# nbulb.net
KiCad netlist of a schematic drawn in EAGLE
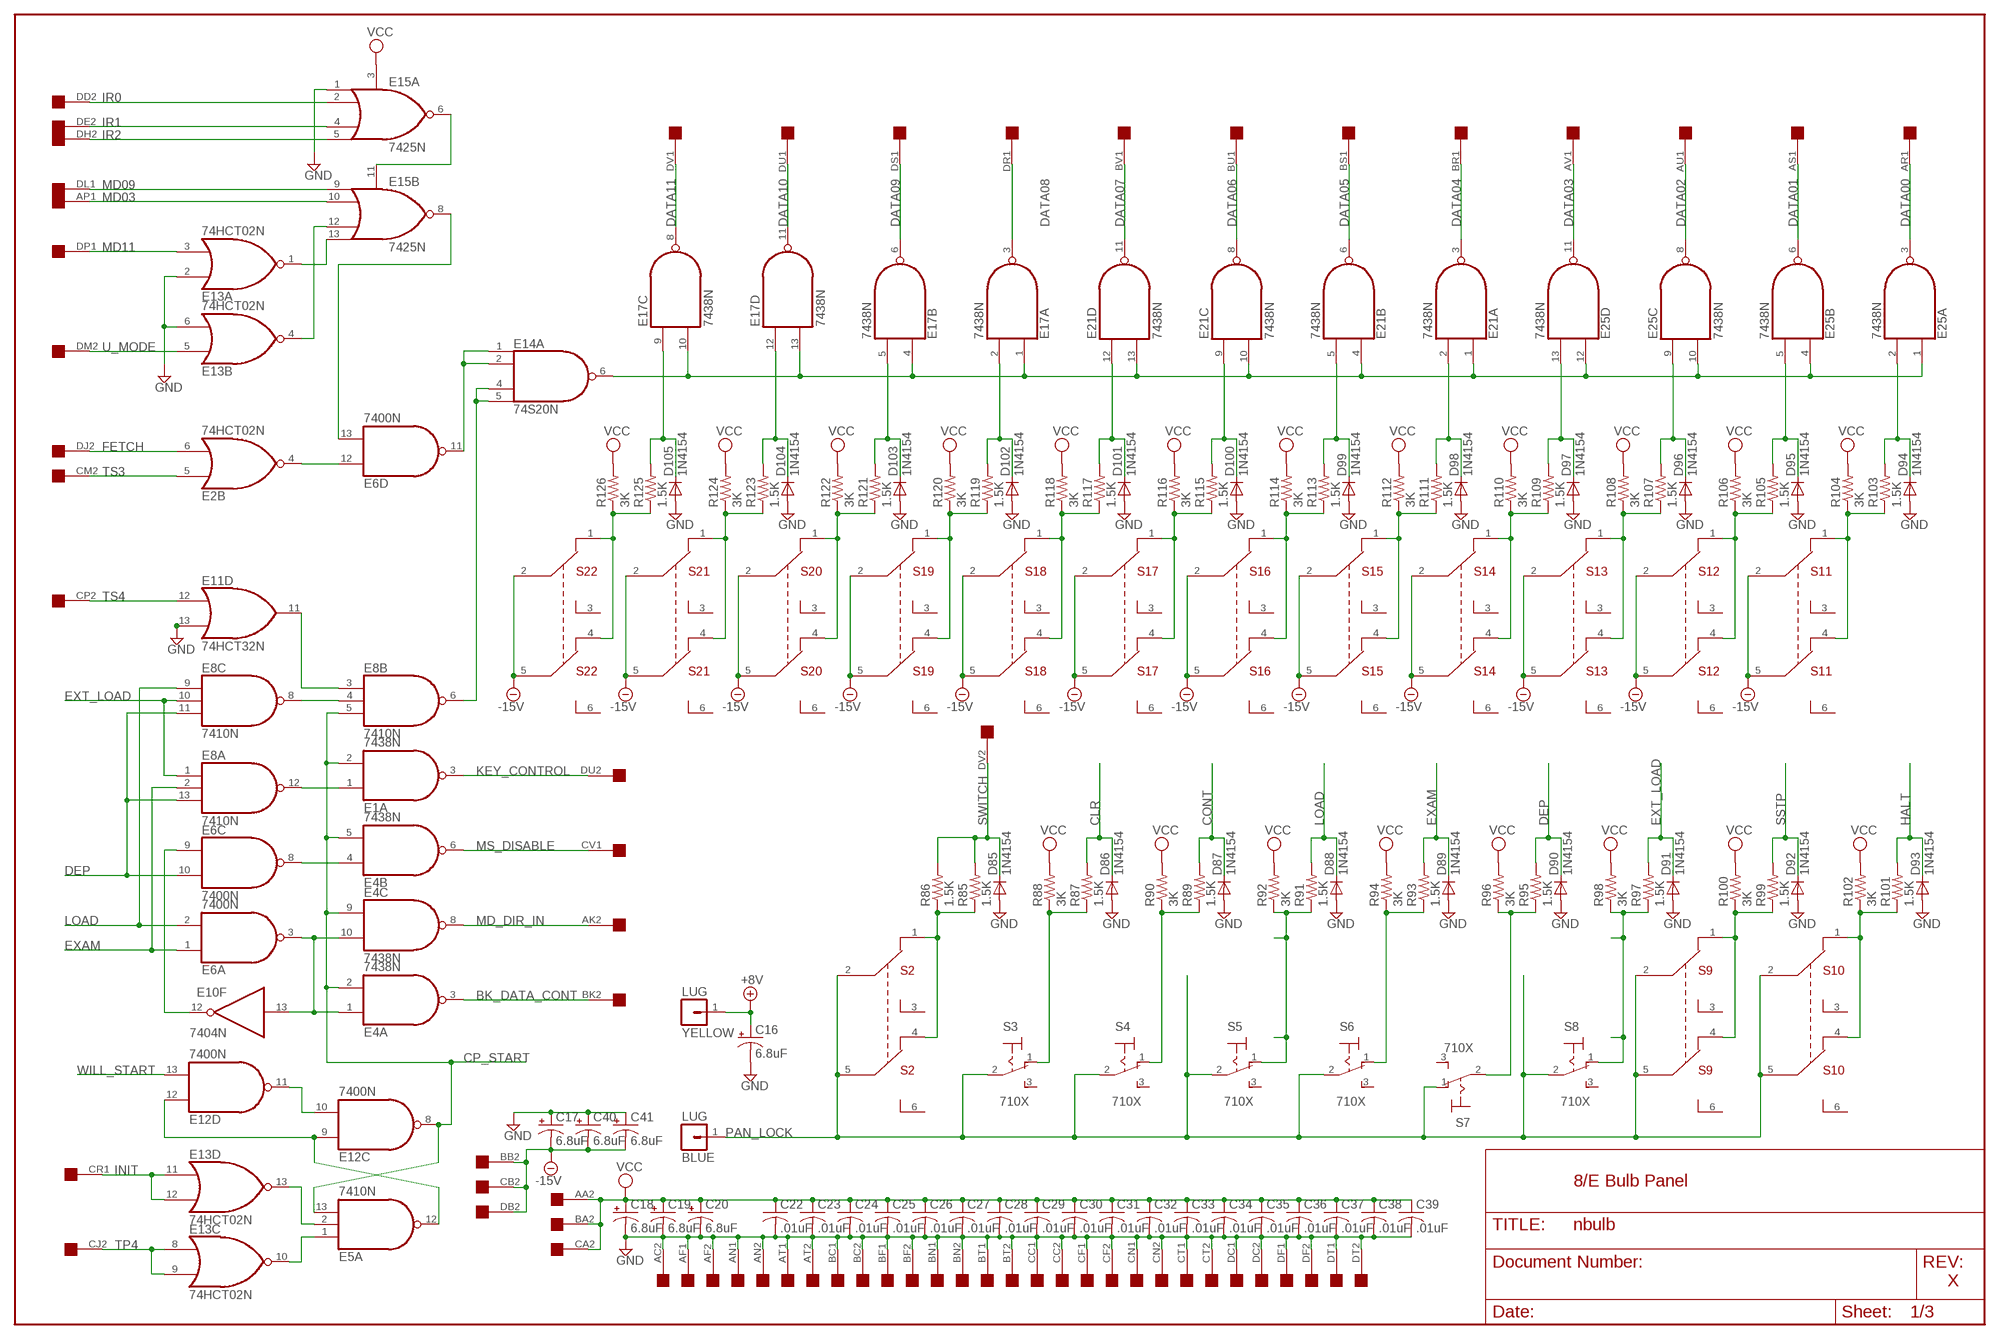
[diagram p0: schematic, sheet 1]
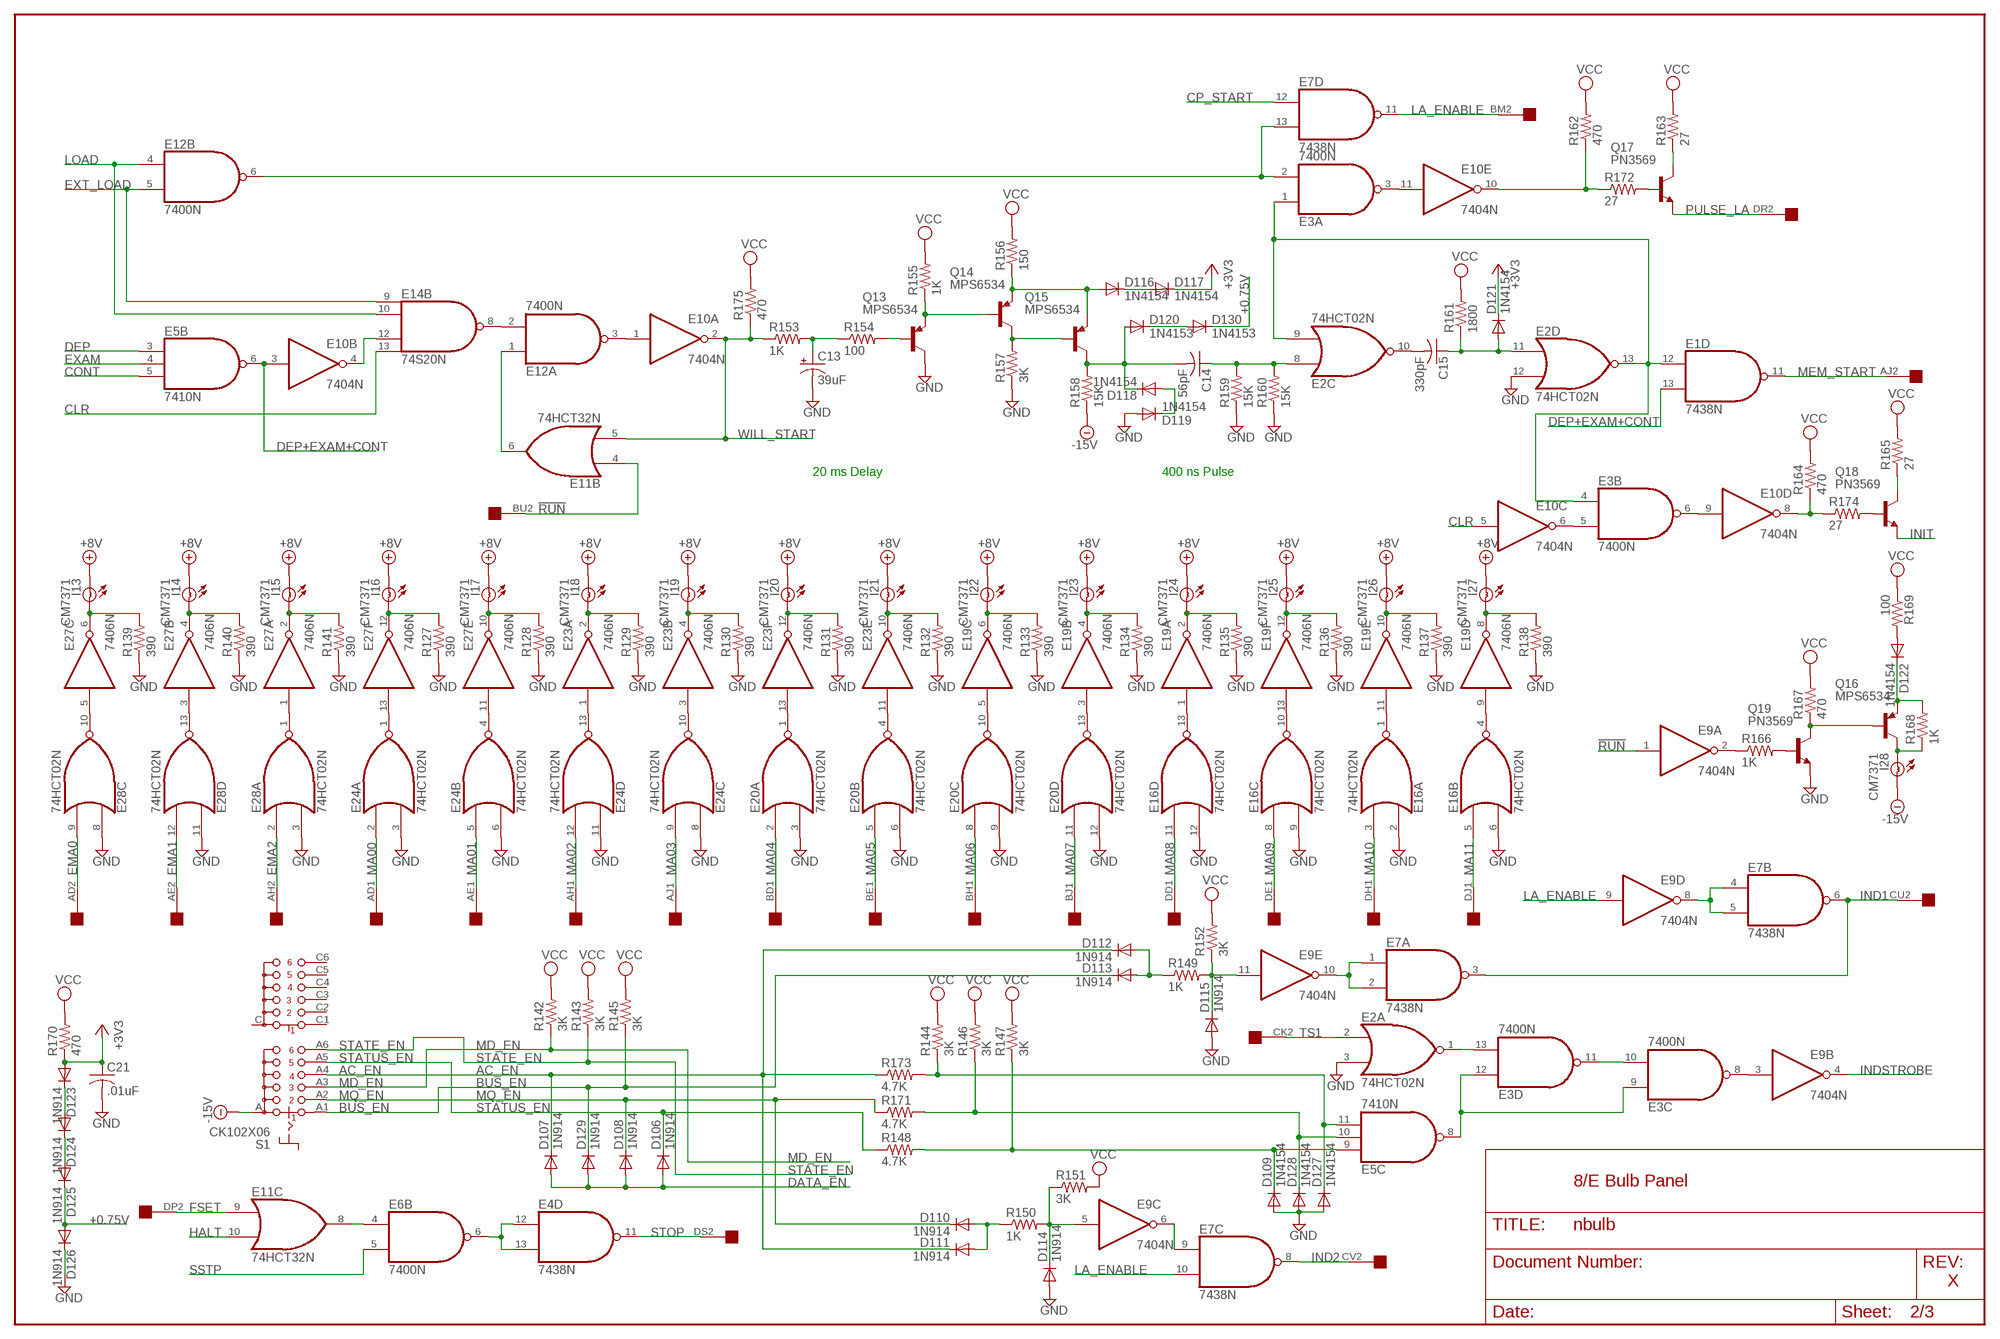
[diagram p1: schematic, sheet 2]
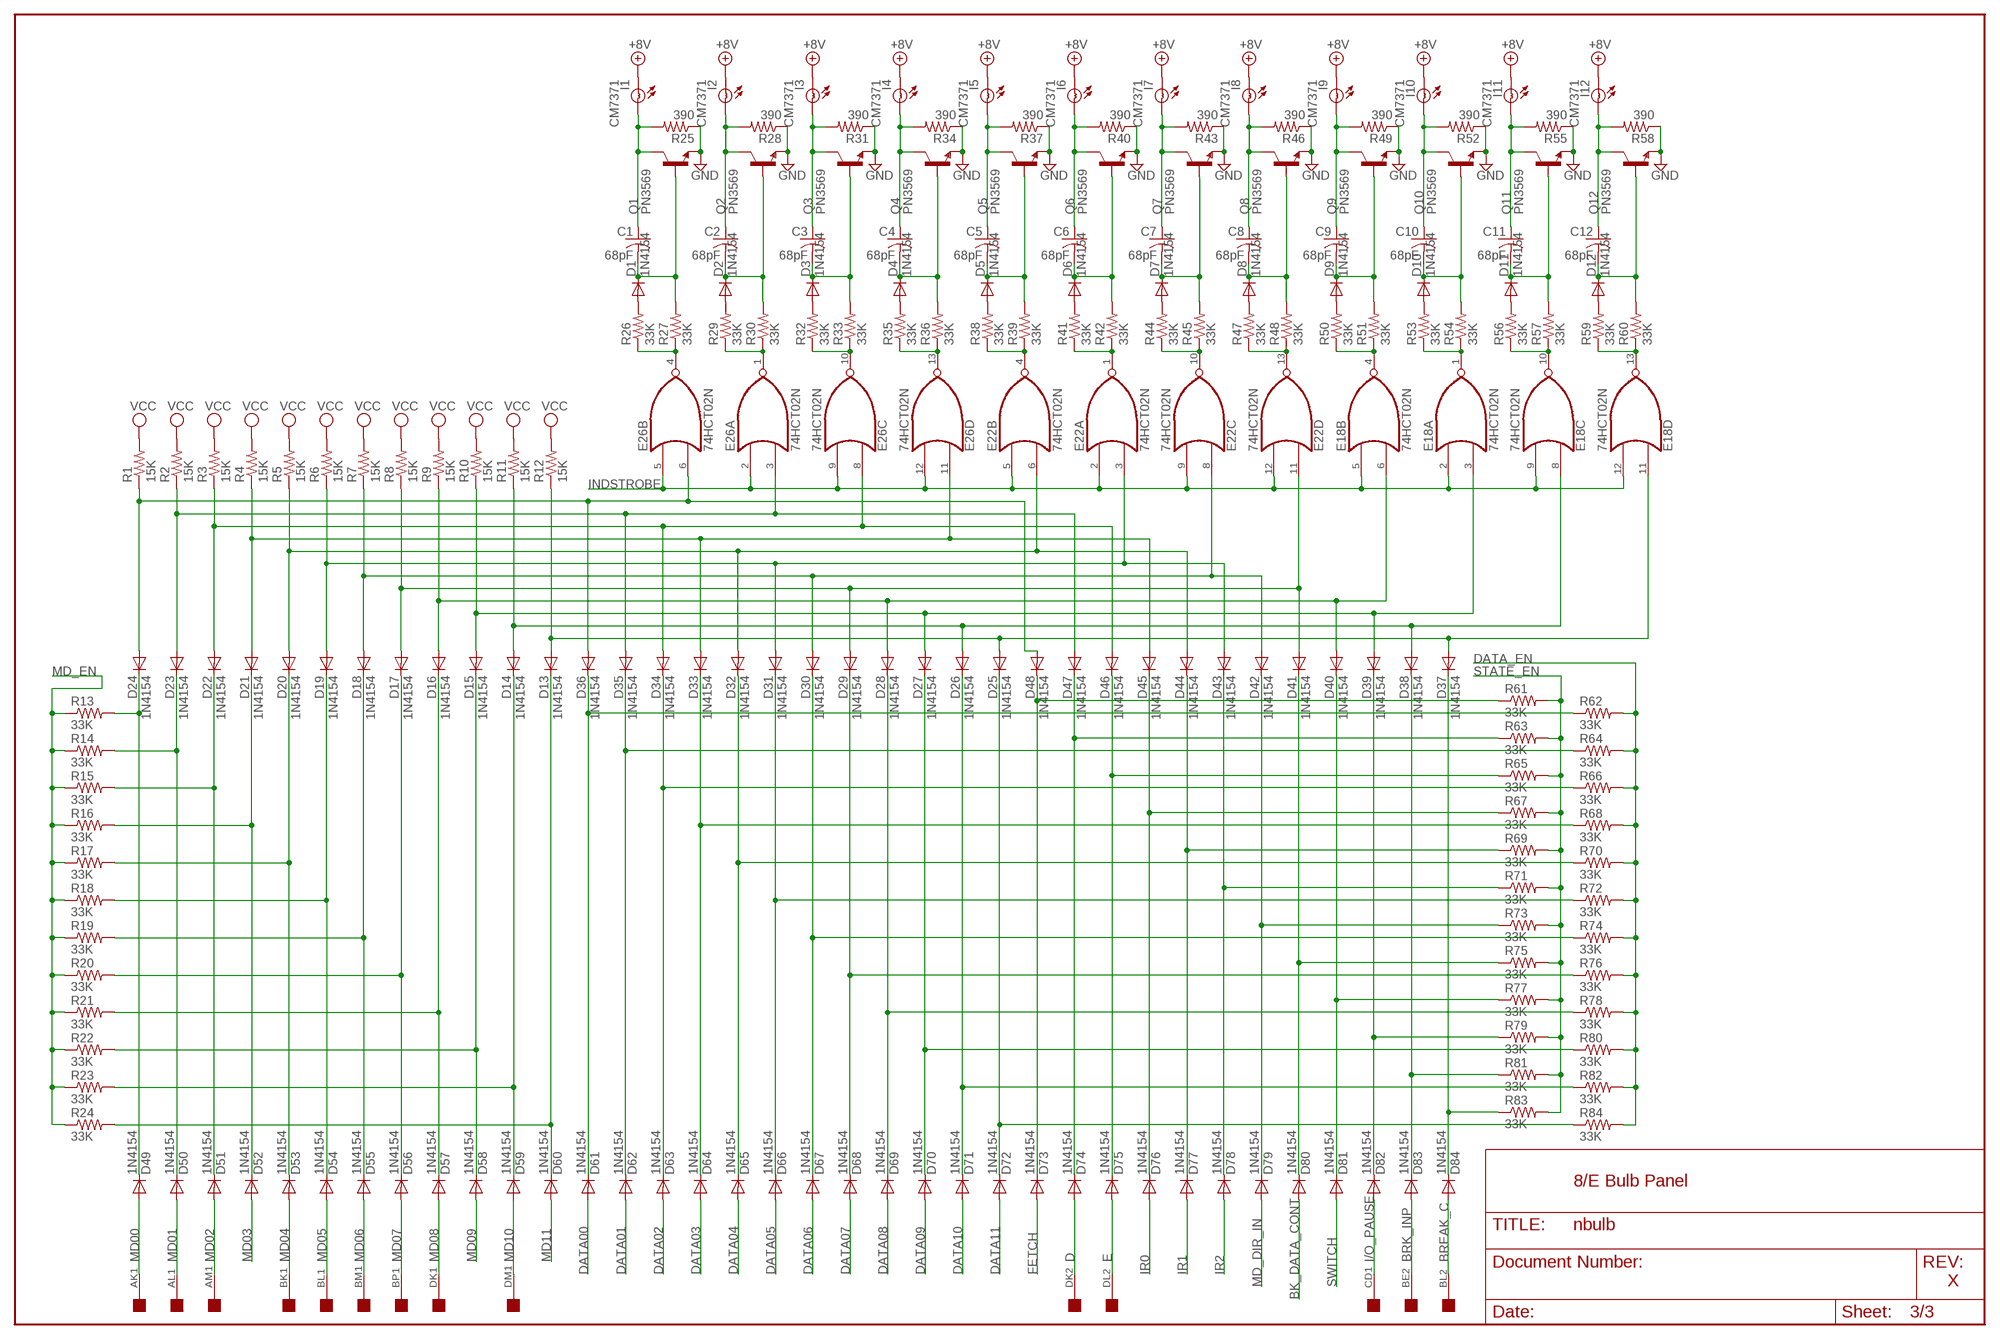
[diagram p2: schematic, sheet 3]

(export (version "E")
  (design (tool "Eeschema 10.0.6"))
  (components
    (comp (ref "BLUE")
      (value "LUG")
      (footprint "eagle-import:SPADELUG")
      (libsource (lib "eagle-import") (part "LUG"))
    )
    (comp (ref "C16")
      (value "6.8uF")
      (footprint "eagle-import:E12-8")
      (libsource (lib "eagle-import") (part "CPOL-USE20-8AXIAL"))
    )
    (comp (ref "C17")
      (value "6.8uF")
      (footprint "eagle-import:E12-8")
      (libsource (lib "eagle-import") (part "CPOL-USE20-8AXIAL"))
    )
    (comp (ref "C18")
      (value "6.8uF")
      (footprint "eagle-import:E12-8")
      (libsource (lib "eagle-import") (part "CPOL-USE20-8AXIAL"))
    )
    (comp (ref "C19")
      (value "6.8uF")
      (footprint "eagle-import:E12-8")
      (libsource (lib "eagle-import") (part "CPOL-USE20-8AXIAL"))
    )
    (comp (ref "C20")
      (value "6.8uF")
      (footprint "eagle-import:E12-8")
      (libsource (lib "eagle-import") (part "CPOL-USE20-8AXIAL"))
    )
    (comp (ref "C22")
      (value ".01uF")
      (footprint "eagle-import:C050-025X075")
      (libsource (lib "eagle-import") (part "C-US050-025X075"))
    )
    (comp (ref "C23")
      (value ".01uF")
      (footprint "eagle-import:C050-025X075")
      (libsource (lib "eagle-import") (part "C-US050-025X075"))
    )
    (comp (ref "C24")
      (value ".01uF")
      (footprint "eagle-import:C050-025X075")
      (libsource (lib "eagle-import") (part "C-US050-025X075"))
    )
    (comp (ref "C25")
      (value ".01uF")
      (footprint "eagle-import:C050-025X075")
      (libsource (lib "eagle-import") (part "C-US050-025X075"))
    )
    (comp (ref "C26")
      (value ".01uF")
      (footprint "eagle-import:C050-025X075")
      (libsource (lib "eagle-import") (part "C-US050-025X075"))
    )
    (comp (ref "C27")
      (value ".01uF")
      (footprint "eagle-import:C050-025X075")
      (libsource (lib "eagle-import") (part "C-US050-025X075"))
    )
    (comp (ref "C28")
      (value ".01uF")
      (footprint "eagle-import:C050-025X075")
      (libsource (lib "eagle-import") (part "C-US050-025X075"))
    )
    (comp (ref "C29")
      (value ".01uF")
      (footprint "eagle-import:C050-025X075")
      (libsource (lib "eagle-import") (part "C-US050-025X075"))
    )
    (comp (ref "C30")
      (value ".01uF")
      (footprint "eagle-import:C050-025X075")
      (libsource (lib "eagle-import") (part "C-US050-025X075"))
    )
    (comp (ref "C31")
      (value ".01uF")
      (footprint "eagle-import:C050-025X075")
      (libsource (lib "eagle-import") (part "C-US050-025X075"))
    )
    (comp (ref "C32")
      (value ".01uF")
      (footprint "eagle-import:C050-025X075")
      (libsource (lib "eagle-import") (part "C-US050-025X075"))
    )
    (comp (ref "C33")
      (value ".01uF")
      (footprint "eagle-import:C050-025X075")
      (libsource (lib "eagle-import") (part "C-US050-025X075"))
    )
    (comp (ref "C34")
      (value ".01uF")
      (footprint "eagle-import:C050-025X075")
      (libsource (lib "eagle-import") (part "C-US050-025X075"))
    )
    (comp (ref "C35")
      (value ".01uF")
      (footprint "eagle-import:C050-025X075")
      (libsource (lib "eagle-import") (part "C-US050-025X075"))
    )
    (comp (ref "C36")
      (value ".01uF")
      (footprint "eagle-import:C050-025X075")
      (libsource (lib "eagle-import") (part "C-US050-025X075"))
    )
    (comp (ref "C37")
      (value ".01uF")
      (footprint "eagle-import:C050-025X075")
      (libsource (lib "eagle-import") (part "C-US050-025X075"))
    )
    (comp (ref "C38")
      (value ".01uF")
      (footprint "eagle-import:C050-025X075")
      (libsource (lib "eagle-import") (part "C-US050-025X075"))
    )
    (comp (ref "C39")
      (value ".01uF")
      (footprint "eagle-import:C050-025X075")
      (libsource (lib "eagle-import") (part "C-US050-025X075"))
    )
    (comp (ref "C40")
      (value "6.8uF")
      (footprint "eagle-import:E12-8")
      (libsource (lib "eagle-import") (part "CPOL-USE20-8AXIAL"))
    )
    (comp (ref "C41")
      (value "6.8uF")
      (footprint "eagle-import:E12-8")
      (libsource (lib "eagle-import") (part "CPOL-USE20-8AXIAL"))
    )
    (comp (ref "D85")
      (value "1N4154")
      (footprint "eagle-import:DO35-10")
      (libsource (lib "eagle-import") (part "1N4148DO35-10"))
    )
    (comp (ref "D86")
      (value "1N4154")
      (footprint "eagle-import:DO35-10")
      (libsource (lib "eagle-import") (part "1N4148DO35-10"))
    )
    (comp (ref "D87")
      (value "1N4154")
      (footprint "eagle-import:DO35-10")
      (libsource (lib "eagle-import") (part "1N4148DO35-10"))
    )
    (comp (ref "D88")
      (value "1N4154")
      (footprint "eagle-import:DO35-10")
      (libsource (lib "eagle-import") (part "1N4148DO35-10"))
    )
    (comp (ref "D89")
      (value "1N4154")
      (footprint "eagle-import:DO35-10")
      (libsource (lib "eagle-import") (part "1N4148DO35-10"))
    )
    (comp (ref "D90")
      (value "1N4154")
      (footprint "eagle-import:DO35-10")
      (libsource (lib "eagle-import") (part "1N4148DO35-10"))
    )
    (comp (ref "D91")
      (value "1N4154")
      (footprint "eagle-import:DO35-10")
      (libsource (lib "eagle-import") (part "1N4148DO35-10"))
    )
    (comp (ref "D92")
      (value "1N4154")
      (footprint "eagle-import:DO35-10")
      (libsource (lib "eagle-import") (part "1N4148DO35-10"))
    )
    (comp (ref "D93")
      (value "1N4154")
      (footprint "eagle-import:DO35-10")
      (libsource (lib "eagle-import") (part "1N4148DO35-10"))
    )
    (comp (ref "D94")
      (value "1N4154")
      (footprint "eagle-import:DO35-10")
      (libsource (lib "eagle-import") (part "1N4148DO35-10"))
    )
    (comp (ref "D95")
      (value "1N4154")
      (footprint "eagle-import:DO35-10")
      (libsource (lib "eagle-import") (part "1N4148DO35-10"))
    )
    (comp (ref "D96")
      (value "1N4154")
      (footprint "eagle-import:DO35-10")
      (libsource (lib "eagle-import") (part "1N4148DO35-10"))
    )
    (comp (ref "D97")
      (value "1N4154")
      (footprint "eagle-import:DO35-10")
      (libsource (lib "eagle-import") (part "1N4148DO35-10"))
    )
    (comp (ref "D98")
      (value "1N4154")
      (footprint "eagle-import:DO35-10")
      (libsource (lib "eagle-import") (part "1N4148DO35-10"))
    )
    (comp (ref "D99")
      (value "1N4154")
      (footprint "eagle-import:DO35-10")
      (libsource (lib "eagle-import") (part "1N4148DO35-10"))
    )
    (comp (ref "D100")
      (value "1N4154")
      (footprint "eagle-import:DO35-10")
      (libsource (lib "eagle-import") (part "1N4148DO35-10"))
    )
    (comp (ref "D101")
      (value "1N4154")
      (footprint "eagle-import:DO35-10")
      (libsource (lib "eagle-import") (part "1N4148DO35-10"))
    )
    (comp (ref "D102")
      (value "1N4154")
      (footprint "eagle-import:DO35-10")
      (libsource (lib "eagle-import") (part "1N4148DO35-10"))
    )
    (comp (ref "D103")
      (value "1N4154")
      (footprint "eagle-import:DO35-10")
      (libsource (lib "eagle-import") (part "1N4148DO35-10"))
    )
    (comp (ref "D104")
      (value "1N4154")
      (footprint "eagle-import:DO35-10")
      (libsource (lib "eagle-import") (part "1N4148DO35-10"))
    )
    (comp (ref "D105")
      (value "1N4154")
      (footprint "eagle-import:DO35-10")
      (libsource (lib "eagle-import") (part "1N4148DO35-10"))
    )
    (comp (ref "E1")
      (value "7438N")
      (footprint "eagle-import:DIL14")
      (libsource (lib "eagle-import") (part "7438N"))
    )
    (comp (ref "E2")
      (value "74HCT02N")
      (footprint "eagle-import:DIL14")
      (libsource (lib "eagle-import") (part "7402NLS"))
    )
    (comp (ref "E4")
      (value "7438N")
      (footprint "eagle-import:DIL14")
      (libsource (lib "eagle-import") (part "7438N"))
    )
    (comp (ref "E5")
      (value "7410N")
      (footprint "eagle-import:DIL14")
      (libsource (lib "eagle-import") (part "7410N"))
    )
    (comp (ref "E6")
      (value "7400N")
      (footprint "eagle-import:DIL14")
      (libsource (lib "eagle-import") (part "7400N"))
    )
    (comp (ref "E8")
      (value "7410N")
      (footprint "eagle-import:DIL14")
      (libsource (lib "eagle-import") (part "7410N"))
    )
    (comp (ref "E10")
      (value "7404N")
      (footprint "eagle-import:DIL14")
      (libsource (lib "eagle-import") (part "7404N"))
    )
    (comp (ref "E11")
      (value "74HCT32N")
      (footprint "eagle-import:DIL14")
      (libsource (lib "eagle-import") (part "7432NLS"))
    )
    (comp (ref "E12")
      (value "7400N")
      (footprint "eagle-import:DIL14")
      (libsource (lib "eagle-import") (part "7400N"))
    )
    (comp (ref "E13")
      (value "74HCT02N")
      (footprint "eagle-import:DIL14")
      (libsource (lib "eagle-import") (part "7402NLS"))
    )
    (comp (ref "E14")
      (value "74S20N")
      (footprint "eagle-import:DIL14")
      (libsource (lib "eagle-import") (part "7420NS"))
    )
    (comp (ref "E15")
      (value "7425N")
      (footprint "eagle-import:DIL14")
      (libsource (lib "eagle-import") (part "7425N"))
    )
    (comp (ref "E17")
      (value "7438N")
      (footprint "eagle-import:DIL14")
      (libsource (lib "eagle-import") (part "7438N"))
    )
    (comp (ref "E21")
      (value "7438N")
      (footprint "eagle-import:DIL14")
      (libsource (lib "eagle-import") (part "7438N"))
    )
    (comp (ref "E25")
      (value "7438N")
      (footprint "eagle-import:DIL14")
      (libsource (lib "eagle-import") (part "7438N"))
    )
    (comp (ref "R85")
      (value "1.5K")
      (footprint "eagle-import:0207_10")
      (libsource (lib "eagle-import") (part "R-US_0207/10"))
    )
    (comp (ref "R86")
      (value "1.5K")
      (footprint "eagle-import:0207_10")
      (libsource (lib "eagle-import") (part "R-US_0207/10"))
    )
    (comp (ref "R87")
      (value "1.5K")
      (footprint "eagle-import:0207_10")
      (libsource (lib "eagle-import") (part "R-US_0207/10"))
    )
    (comp (ref "R88")
      (value "3K")
      (footprint "eagle-import:0207_10")
      (libsource (lib "eagle-import") (part "R-US_0207/10"))
    )
    (comp (ref "R89")
      (value "1.5K")
      (footprint "eagle-import:0207_10")
      (libsource (lib "eagle-import") (part "R-US_0207/10"))
    )
    (comp (ref "R90")
      (value "3K")
      (footprint "eagle-import:0207_10")
      (libsource (lib "eagle-import") (part "R-US_0207/10"))
    )
    (comp (ref "R91")
      (value "1.5K")
      (footprint "eagle-import:0207_10")
      (libsource (lib "eagle-import") (part "R-US_0207/10"))
    )
    (comp (ref "R92")
      (value "3K")
      (footprint "eagle-import:0207_10")
      (libsource (lib "eagle-import") (part "R-US_0207/10"))
    )
    (comp (ref "R93")
      (value "1.5K")
      (footprint "eagle-import:0207_10")
      (libsource (lib "eagle-import") (part "R-US_0207/10"))
    )
    (comp (ref "R94")
      (value "3K")
      (footprint "eagle-import:0207_10")
      (libsource (lib "eagle-import") (part "R-US_0207/10"))
    )
    (comp (ref "R95")
      (value "1.5K")
      (footprint "eagle-import:0207_10")
      (libsource (lib "eagle-import") (part "R-US_0207/10"))
    )
    (comp (ref "R96")
      (value "3K")
      (footprint "eagle-import:0207_10")
      (libsource (lib "eagle-import") (part "R-US_0207/10"))
    )
    (comp (ref "R97")
      (value "1.5K")
      (footprint "eagle-import:0207_10")
      (libsource (lib "eagle-import") (part "R-US_0207/10"))
    )
    (comp (ref "R98")
      (value "3K")
      (footprint "eagle-import:0207_10")
      (libsource (lib "eagle-import") (part "R-US_0207/10"))
    )
    (comp (ref "R99")
      (value "1.5K")
      (footprint "eagle-import:0207_10")
      (libsource (lib "eagle-import") (part "R-US_0207/10"))
    )
    (comp (ref "R100")
      (value "3K")
      (footprint "eagle-import:0207_10")
      (libsource (lib "eagle-import") (part "R-US_0207/10"))
    )
    (comp (ref "R101")
      (value "1.5K")
      (footprint "eagle-import:0207_10")
      (libsource (lib "eagle-import") (part "R-US_0207/10"))
    )
    (comp (ref "R102")
      (value "3K")
      (footprint "eagle-import:0207_10")
      (libsource (lib "eagle-import") (part "R-US_0207/10"))
    )
    (comp (ref "R103")
      (value "1.5K")
      (footprint "eagle-import:0207_10")
      (libsource (lib "eagle-import") (part "R-US_0207/10"))
    )
    (comp (ref "R104")
      (value "3K")
      (footprint "eagle-import:0207_10")
      (libsource (lib "eagle-import") (part "R-US_0207/10"))
    )
    (comp (ref "R105")
      (value "1.5K")
      (footprint "eagle-import:0207_10")
      (libsource (lib "eagle-import") (part "R-US_0207/10"))
    )
    (comp (ref "R106")
      (value "3K")
      (footprint "eagle-import:0207_10")
      (libsource (lib "eagle-import") (part "R-US_0207/10"))
    )
    (comp (ref "R107")
      (value "1.5K")
      (footprint "eagle-import:0207_10")
      (libsource (lib "eagle-import") (part "R-US_0207/10"))
    )
    (comp (ref "R108")
      (value "3K")
      (footprint "eagle-import:0207_10")
      (libsource (lib "eagle-import") (part "R-US_0207/10"))
    )
    (comp (ref "R109")
      (value "1.5K")
      (footprint "eagle-import:0207_10")
      (libsource (lib "eagle-import") (part "R-US_0207/10"))
    )
    (comp (ref "R110")
      (value "3K")
      (footprint "eagle-import:0207_10")
      (libsource (lib "eagle-import") (part "R-US_0207/10"))
    )
    (comp (ref "R111")
      (value "1.5K")
      (footprint "eagle-import:0207_10")
      (libsource (lib "eagle-import") (part "R-US_0207/10"))
    )
    (comp (ref "R112")
      (value "3K")
      (footprint "eagle-import:0207_10")
      (libsource (lib "eagle-import") (part "R-US_0207/10"))
    )
    (comp (ref "R113")
      (value "1.5K")
      (footprint "eagle-import:0207_10")
      (libsource (lib "eagle-import") (part "R-US_0207/10"))
    )
    (comp (ref "R114")
      (value "3K")
      (footprint "eagle-import:0207_10")
      (libsource (lib "eagle-import") (part "R-US_0207/10"))
    )
    (comp (ref "R115")
      (value "1.5K")
      (footprint "eagle-import:0207_10")
      (libsource (lib "eagle-import") (part "R-US_0207/10"))
    )
    (comp (ref "R116")
      (value "3K")
      (footprint "eagle-import:0207_10")
      (libsource (lib "eagle-import") (part "R-US_0207/10"))
    )
    (comp (ref "R117")
      (value "1.5K")
      (footprint "eagle-import:0207_10")
      (libsource (lib "eagle-import") (part "R-US_0207/10"))
    )
    (comp (ref "R118")
      (value "3K")
      (footprint "eagle-import:0207_10")
      (libsource (lib "eagle-import") (part "R-US_0207/10"))
    )
    (comp (ref "R119")
      (value "1.5K")
      (footprint "eagle-import:0207_10")
      (libsource (lib "eagle-import") (part "R-US_0207/10"))
    )
    (comp (ref "R120")
      (value "3K")
      (footprint "eagle-import:0207_10")
      (libsource (lib "eagle-import") (part "R-US_0207/10"))
    )
    (comp (ref "R121")
      (value "1.5K")
      (footprint "eagle-import:0207_10")
      (libsource (lib "eagle-import") (part "R-US_0207/10"))
    )
    (comp (ref "R122")
      (value "3K")
      (footprint "eagle-import:0207_10")
      (libsource (lib "eagle-import") (part "R-US_0207/10"))
    )
    (comp (ref "R123")
      (value "1.5K")
      (footprint "eagle-import:0207_10")
      (libsource (lib "eagle-import") (part "R-US_0207/10"))
    )
    (comp (ref "R124")
      (value "3K")
      (footprint "eagle-import:0207_10")
      (libsource (lib "eagle-import") (part "R-US_0207/10"))
    )
    (comp (ref "R125")
      (value "1.5K")
      (footprint "eagle-import:0207_10")
      (libsource (lib "eagle-import") (part "R-US_0207/10"))
    )
    (comp (ref "R126")
      (value "3K")
      (footprint "eagle-import:0207_10")
      (libsource (lib "eagle-import") (part "R-US_0207/10"))
    )
    (comp (ref "S2")
      (value "720X")
      (footprint "eagle-import:7209MD9V3")
      (libsource (lib "eagle-import") (part "720X"))
    )
    (comp (ref "S3")
      (value "710X")
      (footprint "eagle-import:7109MD9V3")
      (libsource (lib "eagle-import") (part "710X"))
    )
    (comp (ref "S4")
      (value "710X")
      (footprint "eagle-import:7109MD9V3")
      (libsource (lib "eagle-import") (part "710X"))
    )
    (comp (ref "S5")
      (value "710X")
      (footprint "eagle-import:7109MD9V3")
      (libsource (lib "eagle-import") (part "710X"))
    )
    (comp (ref "S6")
      (value "710X")
      (footprint "eagle-import:7109MD9V3")
      (libsource (lib "eagle-import") (part "710X"))
    )
    (comp (ref "S7")
      (value "710X")
      (footprint "eagle-import:7109MD9V3")
      (libsource (lib "eagle-import") (part "710X"))
    )
    (comp (ref "S8")
      (value "710X")
      (footprint "eagle-import:7109MD9V3")
      (libsource (lib "eagle-import") (part "710X"))
    )
    (comp (ref "S9")
      (value "720X")
      (footprint "eagle-import:7209MD9V3")
      (libsource (lib "eagle-import") (part "720X"))
    )
    (comp (ref "S10")
      (value "720X")
      (footprint "eagle-import:7209MD9V3")
      (libsource (lib "eagle-import") (part "720X"))
    )
    (comp (ref "S11")
      (value "720X")
      (footprint "eagle-import:7209MD9V3")
      (libsource (lib "eagle-import") (part "720X"))
    )
    (comp (ref "S12")
      (value "720X")
      (footprint "eagle-import:7209MD9V3")
      (libsource (lib "eagle-import") (part "720X"))
    )
    (comp (ref "S13")
      (value "720X")
      (footprint "eagle-import:7209MD9V3")
      (libsource (lib "eagle-import") (part "720X"))
    )
    (comp (ref "S14")
      (value "720X")
      (footprint "eagle-import:7209MD9V3")
      (libsource (lib "eagle-import") (part "720X"))
    )
    (comp (ref "S15")
      (value "720X")
      (footprint "eagle-import:7209MD9V3")
      (libsource (lib "eagle-import") (part "720X"))
    )
    (comp (ref "S16")
      (value "720X")
      (footprint "eagle-import:7209MD9V3")
      (libsource (lib "eagle-import") (part "720X"))
    )
    (comp (ref "S17")
      (value "720X")
      (footprint "eagle-import:7209MD9V3")
      (libsource (lib "eagle-import") (part "720X"))
    )
    (comp (ref "S18")
      (value "720X")
      (footprint "eagle-import:7209MD9V3")
      (libsource (lib "eagle-import") (part "720X"))
    )
    (comp (ref "S19")
      (value "720X")
      (footprint "eagle-import:7209MD9V3")
      (libsource (lib "eagle-import") (part "720X"))
    )
    (comp (ref "S20")
      (value "720X")
      (footprint "eagle-import:7209MD9V3")
      (libsource (lib "eagle-import") (part "720X"))
    )
    (comp (ref "S21")
      (value "720X")
      (footprint "eagle-import:7209MD9V3")
      (libsource (lib "eagle-import") (part "720X"))
    )
    (comp (ref "S22")
      (value "720X")
      (footprint "eagle-import:7209MD9V3")
      (libsource (lib "eagle-import") (part "720X"))
    )
    (comp (ref "U$2")
      (value "QUAD")
      (footprint "eagle-import:EDGE-CON8")
      (libsource (lib "eagle-import") (part "QUAD"))
    )
    (comp (ref "YELLOW")
      (value "LUG")
      (footprint "eagle-import:SPADELUG")
      (libsource (lib "eagle-import") (part "LUG"))
    )
    (comp (ref "C13")
      (value "39uF")
      (footprint "eagle-import:E12-8")
      (libsource (lib "eagle-import") (part "CPOL-USE20-8AXIAL"))
    )
    (comp (ref "C14")
      (value "56pF")
      (footprint "eagle-import:C050-025X075")
      (libsource (lib "eagle-import") (part "C-US050-025X075"))
    )
    (comp (ref "C15")
      (value "330pF")
      (footprint "eagle-import:C050-025X075")
      (libsource (lib "eagle-import") (part "C-US050-025X075"))
    )
    (comp (ref "C21")
      (value ".01uF")
      (footprint "eagle-import:C050-025X075")
      (libsource (lib "eagle-import") (part "C-US050-025X075"))
    )
    (comp (ref "D106")
      (value "1N914")
      (footprint "eagle-import:DO35-10")
      (libsource (lib "eagle-import") (part "1N4148DO35-10"))
    )
    (comp (ref "D107")
      (value "1N914")
      (footprint "eagle-import:DO35-10")
      (libsource (lib "eagle-import") (part "1N4148DO35-10"))
    )
    (comp (ref "D108")
      (value "1N914")
      (footprint "eagle-import:DO35-10")
      (libsource (lib "eagle-import") (part "1N4148DO35-10"))
    )
    (comp (ref "D109")
      (value "1N4154")
      (footprint "eagle-import:DO35-10")
      (libsource (lib "eagle-import") (part "1N4148DO35-10"))
    )
    (comp (ref "D110")
      (value "1N914")
      (footprint "eagle-import:DO35-10")
      (libsource (lib "eagle-import") (part "1N4148DO35-10"))
    )
    (comp (ref "D111")
      (value "1N914")
      (footprint "eagle-import:DO35-10")
      (libsource (lib "eagle-import") (part "1N4148DO35-10"))
    )
    (comp (ref "D112")
      (value "1N914")
      (footprint "eagle-import:DO35-10")
      (libsource (lib "eagle-import") (part "1N4148DO35-10"))
    )
    (comp (ref "D113")
      (value "1N914")
      (footprint "eagle-import:DO35-10")
      (libsource (lib "eagle-import") (part "1N4148DO35-10"))
    )
    (comp (ref "D114")
      (value "1N914")
      (footprint "eagle-import:DO35-10")
      (libsource (lib "eagle-import") (part "1N4148DO35-10"))
    )
    (comp (ref "D115")
      (value "1N914")
      (footprint "eagle-import:DO35-10")
      (libsource (lib "eagle-import") (part "1N4148DO35-10"))
    )
    (comp (ref "D116")
      (value "1N4154")
      (footprint "eagle-import:DO35-10")
      (libsource (lib "eagle-import") (part "1N4148DO35-10"))
    )
    (comp (ref "D117")
      (value "1N4154")
      (footprint "eagle-import:DO35-10")
      (libsource (lib "eagle-import") (part "1N4148DO35-10"))
    )
    (comp (ref "D118")
      (value "1N4154")
      (footprint "eagle-import:DO35-10")
      (libsource (lib "eagle-import") (part "1N4148DO35-10"))
    )
    (comp (ref "D119")
      (value "1N4154")
      (footprint "eagle-import:DO35-10")
      (libsource (lib "eagle-import") (part "1N4148DO35-10"))
    )
    (comp (ref "D120")
      (value "1N4153")
      (footprint "eagle-import:DO35-10")
      (libsource (lib "eagle-import") (part "1N4148DO35-10"))
    )
    (comp (ref "D121")
      (value "1N4154")
      (footprint "eagle-import:DO35-10")
      (libsource (lib "eagle-import") (part "1N4148DO35-10"))
    )
    (comp (ref "D122")
      (value "1N4154")
      (footprint "eagle-import:DO35-10")
      (libsource (lib "eagle-import") (part "1N4148DO35-10"))
    )
    (comp (ref "D123")
      (value "1N914")
      (footprint "eagle-import:DO35-10")
      (libsource (lib "eagle-import") (part "1N4148DO35-10"))
    )
    (comp (ref "D124")
      (value "1N914")
      (footprint "eagle-import:DO35-10")
      (libsource (lib "eagle-import") (part "1N4148DO35-10"))
    )
    (comp (ref "D125")
      (value "1N914")
      (footprint "eagle-import:DO35-10")
      (libsource (lib "eagle-import") (part "1N4148DO35-10"))
    )
    (comp (ref "D126")
      (value "1N914")
      (footprint "eagle-import:DO35-10")
      (libsource (lib "eagle-import") (part "1N4148DO35-10"))
    )
    (comp (ref "D127")
      (value "1N4154")
      (footprint "eagle-import:DO35-10")
      (libsource (lib "eagle-import") (part "1N4148DO35-10"))
    )
    (comp (ref "D128")
      (value "1N4154")
      (footprint "eagle-import:DO35-10")
      (libsource (lib "eagle-import") (part "1N4148DO35-10"))
    )
    (comp (ref "D129")
      (value "1N914")
      (footprint "eagle-import:DO35-10")
      (libsource (lib "eagle-import") (part "1N4148DO35-10"))
    )
    (comp (ref "D130")
      (value "1N4153")
      (footprint "eagle-import:DO35-10")
      (libsource (lib "eagle-import") (part "1N4148DO35-10"))
    )
    (comp (ref "E3")
      (value "7400N")
      (footprint "eagle-import:DIL14")
      (libsource (lib "eagle-import") (part "7400N"))
    )
    (comp (ref "E7")
      (value "7438N")
      (footprint "eagle-import:DIL14")
      (libsource (lib "eagle-import") (part "7438N"))
    )
    (comp (ref "E9")
      (value "7404N")
      (footprint "eagle-import:DIL14")
      (libsource (lib "eagle-import") (part "7404N"))
    )
    (comp (ref "E16")
      (value "74HCT02N")
      (footprint "eagle-import:DIL14")
      (libsource (lib "eagle-import") (part "7402NLS"))
    )
    (comp (ref "E19")
      (value "7406N")
      (footprint "eagle-import:DIL14")
      (libsource (lib "eagle-import") (part "7406N"))
    )
    (comp (ref "E20")
      (value "74HCT02N")
      (footprint "eagle-import:DIL14")
      (libsource (lib "eagle-import") (part "7402NLS"))
    )
    (comp (ref "E23")
      (value "7406N")
      (footprint "eagle-import:DIL14")
      (libsource (lib "eagle-import") (part "7406N"))
    )
    (comp (ref "E24")
      (value "74HCT02N")
      (footprint "eagle-import:DIL14")
      (libsource (lib "eagle-import") (part "7402NLS"))
    )
    (comp (ref "E27")
      (value "7406N")
      (footprint "eagle-import:DIL14")
      (libsource (lib "eagle-import") (part "7406N"))
    )
    (comp (ref "E28")
      (value "74HCT02N")
      (footprint "eagle-import:DIL14")
      (libsource (lib "eagle-import") (part "7402NLS"))
    )
    (comp (ref "I13")
      (value "CM7371")
      (footprint "eagle-import:BULB")
      (libsource (lib "eagle-import") (part "BULB"))
    )
    (comp (ref "I14")
      (value "CM7371")
      (footprint "eagle-import:BULB")
      (libsource (lib "eagle-import") (part "BULB"))
    )
    (comp (ref "I15")
      (value "CM7371")
      (footprint "eagle-import:BULB")
      (libsource (lib "eagle-import") (part "BULB"))
    )
    (comp (ref "I16")
      (value "CM7371")
      (footprint "eagle-import:BULB")
      (libsource (lib "eagle-import") (part "BULB"))
    )
    (comp (ref "I17")
      (value "CM7371")
      (footprint "eagle-import:BULB")
      (libsource (lib "eagle-import") (part "BULB"))
    )
    (comp (ref "I18")
      (value "CM7371")
      (footprint "eagle-import:BULB")
      (libsource (lib "eagle-import") (part "BULB"))
    )
    (comp (ref "I19")
      (value "CM7371")
      (footprint "eagle-import:BULB")
      (libsource (lib "eagle-import") (part "BULB"))
    )
    (comp (ref "I20")
      (value "CM7371")
      (footprint "eagle-import:BULB")
      (libsource (lib "eagle-import") (part "BULB"))
    )
    (comp (ref "I21")
      (value "CM7371")
      (footprint "eagle-import:BULB")
      (libsource (lib "eagle-import") (part "BULB"))
    )
    (comp (ref "I22")
      (value "CM7371")
      (footprint "eagle-import:BULB")
      (libsource (lib "eagle-import") (part "BULB"))
    )
    (comp (ref "I23")
      (value "CM7371")
      (footprint "eagle-import:BULB")
      (libsource (lib "eagle-import") (part "BULB"))
    )
    (comp (ref "I24")
      (value "CM7371")
      (footprint "eagle-import:BULB")
      (libsource (lib "eagle-import") (part "BULB"))
    )
    (comp (ref "I25")
      (value "CM7371")
      (footprint "eagle-import:BULB")
      (libsource (lib "eagle-import") (part "BULB"))
    )
    (comp (ref "I26")
      (value "CM7371")
      (footprint "eagle-import:BULB")
      (libsource (lib "eagle-import") (part "BULB"))
    )
    (comp (ref "I27")
      (value "CM7371")
      (footprint "eagle-import:BULB")
      (libsource (lib "eagle-import") (part "BULB"))
    )
    (comp (ref "I28")
      (value "CM7371")
      (footprint "eagle-import:BULB")
      (libsource (lib "eagle-import") (part "BULB"))
    )
    (comp (ref "Q13")
      (value "MPS6534")
      (footprint "eagle-import:TO39")
      (libsource (lib "eagle-import") (part "2N3637"))
    )
    (comp (ref "Q14")
      (value "MPS6534")
      (footprint "eagle-import:TO39")
      (libsource (lib "eagle-import") (part "2N3637"))
    )
    (comp (ref "Q15")
      (value "MPS6534")
      (footprint "eagle-import:TO39")
      (libsource (lib "eagle-import") (part "2N3637"))
    )
    (comp (ref "Q16")
      (value "MPS6534")
      (footprint "eagle-import:TO39")
      (libsource (lib "eagle-import") (part "2N3637"))
    )
    (comp (ref "Q17")
      (value "PN3569")
      (footprint "eagle-import:TO39")
      (libsource (lib "eagle-import") (part "2N3019"))
    )
    (comp (ref "Q18")
      (value "PN3569")
      (footprint "eagle-import:TO39")
      (libsource (lib "eagle-import") (part "2N3019"))
    )
    (comp (ref "Q19")
      (value "PN3569")
      (footprint "eagle-import:TO39")
      (libsource (lib "eagle-import") (part "2N3019"))
    )
    (comp (ref "R127")
      (value "390")
      (footprint "eagle-import:0207_10")
      (libsource (lib "eagle-import") (part "R-US_0207/10"))
    )
    (comp (ref "R128")
      (value "390")
      (footprint "eagle-import:0207_10")
      (libsource (lib "eagle-import") (part "R-US_0207/10"))
    )
    (comp (ref "R129")
      (value "390")
      (footprint "eagle-import:0207_10")
      (libsource (lib "eagle-import") (part "R-US_0207/10"))
    )
    (comp (ref "R130")
      (value "390")
      (footprint "eagle-import:0207_10")
      (libsource (lib "eagle-import") (part "R-US_0207/10"))
    )
    (comp (ref "R131")
      (value "390")
      (footprint "eagle-import:0207_10")
      (libsource (lib "eagle-import") (part "R-US_0207/10"))
    )
    (comp (ref "R132")
      (value "390")
      (footprint "eagle-import:0207_10")
      (libsource (lib "eagle-import") (part "R-US_0207/10"))
    )
    (comp (ref "R133")
      (value "390")
      (footprint "eagle-import:0207_10")
      (libsource (lib "eagle-import") (part "R-US_0207/10"))
    )
    (comp (ref "R134")
      (value "390")
      (footprint "eagle-import:0207_10")
      (libsource (lib "eagle-import") (part "R-US_0207/10"))
    )
    (comp (ref "R135")
      (value "390")
      (footprint "eagle-import:0207_10")
      (libsource (lib "eagle-import") (part "R-US_0207/10"))
    )
    (comp (ref "R136")
      (value "390")
      (footprint "eagle-import:0207_10")
      (libsource (lib "eagle-import") (part "R-US_0207/10"))
    )
    (comp (ref "R137")
      (value "390")
      (footprint "eagle-import:0207_10")
      (libsource (lib "eagle-import") (part "R-US_0207/10"))
    )
    (comp (ref "R138")
      (value "390")
      (footprint "eagle-import:0207_10")
      (libsource (lib "eagle-import") (part "R-US_0207/10"))
    )
    (comp (ref "R139")
      (value "390")
      (footprint "eagle-import:0207_10")
      (libsource (lib "eagle-import") (part "R-US_0207/10"))
    )
    (comp (ref "R140")
      (value "390")
      (footprint "eagle-import:0207_10")
      (libsource (lib "eagle-import") (part "R-US_0207/10"))
    )
    (comp (ref "R141")
      (value "390")
      (footprint "eagle-import:0207_10")
      (libsource (lib "eagle-import") (part "R-US_0207/10"))
    )
    (comp (ref "R142")
      (value "3K")
      (footprint "eagle-import:0207_10")
      (libsource (lib "eagle-import") (part "R-US_0207/10"))
    )
    (comp (ref "R143")
      (value "3K")
      (footprint "eagle-import:0207_10")
      (libsource (lib "eagle-import") (part "R-US_0207/10"))
    )
    (comp (ref "R144")
      (value "3K")
      (footprint "eagle-import:0207_10")
      (libsource (lib "eagle-import") (part "R-US_0207/10"))
    )
    (comp (ref "R145")
      (value "3K")
      (footprint "eagle-import:0207_10")
      (libsource (lib "eagle-import") (part "R-US_0207/10"))
    )
    (comp (ref "R146")
      (value "3K")
      (footprint "eagle-import:0207_10")
      (libsource (lib "eagle-import") (part "R-US_0207/10"))
    )
    (comp (ref "R147")
      (value "3K")
      (footprint "eagle-import:0207_10")
      (libsource (lib "eagle-import") (part "R-US_0207/10"))
    )
    (comp (ref "R148")
      (value "4.7K")
      (footprint "eagle-import:0207_10")
      (libsource (lib "eagle-import") (part "R-US_0207/10"))
    )
    (comp (ref "R149")
      (value "1K")
      (footprint "eagle-import:0207_10")
      (libsource (lib "eagle-import") (part "R-US_0207/10"))
    )
    (comp (ref "R150")
      (value "1K")
      (footprint "eagle-import:0207_10")
      (libsource (lib "eagle-import") (part "R-US_0207/10"))
    )
    (comp (ref "R151")
      (value "3K")
      (footprint "eagle-import:0207_10")
      (libsource (lib "eagle-import") (part "R-US_0207/10"))
    )
    (comp (ref "R152")
      (value "3K")
      (footprint "eagle-import:0207_10")
      (libsource (lib "eagle-import") (part "R-US_0207/10"))
    )
    (comp (ref "R153")
      (value "1K")
      (footprint "eagle-import:0207_10")
      (libsource (lib "eagle-import") (part "R-US_0207/10"))
    )
    (comp (ref "R154")
      (value "100")
      (footprint "eagle-import:0207_10")
      (libsource (lib "eagle-import") (part "R-US_0207/10"))
    )
    (comp (ref "R155")
      (value "1K")
      (footprint "eagle-import:0207_10")
      (libsource (lib "eagle-import") (part "R-US_0207/10"))
    )
    (comp (ref "R156")
      (value "150")
      (footprint "eagle-import:0207_10")
      (libsource (lib "eagle-import") (part "R-US_0207/10"))
    )
    (comp (ref "R157")
      (value "3K")
      (footprint "eagle-import:0207_10")
      (libsource (lib "eagle-import") (part "R-US_0207/10"))
    )
    (comp (ref "R158")
      (value "15K")
      (footprint "eagle-import:0207_10")
      (libsource (lib "eagle-import") (part "R-US_0207/10"))
    )
    (comp (ref "R159")
      (value "15K")
      (footprint "eagle-import:0207_10")
      (libsource (lib "eagle-import") (part "R-US_0207/10"))
    )
    (comp (ref "R160")
      (value "15K")
      (footprint "eagle-import:0207_10")
      (libsource (lib "eagle-import") (part "R-US_0207/10"))
    )
    (comp (ref "R161")
      (value "1800")
      (footprint "eagle-import:0207_10")
      (libsource (lib "eagle-import") (part "R-US_0207/10"))
    )
    (comp (ref "R162")
      (value "470")
      (footprint "eagle-import:0207_10")
      (libsource (lib "eagle-import") (part "R-US_0207/10"))
    )
    (comp (ref "R163")
      (value "27")
      (footprint "eagle-import:0207_10")
      (libsource (lib "eagle-import") (part "R-US_0207/10"))
    )
    (comp (ref "R164")
      (value "470")
      (footprint "eagle-import:0207_10")
      (libsource (lib "eagle-import") (part "R-US_0207/10"))
    )
    (comp (ref "R165")
      (value "27")
      (footprint "eagle-import:0207_10")
      (libsource (lib "eagle-import") (part "R-US_0207/10"))
    )
    (comp (ref "R166")
      (value "1K")
      (footprint "eagle-import:0207_10")
      (libsource (lib "eagle-import") (part "R-US_0207/10"))
    )
    (comp (ref "R167")
      (value "470")
      (footprint "eagle-import:0207_10")
      (libsource (lib "eagle-import") (part "R-US_0207/10"))
    )
    (comp (ref "R168")
      (value "1K")
      (footprint "eagle-import:0207_10")
      (libsource (lib "eagle-import") (part "R-US_0207/10"))
    )
    (comp (ref "R169")
      (value "100")
      (footprint "eagle-import:0207_10")
      (libsource (lib "eagle-import") (part "R-US_0207/10"))
    )
    (comp (ref "R170")
      (value "470")
      (footprint "eagle-import:0207_10")
      (libsource (lib "eagle-import") (part "R-US_0207/10"))
    )
    (comp (ref "R171")
      (value "4.7K")
      (footprint "eagle-import:0207_10")
      (libsource (lib "eagle-import") (part "R-US_0207/10"))
    )
    (comp (ref "R172")
      (value "27")
      (footprint "eagle-import:0207_10")
      (libsource (lib "eagle-import") (part "R-US_0207/10"))
    )
    (comp (ref "R173")
      (value "4.7K")
      (footprint "eagle-import:0207_10")
      (libsource (lib "eagle-import") (part "R-US_0207/10"))
    )
    (comp (ref "R174")
      (value "27")
      (footprint "eagle-import:0207_10")
      (libsource (lib "eagle-import") (part "R-US_0207/10"))
    )
    (comp (ref "R175")
      (value "470")
      (footprint "eagle-import:0207_10")
      (libsource (lib "eagle-import") (part "R-US_0207/10"))
    )
    (comp (ref "S1")
      (value "CK102X06")
      (footprint "eagle-import:CK102X06")
      (libsource (lib "eagle-import") (part "CK102X06"))
    )
    (comp (ref "C1")
      (value "68pF")
      (footprint "eagle-import:C050-025X075")
      (libsource (lib "eagle-import") (part "C-US050-025X075"))
    )
    (comp (ref "C2")
      (value "68pF")
      (footprint "eagle-import:C050-025X075")
      (libsource (lib "eagle-import") (part "C-US050-025X075"))
    )
    (comp (ref "C3")
      (value "68pF")
      (footprint "eagle-import:C050-025X075")
      (libsource (lib "eagle-import") (part "C-US050-025X075"))
    )
    (comp (ref "C4")
      (value "68pF")
      (footprint "eagle-import:C050-025X075")
      (libsource (lib "eagle-import") (part "C-US050-025X075"))
    )
    (comp (ref "C5")
      (value "68pF")
      (footprint "eagle-import:C050-025X075")
      (libsource (lib "eagle-import") (part "C-US050-025X075"))
    )
    (comp (ref "C6")
      (value "68pF")
      (footprint "eagle-import:C050-025X075")
      (libsource (lib "eagle-import") (part "C-US050-025X075"))
    )
    (comp (ref "C7")
      (value "68pF")
      (footprint "eagle-import:C050-025X075")
      (libsource (lib "eagle-import") (part "C-US050-025X075"))
    )
    (comp (ref "C8")
      (value "68pF")
      (footprint "eagle-import:C050-025X075")
      (libsource (lib "eagle-import") (part "C-US050-025X075"))
    )
    (comp (ref "C9")
      (value "68pF")
      (footprint "eagle-import:C050-025X075")
      (libsource (lib "eagle-import") (part "C-US050-025X075"))
    )
    (comp (ref "C10")
      (value "68pF")
      (footprint "eagle-import:C050-025X075")
      (libsource (lib "eagle-import") (part "C-US050-025X075"))
    )
    (comp (ref "C11")
      (value "68pF")
      (footprint "eagle-import:C050-025X075")
      (libsource (lib "eagle-import") (part "C-US050-025X075"))
    )
    (comp (ref "C12")
      (value "68pF")
      (footprint "eagle-import:C050-025X075")
      (libsource (lib "eagle-import") (part "C-US050-025X075"))
    )
    (comp (ref "D1")
      (value "1N4154")
      (footprint "eagle-import:DO35-10")
      (libsource (lib "eagle-import") (part "1N4148DO35-10"))
    )
    (comp (ref "D2")
      (value "1N4154")
      (footprint "eagle-import:DO35-10")
      (libsource (lib "eagle-import") (part "1N4148DO35-10"))
    )
    (comp (ref "D3")
      (value "1N4154")
      (footprint "eagle-import:DO35-10")
      (libsource (lib "eagle-import") (part "1N4148DO35-10"))
    )
    (comp (ref "D4")
      (value "1N4154")
      (footprint "eagle-import:DO35-10")
      (libsource (lib "eagle-import") (part "1N4148DO35-10"))
    )
    (comp (ref "D5")
      (value "1N4154")
      (footprint "eagle-import:DO35-10")
      (libsource (lib "eagle-import") (part "1N4148DO35-10"))
    )
    (comp (ref "D6")
      (value "1N4154")
      (footprint "eagle-import:DO35-10")
      (libsource (lib "eagle-import") (part "1N4148DO35-10"))
    )
    (comp (ref "D7")
      (value "1N4154")
      (footprint "eagle-import:DO35-10")
      (libsource (lib "eagle-import") (part "1N4148DO35-10"))
    )
    (comp (ref "D8")
      (value "1N4154")
      (footprint "eagle-import:DO35-10")
      (libsource (lib "eagle-import") (part "1N4148DO35-10"))
    )
    (comp (ref "D9")
      (value "1N4154")
      (footprint "eagle-import:DO35-10")
      (libsource (lib "eagle-import") (part "1N4148DO35-10"))
    )
    (comp (ref "D10")
      (value "1N4154")
      (footprint "eagle-import:DO35-10")
      (libsource (lib "eagle-import") (part "1N4148DO35-10"))
    )
    (comp (ref "D11")
      (value "1N4154")
      (footprint "eagle-import:DO35-10")
      (libsource (lib "eagle-import") (part "1N4148DO35-10"))
    )
    (comp (ref "D12")
      (value "1N4154")
      (footprint "eagle-import:DO35-10")
      (libsource (lib "eagle-import") (part "1N4148DO35-10"))
    )
    (comp (ref "D13")
      (value "1N4154")
      (footprint "eagle-import:DO35-10")
      (libsource (lib "eagle-import") (part "1N4148DO35-10"))
    )
    (comp (ref "D14")
      (value "1N4154")
      (footprint "eagle-import:DO35-10")
      (libsource (lib "eagle-import") (part "1N4148DO35-10"))
    )
    (comp (ref "D15")
      (value "1N4154")
      (footprint "eagle-import:DO35-10")
      (libsource (lib "eagle-import") (part "1N4148DO35-10"))
    )
    (comp (ref "D16")
      (value "1N4154")
      (footprint "eagle-import:DO35-10")
      (libsource (lib "eagle-import") (part "1N4148DO35-10"))
    )
    (comp (ref "D17")
      (value "1N4154")
      (footprint "eagle-import:DO35-10")
      (libsource (lib "eagle-import") (part "1N4148DO35-10"))
    )
    (comp (ref "D18")
      (value "1N4154")
      (footprint "eagle-import:DO35-10")
      (libsource (lib "eagle-import") (part "1N4148DO35-10"))
    )
    (comp (ref "D19")
      (value "1N4154")
      (footprint "eagle-import:DO35-10")
      (libsource (lib "eagle-import") (part "1N4148DO35-10"))
    )
    (comp (ref "D20")
      (value "1N4154")
      (footprint "eagle-import:DO35-10")
      (libsource (lib "eagle-import") (part "1N4148DO35-10"))
    )
    (comp (ref "D21")
      (value "1N4154")
      (footprint "eagle-import:DO35-10")
      (libsource (lib "eagle-import") (part "1N4148DO35-10"))
    )
    (comp (ref "D22")
      (value "1N4154")
      (footprint "eagle-import:DO35-10")
      (libsource (lib "eagle-import") (part "1N4148DO35-10"))
    )
    (comp (ref "D23")
      (value "1N4154")
      (footprint "eagle-import:DO35-10")
      (libsource (lib "eagle-import") (part "1N4148DO35-10"))
    )
    (comp (ref "D24")
      (value "1N4154")
      (footprint "eagle-import:DO35-10")
      (libsource (lib "eagle-import") (part "1N4148DO35-10"))
    )
    (comp (ref "D25")
      (value "1N4154")
      (footprint "eagle-import:DO35-10")
      (libsource (lib "eagle-import") (part "1N4148DO35-10"))
    )
    (comp (ref "D26")
      (value "1N4154")
      (footprint "eagle-import:DO35-10")
      (libsource (lib "eagle-import") (part "1N4148DO35-10"))
    )
    (comp (ref "D27")
      (value "1N4154")
      (footprint "eagle-import:DO35-10")
      (libsource (lib "eagle-import") (part "1N4148DO35-10"))
    )
    (comp (ref "D28")
      (value "1N4154")
      (footprint "eagle-import:DO35-10")
      (libsource (lib "eagle-import") (part "1N4148DO35-10"))
    )
    (comp (ref "D29")
      (value "1N4154")
      (footprint "eagle-import:DO35-10")
      (libsource (lib "eagle-import") (part "1N4148DO35-10"))
    )
    (comp (ref "D30")
      (value "1N4154")
      (footprint "eagle-import:DO35-10")
      (libsource (lib "eagle-import") (part "1N4148DO35-10"))
    )
    (comp (ref "D31")
      (value "1N4154")
      (footprint "eagle-import:DO35-10")
      (libsource (lib "eagle-import") (part "1N4148DO35-10"))
    )
    (comp (ref "D32")
      (value "1N4154")
      (footprint "eagle-import:DO35-10")
      (libsource (lib "eagle-import") (part "1N4148DO35-10"))
    )
    (comp (ref "D33")
      (value "1N4154")
      (footprint "eagle-import:DO35-10")
      (libsource (lib "eagle-import") (part "1N4148DO35-10"))
    )
    (comp (ref "D34")
      (value "1N4154")
      (footprint "eagle-import:DO35-10")
      (libsource (lib "eagle-import") (part "1N4148DO35-10"))
    )
    (comp (ref "D35")
      (value "1N4154")
      (footprint "eagle-import:DO35-10")
      (libsource (lib "eagle-import") (part "1N4148DO35-10"))
    )
    (comp (ref "D36")
      (value "1N4154")
      (footprint "eagle-import:DO35-10")
      (libsource (lib "eagle-import") (part "1N4148DO35-10"))
    )
    (comp (ref "D37")
      (value "1N4154")
      (footprint "eagle-import:DO35-10")
      (libsource (lib "eagle-import") (part "1N4148DO35-10"))
    )
    (comp (ref "D38")
      (value "1N4154")
      (footprint "eagle-import:DO35-10")
      (libsource (lib "eagle-import") (part "1N4148DO35-10"))
    )
    (comp (ref "D39")
      (value "1N4154")
      (footprint "eagle-import:DO35-10")
      (libsource (lib "eagle-import") (part "1N4148DO35-10"))
    )
    (comp (ref "D40")
      (value "1N4154")
      (footprint "eagle-import:DO35-10")
      (libsource (lib "eagle-import") (part "1N4148DO35-10"))
    )
    (comp (ref "D41")
      (value "1N4154")
      (footprint "eagle-import:DO35-10")
      (libsource (lib "eagle-import") (part "1N4148DO35-10"))
    )
    (comp (ref "D42")
      (value "1N4154")
      (footprint "eagle-import:DO35-10")
      (libsource (lib "eagle-import") (part "1N4148DO35-10"))
    )
    (comp (ref "D43")
      (value "1N4154")
      (footprint "eagle-import:DO35-10")
      (libsource (lib "eagle-import") (part "1N4148DO35-10"))
    )
    (comp (ref "D44")
      (value "1N4154")
      (footprint "eagle-import:DO35-10")
      (libsource (lib "eagle-import") (part "1N4148DO35-10"))
    )
    (comp (ref "D45")
      (value "1N4154")
      (footprint "eagle-import:DO35-10")
      (libsource (lib "eagle-import") (part "1N4148DO35-10"))
    )
    (comp (ref "D46")
      (value "1N4154")
      (footprint "eagle-import:DO35-10")
      (libsource (lib "eagle-import") (part "1N4148DO35-10"))
    )
    (comp (ref "D47")
      (value "1N4154")
      (footprint "eagle-import:DO35-10")
      (libsource (lib "eagle-import") (part "1N4148DO35-10"))
    )
    (comp (ref "D48")
      (value "1N4154")
      (footprint "eagle-import:DO35-10")
      (libsource (lib "eagle-import") (part "1N4148DO35-10"))
    )
    (comp (ref "D49")
      (value "1N4154")
      (footprint "eagle-import:DO35-10")
      (libsource (lib "eagle-import") (part "1N4148DO35-10"))
    )
    (comp (ref "D50")
      (value "1N4154")
      (footprint "eagle-import:DO35-10")
      (libsource (lib "eagle-import") (part "1N4148DO35-10"))
    )
    (comp (ref "D51")
      (value "1N4154")
      (footprint "eagle-import:DO35-10")
      (libsource (lib "eagle-import") (part "1N4148DO35-10"))
    )
    (comp (ref "D52")
      (value "1N4154")
      (footprint "eagle-import:DO35-10")
      (libsource (lib "eagle-import") (part "1N4148DO35-10"))
    )
    (comp (ref "D53")
      (value "1N4154")
      (footprint "eagle-import:DO35-10")
      (libsource (lib "eagle-import") (part "1N4148DO35-10"))
    )
    (comp (ref "D54")
      (value "1N4154")
      (footprint "eagle-import:DO35-10")
      (libsource (lib "eagle-import") (part "1N4148DO35-10"))
    )
    (comp (ref "D55")
      (value "1N4154")
      (footprint "eagle-import:DO35-10")
      (libsource (lib "eagle-import") (part "1N4148DO35-10"))
    )
    (comp (ref "D56")
      (value "1N4154")
      (footprint "eagle-import:DO35-10")
      (libsource (lib "eagle-import") (part "1N4148DO35-10"))
    )
    (comp (ref "D57")
      (value "1N4154")
      (footprint "eagle-import:DO35-10")
      (libsource (lib "eagle-import") (part "1N4148DO35-10"))
    )
    (comp (ref "D58")
      (value "1N4154")
      (footprint "eagle-import:DO35-10")
      (libsource (lib "eagle-import") (part "1N4148DO35-10"))
    )
    (comp (ref "D59")
      (value "1N4154")
      (footprint "eagle-import:DO35-10")
      (libsource (lib "eagle-import") (part "1N4148DO35-10"))
    )
    (comp (ref "D60")
      (value "1N4154")
      (footprint "eagle-import:DO35-10")
      (libsource (lib "eagle-import") (part "1N4148DO35-10"))
    )
    (comp (ref "D61")
      (value "1N4154")
      (footprint "eagle-import:DO35-10")
      (libsource (lib "eagle-import") (part "1N4148DO35-10"))
    )
    (comp (ref "D62")
      (value "1N4154")
      (footprint "eagle-import:DO35-10")
      (libsource (lib "eagle-import") (part "1N4148DO35-10"))
    )
    (comp (ref "D63")
      (value "1N4154")
      (footprint "eagle-import:DO35-10")
      (libsource (lib "eagle-import") (part "1N4148DO35-10"))
    )
    (comp (ref "D64")
      (value "1N4154")
      (footprint "eagle-import:DO35-10")
      (libsource (lib "eagle-import") (part "1N4148DO35-10"))
    )
    (comp (ref "D65")
      (value "1N4154")
      (footprint "eagle-import:DO35-10")
      (libsource (lib "eagle-import") (part "1N4148DO35-10"))
    )
    (comp (ref "D66")
      (value "1N4154")
      (footprint "eagle-import:DO35-10")
      (libsource (lib "eagle-import") (part "1N4148DO35-10"))
    )
    (comp (ref "D67")
      (value "1N4154")
      (footprint "eagle-import:DO35-10")
      (libsource (lib "eagle-import") (part "1N4148DO35-10"))
    )
    (comp (ref "D68")
      (value "1N4154")
      (footprint "eagle-import:DO35-10")
      (libsource (lib "eagle-import") (part "1N4148DO35-10"))
    )
    (comp (ref "D69")
      (value "1N4154")
      (footprint "eagle-import:DO35-10")
      (libsource (lib "eagle-import") (part "1N4148DO35-10"))
    )
    (comp (ref "D70")
      (value "1N4154")
      (footprint "eagle-import:DO35-10")
      (libsource (lib "eagle-import") (part "1N4148DO35-10"))
    )
    (comp (ref "D71")
      (value "1N4154")
      (footprint "eagle-import:DO35-10")
      (libsource (lib "eagle-import") (part "1N4148DO35-10"))
    )
    (comp (ref "D72")
      (value "1N4154")
      (footprint "eagle-import:DO35-10")
      (libsource (lib "eagle-import") (part "1N4148DO35-10"))
    )
    (comp (ref "D73")
      (value "1N4154")
      (footprint "eagle-import:DO35-10")
      (libsource (lib "eagle-import") (part "1N4148DO35-10"))
    )
    (comp (ref "D74")
      (value "1N4154")
      (footprint "eagle-import:DO35-10")
      (libsource (lib "eagle-import") (part "1N4148DO35-10"))
    )
    (comp (ref "D75")
      (value "1N4154")
      (footprint "eagle-import:DO35-10")
      (libsource (lib "eagle-import") (part "1N4148DO35-10"))
    )
    (comp (ref "D76")
      (value "1N4154")
      (footprint "eagle-import:DO35-10")
      (libsource (lib "eagle-import") (part "1N4148DO35-10"))
    )
    (comp (ref "D77")
      (value "1N4154")
      (footprint "eagle-import:DO35-10")
      (libsource (lib "eagle-import") (part "1N4148DO35-10"))
    )
    (comp (ref "D78")
      (value "1N4154")
      (footprint "eagle-import:DO35-10")
      (libsource (lib "eagle-import") (part "1N4148DO35-10"))
    )
    (comp (ref "D79")
      (value "1N4154")
      (footprint "eagle-import:DO35-10")
      (libsource (lib "eagle-import") (part "1N4148DO35-10"))
    )
    (comp (ref "D80")
      (value "1N4154")
      (footprint "eagle-import:DO35-10")
      (libsource (lib "eagle-import") (part "1N4148DO35-10"))
    )
    (comp (ref "D81")
      (value "1N4154")
      (footprint "eagle-import:DO35-10")
      (libsource (lib "eagle-import") (part "1N4148DO35-10"))
    )
    (comp (ref "D82")
      (value "1N4154")
      (footprint "eagle-import:DO35-10")
      (libsource (lib "eagle-import") (part "1N4148DO35-10"))
    )
    (comp (ref "D83")
      (value "1N4154")
      (footprint "eagle-import:DO35-10")
      (libsource (lib "eagle-import") (part "1N4148DO35-10"))
    )
    (comp (ref "D84")
      (value "1N4154")
      (footprint "eagle-import:DO35-10")
      (libsource (lib "eagle-import") (part "1N4148DO35-10"))
    )
    (comp (ref "E18")
      (value "74HCT02N")
      (footprint "eagle-import:DIL14")
      (libsource (lib "eagle-import") (part "7402NLS"))
    )
    (comp (ref "E22")
      (value "74HCT02N")
      (footprint "eagle-import:DIL14")
      (libsource (lib "eagle-import") (part "7402NLS"))
    )
    (comp (ref "E26")
      (value "74HCT02N")
      (footprint "eagle-import:DIL14")
      (libsource (lib "eagle-import") (part "7402NLS"))
    )
    (comp (ref "I1")
      (value "CM7371")
      (footprint "eagle-import:BULB")
      (libsource (lib "eagle-import") (part "BULB"))
    )
    (comp (ref "I2")
      (value "CM7371")
      (footprint "eagle-import:BULB")
      (libsource (lib "eagle-import") (part "BULB"))
    )
    (comp (ref "I3")
      (value "CM7371")
      (footprint "eagle-import:BULB")
      (libsource (lib "eagle-import") (part "BULB"))
    )
    (comp (ref "I4")
      (value "CM7371")
      (footprint "eagle-import:BULB")
      (libsource (lib "eagle-import") (part "BULB"))
    )
    (comp (ref "I5")
      (value "CM7371")
      (footprint "eagle-import:BULB")
      (libsource (lib "eagle-import") (part "BULB"))
    )
    (comp (ref "I6")
      (value "CM7371")
      (footprint "eagle-import:BULB")
      (libsource (lib "eagle-import") (part "BULB"))
    )
    (comp (ref "I7")
      (value "CM7371")
      (footprint "eagle-import:BULB")
      (libsource (lib "eagle-import") (part "BULB"))
    )
    (comp (ref "I8")
      (value "CM7371")
      (footprint "eagle-import:BULB")
      (libsource (lib "eagle-import") (part "BULB"))
    )
    (comp (ref "I9")
      (value "CM7371")
      (footprint "eagle-import:BULB")
      (libsource (lib "eagle-import") (part "BULB"))
    )
    (comp (ref "I10")
      (value "CM7371")
      (footprint "eagle-import:BULB")
      (libsource (lib "eagle-import") (part "BULB"))
    )
    (comp (ref "I11")
      (value "CM7371")
      (footprint "eagle-import:BULB")
      (libsource (lib "eagle-import") (part "BULB"))
    )
    (comp (ref "I12")
      (value "CM7371")
      (footprint "eagle-import:BULB")
      (libsource (lib "eagle-import") (part "BULB"))
    )
    (comp (ref "Q1")
      (value "PN3569")
      (footprint "eagle-import:TO39")
      (libsource (lib "eagle-import") (part "2N3019"))
    )
    (comp (ref "Q2")
      (value "PN3569")
      (footprint "eagle-import:TO39")
      (libsource (lib "eagle-import") (part "2N3019"))
    )
    (comp (ref "Q3")
      (value "PN3569")
      (footprint "eagle-import:TO39")
      (libsource (lib "eagle-import") (part "2N3019"))
    )
    (comp (ref "Q4")
      (value "PN3569")
      (footprint "eagle-import:TO39")
      (libsource (lib "eagle-import") (part "2N3019"))
    )
    (comp (ref "Q5")
      (value "PN3569")
      (footprint "eagle-import:TO39")
      (libsource (lib "eagle-import") (part "2N3019"))
    )
    (comp (ref "Q6")
      (value "PN3569")
      (footprint "eagle-import:TO39")
      (libsource (lib "eagle-import") (part "2N3019"))
    )
    (comp (ref "Q7")
      (value "PN3569")
      (footprint "eagle-import:TO39")
      (libsource (lib "eagle-import") (part "2N3019"))
    )
    (comp (ref "Q8")
      (value "PN3569")
      (footprint "eagle-import:TO39")
      (libsource (lib "eagle-import") (part "2N3019"))
    )
    (comp (ref "Q9")
      (value "PN3569")
      (footprint "eagle-import:TO39")
      (libsource (lib "eagle-import") (part "2N3019"))
    )
    (comp (ref "Q10")
      (value "PN3569")
      (footprint "eagle-import:TO39")
      (libsource (lib "eagle-import") (part "2N3019"))
    )
    (comp (ref "Q11")
      (value "PN3569")
      (footprint "eagle-import:TO39")
      (libsource (lib "eagle-import") (part "2N3019"))
    )
    (comp (ref "Q12")
      (value "PN3569")
      (footprint "eagle-import:TO39")
      (libsource (lib "eagle-import") (part "2N3019"))
    )
    (comp (ref "R1")
      (value "15K")
      (footprint "eagle-import:0207_10")
      (libsource (lib "eagle-import") (part "R-US_0207/10"))
    )
    (comp (ref "R2")
      (value "15K")
      (footprint "eagle-import:0207_10")
      (libsource (lib "eagle-import") (part "R-US_0207/10"))
    )
    (comp (ref "R3")
      (value "15K")
      (footprint "eagle-import:0207_10")
      (libsource (lib "eagle-import") (part "R-US_0207/10"))
    )
    (comp (ref "R4")
      (value "15K")
      (footprint "eagle-import:0207_10")
      (libsource (lib "eagle-import") (part "R-US_0207/10"))
    )
    (comp (ref "R5")
      (value "15K")
      (footprint "eagle-import:0207_10")
      (libsource (lib "eagle-import") (part "R-US_0207/10"))
    )
    (comp (ref "R6")
      (value "15K")
      (footprint "eagle-import:0207_10")
      (libsource (lib "eagle-import") (part "R-US_0207/10"))
    )
    (comp (ref "R7")
      (value "15K")
      (footprint "eagle-import:0207_10")
      (libsource (lib "eagle-import") (part "R-US_0207/10"))
    )
    (comp (ref "R8")
      (value "15K")
      (footprint "eagle-import:0207_10")
      (libsource (lib "eagle-import") (part "R-US_0207/10"))
    )
    (comp (ref "R9")
      (value "15K")
      (footprint "eagle-import:0207_10")
      (libsource (lib "eagle-import") (part "R-US_0207/10"))
    )
    (comp (ref "R10")
      (value "15K")
      (footprint "eagle-import:0207_10")
      (libsource (lib "eagle-import") (part "R-US_0207/10"))
    )
    (comp (ref "R11")
      (value "15K")
      (footprint "eagle-import:0207_10")
      (libsource (lib "eagle-import") (part "R-US_0207/10"))
    )
    (comp (ref "R12")
      (value "15K")
      (footprint "eagle-import:0207_10")
      (libsource (lib "eagle-import") (part "R-US_0207/10"))
    )
    (comp (ref "R13")
      (value "33K")
      (footprint "eagle-import:0207_10")
      (libsource (lib "eagle-import") (part "R-US_0207/10"))
    )
    (comp (ref "R14")
      (value "33K")
      (footprint "eagle-import:0207_10")
      (libsource (lib "eagle-import") (part "R-US_0207/10"))
    )
    (comp (ref "R15")
      (value "33K")
      (footprint "eagle-import:0207_10")
      (libsource (lib "eagle-import") (part "R-US_0207/10"))
    )
    (comp (ref "R16")
      (value "33K")
      (footprint "eagle-import:0207_10")
      (libsource (lib "eagle-import") (part "R-US_0207/10"))
    )
    (comp (ref "R17")
      (value "33K")
      (footprint "eagle-import:0207_10")
      (libsource (lib "eagle-import") (part "R-US_0207/10"))
    )
    (comp (ref "R18")
      (value "33K")
      (footprint "eagle-import:0207_10")
      (libsource (lib "eagle-import") (part "R-US_0207/10"))
    )
    (comp (ref "R19")
      (value "33K")
      (footprint "eagle-import:0207_10")
      (libsource (lib "eagle-import") (part "R-US_0207/10"))
    )
    (comp (ref "R20")
      (value "33K")
      (footprint "eagle-import:0207_10")
      (libsource (lib "eagle-import") (part "R-US_0207/10"))
    )
    (comp (ref "R21")
      (value "33K")
      (footprint "eagle-import:0207_10")
      (libsource (lib "eagle-import") (part "R-US_0207/10"))
    )
    (comp (ref "R22")
      (value "33K")
      (footprint "eagle-import:0207_10")
      (libsource (lib "eagle-import") (part "R-US_0207/10"))
    )
    (comp (ref "R23")
      (value "33K")
      (footprint "eagle-import:0207_10")
      (libsource (lib "eagle-import") (part "R-US_0207/10"))
    )
    (comp (ref "R24")
      (value "33K")
      (footprint "eagle-import:0207_10")
      (libsource (lib "eagle-import") (part "R-US_0207/10"))
    )
    (comp (ref "R25")
      (value "390")
      (footprint "eagle-import:0207_10")
      (libsource (lib "eagle-import") (part "R-US_0207/10"))
    )
    (comp (ref "R26")
      (value "33K")
      (footprint "eagle-import:0207_10")
      (libsource (lib "eagle-import") (part "R-US_0207/10"))
    )
    (comp (ref "R27")
      (value "33K")
      (footprint "eagle-import:0207_10")
      (libsource (lib "eagle-import") (part "R-US_0207/10"))
    )
    (comp (ref "R28")
      (value "390")
      (footprint "eagle-import:0207_10")
      (libsource (lib "eagle-import") (part "R-US_0207/10"))
    )
    (comp (ref "R29")
      (value "33K")
      (footprint "eagle-import:0207_10")
      (libsource (lib "eagle-import") (part "R-US_0207/10"))
    )
    (comp (ref "R30")
      (value "33K")
      (footprint "eagle-import:0207_10")
      (libsource (lib "eagle-import") (part "R-US_0207/10"))
    )
    (comp (ref "R31")
      (value "390")
      (footprint "eagle-import:0207_10")
      (libsource (lib "eagle-import") (part "R-US_0207/10"))
    )
    (comp (ref "R32")
      (value "33K")
      (footprint "eagle-import:0207_10")
      (libsource (lib "eagle-import") (part "R-US_0207/10"))
    )
    (comp (ref "R33")
      (value "33K")
      (footprint "eagle-import:0207_10")
      (libsource (lib "eagle-import") (part "R-US_0207/10"))
    )
    (comp (ref "R34")
      (value "390")
      (footprint "eagle-import:0207_10")
      (libsource (lib "eagle-import") (part "R-US_0207/10"))
    )
    (comp (ref "R35")
      (value "33K")
      (footprint "eagle-import:0207_10")
      (libsource (lib "eagle-import") (part "R-US_0207/10"))
    )
    (comp (ref "R36")
      (value "33K")
      (footprint "eagle-import:0207_10")
      (libsource (lib "eagle-import") (part "R-US_0207/10"))
    )
    (comp (ref "R37")
      (value "390")
      (footprint "eagle-import:0207_10")
      (libsource (lib "eagle-import") (part "R-US_0207/10"))
    )
    (comp (ref "R38")
      (value "33K")
      (footprint "eagle-import:0207_10")
      (libsource (lib "eagle-import") (part "R-US_0207/10"))
    )
    (comp (ref "R39")
      (value "33K")
      (footprint "eagle-import:0207_10")
      (libsource (lib "eagle-import") (part "R-US_0207/10"))
    )
    (comp (ref "R40")
      (value "390")
      (footprint "eagle-import:0207_10")
      (libsource (lib "eagle-import") (part "R-US_0207/10"))
    )
    (comp (ref "R41")
      (value "33K")
      (footprint "eagle-import:0207_10")
      (libsource (lib "eagle-import") (part "R-US_0207/10"))
    )
    (comp (ref "R42")
      (value "33K")
      (footprint "eagle-import:0207_10")
      (libsource (lib "eagle-import") (part "R-US_0207/10"))
    )
    (comp (ref "R43")
      (value "390")
      (footprint "eagle-import:0207_10")
      (libsource (lib "eagle-import") (part "R-US_0207/10"))
    )
    (comp (ref "R44")
      (value "33K")
      (footprint "eagle-import:0207_10")
      (libsource (lib "eagle-import") (part "R-US_0207/10"))
    )
    (comp (ref "R45")
      (value "33K")
      (footprint "eagle-import:0207_10")
      (libsource (lib "eagle-import") (part "R-US_0207/10"))
    )
    (comp (ref "R46")
      (value "390")
      (footprint "eagle-import:0207_10")
      (libsource (lib "eagle-import") (part "R-US_0207/10"))
    )
    (comp (ref "R47")
      (value "33K")
      (footprint "eagle-import:0207_10")
      (libsource (lib "eagle-import") (part "R-US_0207/10"))
    )
    (comp (ref "R48")
      (value "33K")
      (footprint "eagle-import:0207_10")
      (libsource (lib "eagle-import") (part "R-US_0207/10"))
    )
    (comp (ref "R49")
      (value "390")
      (footprint "eagle-import:0207_10")
      (libsource (lib "eagle-import") (part "R-US_0207/10"))
    )
    (comp (ref "R50")
      (value "33K")
      (footprint "eagle-import:0207_10")
      (libsource (lib "eagle-import") (part "R-US_0207/10"))
    )
    (comp (ref "R51")
      (value "33K")
      (footprint "eagle-import:0207_10")
      (libsource (lib "eagle-import") (part "R-US_0207/10"))
    )
    (comp (ref "R52")
      (value "390")
      (footprint "eagle-import:0207_10")
      (libsource (lib "eagle-import") (part "R-US_0207/10"))
    )
    (comp (ref "R53")
      (value "33K")
      (footprint "eagle-import:0207_10")
      (libsource (lib "eagle-import") (part "R-US_0207/10"))
    )
    (comp (ref "R54")
      (value "33K")
      (footprint "eagle-import:0207_10")
      (libsource (lib "eagle-import") (part "R-US_0207/10"))
    )
    (comp (ref "R55")
      (value "390")
      (footprint "eagle-import:0207_10")
      (libsource (lib "eagle-import") (part "R-US_0207/10"))
    )
    (comp (ref "R56")
      (value "33K")
      (footprint "eagle-import:0207_10")
      (libsource (lib "eagle-import") (part "R-US_0207/10"))
    )
    (comp (ref "R57")
      (value "33K")
      (footprint "eagle-import:0207_10")
      (libsource (lib "eagle-import") (part "R-US_0207/10"))
    )
    (comp (ref "R58")
      (value "390")
      (footprint "eagle-import:0207_10")
      (libsource (lib "eagle-import") (part "R-US_0207/10"))
    )
    (comp (ref "R59")
      (value "33K")
      (footprint "eagle-import:0207_10")
      (libsource (lib "eagle-import") (part "R-US_0207/10"))
    )
    (comp (ref "R60")
      (value "33K")
      (footprint "eagle-import:0207_10")
      (libsource (lib "eagle-import") (part "R-US_0207/10"))
    )
    (comp (ref "R61")
      (value "33K")
      (footprint "eagle-import:0207_10")
      (libsource (lib "eagle-import") (part "R-US_0207/10"))
    )
    (comp (ref "R62")
      (value "33K")
      (footprint "eagle-import:0207_10")
      (libsource (lib "eagle-import") (part "R-US_0207/10"))
    )
    (comp (ref "R63")
      (value "33K")
      (footprint "eagle-import:0207_10")
      (libsource (lib "eagle-import") (part "R-US_0207/10"))
    )
    (comp (ref "R64")
      (value "33K")
      (footprint "eagle-import:0207_10")
      (libsource (lib "eagle-import") (part "R-US_0207/10"))
    )
    (comp (ref "R65")
      (value "33K")
      (footprint "eagle-import:0207_10")
      (libsource (lib "eagle-import") (part "R-US_0207/10"))
    )
    (comp (ref "R66")
      (value "33K")
      (footprint "eagle-import:0207_10")
      (libsource (lib "eagle-import") (part "R-US_0207/10"))
    )
    (comp (ref "R67")
      (value "33K")
      (footprint "eagle-import:0207_10")
      (libsource (lib "eagle-import") (part "R-US_0207/10"))
    )
    (comp (ref "R68")
      (value "33K")
      (footprint "eagle-import:0207_10")
      (libsource (lib "eagle-import") (part "R-US_0207/10"))
    )
    (comp (ref "R69")
      (value "33K")
      (footprint "eagle-import:0207_10")
      (libsource (lib "eagle-import") (part "R-US_0207/10"))
    )
    (comp (ref "R70")
      (value "33K")
      (footprint "eagle-import:0207_10")
      (libsource (lib "eagle-import") (part "R-US_0207/10"))
    )
    (comp (ref "R71")
      (value "33K")
      (footprint "eagle-import:0207_10")
      (libsource (lib "eagle-import") (part "R-US_0207/10"))
    )
    (comp (ref "R72")
      (value "33K")
      (footprint "eagle-import:0207_10")
      (libsource (lib "eagle-import") (part "R-US_0207/10"))
    )
    (comp (ref "R73")
      (value "33K")
      (footprint "eagle-import:0207_10")
      (libsource (lib "eagle-import") (part "R-US_0207/10"))
    )
    (comp (ref "R74")
      (value "33K")
      (footprint "eagle-import:0207_10")
      (libsource (lib "eagle-import") (part "R-US_0207/10"))
    )
    (comp (ref "R75")
      (value "33K")
      (footprint "eagle-import:0207_10")
      (libsource (lib "eagle-import") (part "R-US_0207/10"))
    )
    (comp (ref "R76")
      (value "33K")
      (footprint "eagle-import:0207_10")
      (libsource (lib "eagle-import") (part "R-US_0207/10"))
    )
    (comp (ref "R77")
      (value "33K")
      (footprint "eagle-import:0207_10")
      (libsource (lib "eagle-import") (part "R-US_0207/10"))
    )
    (comp (ref "R78")
      (value "33K")
      (footprint "eagle-import:0207_10")
      (libsource (lib "eagle-import") (part "R-US_0207/10"))
    )
    (comp (ref "R79")
      (value "33K")
      (footprint "eagle-import:0207_10")
      (libsource (lib "eagle-import") (part "R-US_0207/10"))
    )
    (comp (ref "R80")
      (value "33K")
      (footprint "eagle-import:0207_10")
      (libsource (lib "eagle-import") (part "R-US_0207/10"))
    )
    (comp (ref "R81")
      (value "33K")
      (footprint "eagle-import:0207_10")
      (libsource (lib "eagle-import") (part "R-US_0207/10"))
    )
    (comp (ref "R82")
      (value "33K")
      (footprint "eagle-import:0207_10")
      (libsource (lib "eagle-import") (part "R-US_0207/10"))
    )
    (comp (ref "R83")
      (value "33K")
      (footprint "eagle-import:0207_10")
      (libsource (lib "eagle-import") (part "R-US_0207/10"))
    )
    (comp (ref "R84")
      (value "33K")
      (footprint "eagle-import:0207_10")
      (libsource (lib "eagle-import") (part "R-US_0207/10"))
    )
  )
  (nets
    (net (code "1") (name "+0.75V") (class "Default")
      (node (ref "D125") (pin "C") (pinfunction "C_C") (pintype "passive"))
      (node (ref "D126") (pin "A") (pinfunction "A_A") (pintype "passive"))
      (node (ref "D130") (pin "C") (pinfunction "C_C") (pintype "passive"))
    )
    (net (code "2") (name "+3V3") (class "Default")
      (node (ref "C21") (pin "1") (pinfunction "1_1") (pintype "passive"))
      (node (ref "D117") (pin "C") (pinfunction "C_C") (pintype "passive"))
      (node (ref "D121") (pin "C") (pinfunction "C_C") (pintype "passive"))
      (node (ref "D123") (pin "A") (pinfunction "A_A") (pintype "passive"))
      (node (ref "R170") (pin "1") (pinfunction "1_1") (pintype "passive"))
    )
    (net (code "3") (name "+8V") (class "Default")
      (node (ref "C16") (pin "+") (pinfunction "+_+") (pintype "passive"))
      (node (ref "I1") (pin "B") (pinfunction "B_B") (pintype "passive"))
      (node (ref "I10") (pin "B") (pinfunction "B_B") (pintype "passive"))
      (node (ref "I11") (pin "B") (pinfunction "B_B") (pintype "passive"))
      (node (ref "I12") (pin "B") (pinfunction "B_B") (pintype "passive"))
      (node (ref "I13") (pin "B") (pinfunction "B_B") (pintype "passive"))
      (node (ref "I14") (pin "B") (pinfunction "B_B") (pintype "passive"))
      (node (ref "I15") (pin "B") (pinfunction "B_B") (pintype "passive"))
      (node (ref "I16") (pin "B") (pinfunction "B_B") (pintype "passive"))
      (node (ref "I17") (pin "B") (pinfunction "B_B") (pintype "passive"))
      (node (ref "I18") (pin "B") (pinfunction "B_B") (pintype "passive"))
      (node (ref "I19") (pin "B") (pinfunction "B_B") (pintype "passive"))
      (node (ref "I2") (pin "B") (pinfunction "B_B") (pintype "passive"))
      (node (ref "I20") (pin "B") (pinfunction "B_B") (pintype "passive"))
      (node (ref "I21") (pin "B") (pinfunction "B_B") (pintype "passive"))
      (node (ref "I22") (pin "B") (pinfunction "B_B") (pintype "passive"))
      (node (ref "I23") (pin "B") (pinfunction "B_B") (pintype "passive"))
      (node (ref "I24") (pin "B") (pinfunction "B_B") (pintype "passive"))
      (node (ref "I25") (pin "B") (pinfunction "B_B") (pintype "passive"))
      (node (ref "I26") (pin "B") (pinfunction "B_B") (pintype "passive"))
      (node (ref "I27") (pin "B") (pinfunction "B_B") (pintype "passive"))
      (node (ref "I3") (pin "B") (pinfunction "B_B") (pintype "passive"))
      (node (ref "I4") (pin "B") (pinfunction "B_B") (pintype "passive"))
      (node (ref "I5") (pin "B") (pinfunction "B_B") (pintype "passive"))
      (node (ref "I6") (pin "B") (pinfunction "B_B") (pintype "passive"))
      (node (ref "I7") (pin "B") (pinfunction "B_B") (pintype "passive"))
      (node (ref "I8") (pin "B") (pinfunction "B_B") (pintype "passive"))
      (node (ref "I9") (pin "B") (pinfunction "B_B") (pintype "passive"))
      (node (ref "YELLOW") (pin "1") (pinfunction "1_1") (pintype "passive"))
    )
    (net (code "4") (name "-15V") (class "Default")
      (node (ref "C17") (pin "-") (pinfunction "-_-") (pintype "passive"))
      (node (ref "C40") (pin "-") (pinfunction "-_-") (pintype "passive"))
      (node (ref "C41") (pin "-") (pinfunction "-_-") (pintype "passive"))
      (node (ref "I28") (pin "A") (pinfunction "A_A") (pintype "passive"))
      (node (ref "R158") (pin "1") (pinfunction "1_1") (pintype "passive"))
      (node (ref "S1") (pin "A") (pinfunction "A_A") (pintype "passive"))
      (node (ref "S11") (pin "2") (pinfunction "A2_2") (pintype "bidirectional"))
      (node (ref "S11") (pin "5") (pinfunction "B2_5") (pintype "bidirectional"))
      (node (ref "S12") (pin "2") (pinfunction "A2_2") (pintype "bidirectional"))
      (node (ref "S12") (pin "5") (pinfunction "B2_5") (pintype "bidirectional"))
      (node (ref "S13") (pin "2") (pinfunction "A2_2") (pintype "bidirectional"))
      (node (ref "S13") (pin "5") (pinfunction "B2_5") (pintype "bidirectional"))
      (node (ref "S14") (pin "2") (pinfunction "A2_2") (pintype "bidirectional"))
      (node (ref "S14") (pin "5") (pinfunction "B2_5") (pintype "bidirectional"))
      (node (ref "S15") (pin "2") (pinfunction "A2_2") (pintype "bidirectional"))
      (node (ref "S15") (pin "5") (pinfunction "B2_5") (pintype "bidirectional"))
      (node (ref "S16") (pin "2") (pinfunction "A2_2") (pintype "bidirectional"))
      (node (ref "S16") (pin "5") (pinfunction "B2_5") (pintype "bidirectional"))
      (node (ref "S17") (pin "2") (pinfunction "A2_2") (pintype "bidirectional"))
      (node (ref "S17") (pin "5") (pinfunction "B2_5") (pintype "bidirectional"))
      (node (ref "S18") (pin "2") (pinfunction "A2_2") (pintype "bidirectional"))
      (node (ref "S18") (pin "5") (pinfunction "B2_5") (pintype "bidirectional"))
      (node (ref "S19") (pin "2") (pinfunction "A2_2") (pintype "bidirectional"))
      (node (ref "S19") (pin "5") (pinfunction "B2_5") (pintype "bidirectional"))
      (node (ref "S20") (pin "2") (pinfunction "A2_2") (pintype "bidirectional"))
      (node (ref "S20") (pin "5") (pinfunction "B2_5") (pintype "bidirectional"))
      (node (ref "S21") (pin "2") (pinfunction "A2_2") (pintype "bidirectional"))
      (node (ref "S21") (pin "5") (pinfunction "B2_5") (pintype "bidirectional"))
      (node (ref "S22") (pin "2") (pinfunction "A2_2") (pintype "bidirectional"))
      (node (ref "S22") (pin "5") (pinfunction "B2_5") (pintype "bidirectional"))
      (node (ref "U$2") (pin "BB2") (pinfunction "1_BB2") (pintype "bidirectional"))
      (node (ref "U$2") (pin "CB2") (pinfunction "1_CB2") (pintype "bidirectional"))
      (node (ref "U$2") (pin "DB2") (pinfunction "1_DB2") (pintype "bidirectional"))
    )
    (net (code "5") (name "AC_EN") (class "Default")
      (node (ref "D107") (pin "C") (pinfunction "C_C") (pintype "passive"))
      (node (ref "D111") (pin "C") (pinfunction "C_C") (pintype "passive"))
      (node (ref "D112") (pin "C") (pinfunction "C_C") (pintype "passive"))
      (node (ref "R173") (pin "1") (pinfunction "1_1") (pintype "passive"))
      (node (ref "S1") (pin "A4") (pinfunction "A4_A4") (pintype "passive"))
    )
    (net (code "6") (name "BK_DATA_CONT") (class "Default")
      (node (ref "D80") (pin "A") (pinfunction "A_A") (pintype "passive"))
      (node (ref "E4") (pin "3") (pinfunction "O_3") (pintype "open_collector"))
      (node (ref "U$2") (pin "BK2") (pinfunction "1_BK2") (pintype "bidirectional"))
    )
    (net (code "7") (name "BREAK_C") (class "Default")
      (node (ref "D84") (pin "A") (pinfunction "A_A") (pintype "passive"))
      (node (ref "U$2") (pin "BL2") (pinfunction "1_BL2") (pintype "bidirectional"))
    )
    (net (code "8") (name "BRK_INP") (class "Default")
      (node (ref "D83") (pin "A") (pinfunction "A_A") (pintype "passive"))
      (node (ref "U$2") (pin "BE2") (pinfunction "1_BE2") (pintype "bidirectional"))
    )
    (net (code "9") (name "BUS_EN") (class "Default")
      (node (ref "D113") (pin "C") (pinfunction "C_C") (pintype "passive"))
      (node (ref "D129") (pin "C") (pinfunction "C_C") (pintype "passive"))
      (node (ref "R145") (pin "1") (pinfunction "1_1") (pintype "passive"))
      (node (ref "S1") (pin "A1") (pinfunction "A1_A1") (pintype "passive"))
    )
    (net (code "10") (name "CLR") (class "Default")
      (node (ref "D86") (pin "C") (pinfunction "C_C") (pintype "passive"))
      (node (ref "E10") (pin "5") (pinfunction "I_5") (pintype "input"))
      (node (ref "E14") (pin "13") (pinfunction "I3_13") (pintype "input"))
      (node (ref "R87") (pin "2") (pinfunction "2_2") (pintype "passive"))
    )
    (net (code "11") (name "CONT") (class "Default")
      (node (ref "D87") (pin "C") (pinfunction "C_C") (pintype "passive"))
      (node (ref "E5") (pin "5") (pinfunction "I2_5") (pintype "input"))
      (node (ref "R89") (pin "2") (pinfunction "2_2") (pintype "passive"))
    )
    (net (code "12") (name "CP_START") (class "Default")
      (node (ref "E1") (pin "2") (pinfunction "I1_2") (pintype "input"))
      (node (ref "E12") (pin "8") (pinfunction "O_8") (pintype "output"))
      (node (ref "E4") (pin "2") (pinfunction "I1_2") (pintype "input"))
      (node (ref "E4") (pin "5") (pinfunction "I1_5") (pintype "input"))
      (node (ref "E4") (pin "9") (pinfunction "I0_9") (pintype "input"))
      (node (ref "E5") (pin "13") (pinfunction "I2_13") (pintype "input"))
      (node (ref "E7") (pin "12") (pinfunction "I0_12") (pintype "input"))
      (node (ref "E8") (pin "5") (pinfunction "I2_5") (pintype "input"))
    )
    (net (code "13") (name "D") (class "Default")
      (node (ref "D74") (pin "A") (pinfunction "A_A") (pintype "passive"))
      (node (ref "U$2") (pin "DK2") (pinfunction "1_DK2") (pintype "bidirectional"))
    )
    (net (code "14") (name "DATA00") (class "Default")
      (node (ref "D61") (pin "A") (pinfunction "A_A") (pintype "passive"))
      (node (ref "E25") (pin "3") (pinfunction "O_3") (pintype "open_collector"))
      (node (ref "U$2") (pin "AR1") (pinfunction "1_AR1") (pintype "bidirectional"))
    )
    (net (code "15") (name "DATA01") (class "Default")
      (node (ref "D62") (pin "A") (pinfunction "A_A") (pintype "passive"))
      (node (ref "E25") (pin "6") (pinfunction "O_6") (pintype "open_collector"))
      (node (ref "U$2") (pin "AS1") (pinfunction "1_AS1") (pintype "bidirectional"))
    )
    (net (code "16") (name "DATA02") (class "Default")
      (node (ref "D63") (pin "A") (pinfunction "A_A") (pintype "passive"))
      (node (ref "E25") (pin "8") (pinfunction "O_8") (pintype "open_collector"))
      (node (ref "U$2") (pin "AU1") (pinfunction "1_AU1") (pintype "bidirectional"))
    )
    (net (code "17") (name "DATA03") (class "Default")
      (node (ref "D64") (pin "A") (pinfunction "A_A") (pintype "passive"))
      (node (ref "E25") (pin "11") (pinfunction "O_11") (pintype "open_collector"))
      (node (ref "U$2") (pin "AV1") (pinfunction "1_AV1") (pintype "bidirectional"))
    )
    (net (code "18") (name "DATA04") (class "Default")
      (node (ref "D65") (pin "A") (pinfunction "A_A") (pintype "passive"))
      (node (ref "E21") (pin "3") (pinfunction "O_3") (pintype "open_collector"))
      (node (ref "U$2") (pin "BR1") (pinfunction "1_BR1") (pintype "bidirectional"))
    )
    (net (code "19") (name "DATA05") (class "Default")
      (node (ref "D66") (pin "A") (pinfunction "A_A") (pintype "passive"))
      (node (ref "E21") (pin "6") (pinfunction "O_6") (pintype "open_collector"))
      (node (ref "U$2") (pin "BS1") (pinfunction "1_BS1") (pintype "bidirectional"))
    )
    (net (code "20") (name "DATA06") (class "Default")
      (node (ref "D67") (pin "A") (pinfunction "A_A") (pintype "passive"))
      (node (ref "E21") (pin "8") (pinfunction "O_8") (pintype "open_collector"))
      (node (ref "U$2") (pin "BU1") (pinfunction "1_BU1") (pintype "bidirectional"))
    )
    (net (code "21") (name "DATA07") (class "Default")
      (node (ref "D68") (pin "A") (pinfunction "A_A") (pintype "passive"))
      (node (ref "E21") (pin "11") (pinfunction "O_11") (pintype "open_collector"))
      (node (ref "U$2") (pin "BV1") (pinfunction "1_BV1") (pintype "bidirectional"))
    )
    (net (code "22") (name "DATA08") (class "Default")
      (node (ref "D69") (pin "A") (pinfunction "A_A") (pintype "passive"))
      (node (ref "E17") (pin "3") (pinfunction "O_3") (pintype "open_collector"))
      (node (ref "U$2") (pin "DR1") (pinfunction "1_DR1") (pintype "bidirectional"))
    )
    (net (code "23") (name "DATA09") (class "Default")
      (node (ref "D70") (pin "A") (pinfunction "A_A") (pintype "passive"))
      (node (ref "E17") (pin "6") (pinfunction "O_6") (pintype "open_collector"))
      (node (ref "U$2") (pin "DS1") (pinfunction "1_DS1") (pintype "bidirectional"))
    )
    (net (code "24") (name "DATA10") (class "Default")
      (node (ref "D71") (pin "A") (pinfunction "A_A") (pintype "passive"))
      (node (ref "E17") (pin "11") (pinfunction "O_11") (pintype "open_collector"))
      (node (ref "U$2") (pin "DU1") (pinfunction "1_DU1") (pintype "bidirectional"))
    )
    (net (code "25") (name "DATA11") (class "Default")
      (node (ref "D72") (pin "A") (pinfunction "A_A") (pintype "passive"))
      (node (ref "E17") (pin "8") (pinfunction "O_8") (pintype "open_collector"))
      (node (ref "U$2") (pin "DV1") (pinfunction "1_DV1") (pintype "bidirectional"))
    )
    (net (code "26") (name "DATA_EN") (class "Default")
      (node (ref "D106") (pin "A") (pinfunction "A_A") (pintype "passive"))
      (node (ref "D107") (pin "A") (pinfunction "A_A") (pintype "passive"))
      (node (ref "D108") (pin "A") (pinfunction "A_A") (pintype "passive"))
      (node (ref "D129") (pin "A") (pinfunction "A_A") (pintype "passive"))
      (node (ref "R62") (pin "2") (pinfunction "2_2") (pintype "passive"))
      (node (ref "R64") (pin "2") (pinfunction "2_2") (pintype "passive"))
      (node (ref "R66") (pin "2") (pinfunction "2_2") (pintype "passive"))
      (node (ref "R68") (pin "2") (pinfunction "2_2") (pintype "passive"))
      (node (ref "R70") (pin "2") (pinfunction "2_2") (pintype "passive"))
      (node (ref "R72") (pin "2") (pinfunction "2_2") (pintype "passive"))
      (node (ref "R74") (pin "2") (pinfunction "2_2") (pintype "passive"))
      (node (ref "R76") (pin "2") (pinfunction "2_2") (pintype "passive"))
      (node (ref "R78") (pin "2") (pinfunction "2_2") (pintype "passive"))
      (node (ref "R80") (pin "2") (pinfunction "2_2") (pintype "passive"))
      (node (ref "R82") (pin "2") (pinfunction "2_2") (pintype "passive"))
      (node (ref "R84") (pin "2") (pinfunction "2_2") (pintype "passive"))
    )
    (net (code "27") (name "DEP") (class "Default")
      (node (ref "D90") (pin "C") (pinfunction "C_C") (pintype "passive"))
      (node (ref "E5") (pin "3") (pinfunction "I0_3") (pintype "input"))
      (node (ref "E6") (pin "10") (pinfunction "I1_10") (pintype "input"))
      (node (ref "E8") (pin "11") (pinfunction "I2_11") (pintype "input"))
      (node (ref "E8") (pin "13") (pinfunction "I2_13") (pintype "input"))
      (node (ref "R95") (pin "2") (pinfunction "2_2") (pintype "passive"))
    )
    (net (code "28") (name "DEP+EXAM+CONT") (class "Default")
      (node (ref "E1") (pin "13") (pinfunction "I1_13") (pintype "input"))
      (node (ref "E10") (pin "3") (pinfunction "I_3") (pintype "input"))
      (node (ref "E5") (pin "6") (pinfunction "O_6") (pintype "output"))
    )
    (net (code "29") (name "E") (class "Default")
      (node (ref "D75") (pin "A") (pinfunction "A_A") (pintype "passive"))
      (node (ref "U$2") (pin "DL2") (pinfunction "1_DL2") (pintype "bidirectional"))
    )
    (net (code "30") (name "EMA0") (class "Default")
      (node (ref "E28") (pin "9") (pinfunction "I1_9") (pintype "input"))
      (node (ref "U$2") (pin "AD2") (pinfunction "1_AD2") (pintype "bidirectional"))
    )
    (net (code "31") (name "EMA1") (class "Default")
      (node (ref "E28") (pin "12") (pinfunction "I1_12") (pintype "input"))
      (node (ref "U$2") (pin "AE2") (pinfunction "1_AE2") (pintype "bidirectional"))
    )
    (net (code "32") (name "EMA2") (class "Default")
      (node (ref "E28") (pin "2") (pinfunction "I0_2") (pintype "input"))
      (node (ref "U$2") (pin "AH2") (pinfunction "1_AH2") (pintype "bidirectional"))
    )
    (net (code "33") (name "EXAM") (class "Default")
      (node (ref "D89") (pin "C") (pinfunction "C_C") (pintype "passive"))
      (node (ref "E5") (pin "4") (pinfunction "I1_4") (pintype "input"))
      (node (ref "E6") (pin "1") (pinfunction "I0_1") (pintype "input"))
      (node (ref "E8") (pin "2") (pinfunction "I1_2") (pintype "input"))
      (node (ref "R93") (pin "2") (pinfunction "2_2") (pintype "passive"))
    )
    (net (code "34") (name "EXT_LOAD") (class "Default")
      (node (ref "D91") (pin "C") (pinfunction "C_C") (pintype "passive"))
      (node (ref "E12") (pin "5") (pinfunction "I1_5") (pintype "input"))
      (node (ref "E14") (pin "9") (pinfunction "I0_9") (pintype "input"))
      (node (ref "E8") (pin "1") (pinfunction "I0_1") (pintype "input"))
      (node (ref "E8") (pin "10") (pinfunction "I1_10") (pintype "input"))
      (node (ref "R97") (pin "2") (pinfunction "2_2") (pintype "passive"))
    )
    (net (code "35") (name "FETCH") (class "Default")
      (node (ref "D73") (pin "A") (pinfunction "A_A") (pintype "passive"))
      (node (ref "E2") (pin "6") (pinfunction "I1_6") (pintype "input"))
      (node (ref "U$2") (pin "DJ2") (pinfunction "1_DJ2") (pintype "bidirectional"))
    )
    (net (code "36") (name "FSET") (class "Default")
      (node (ref "E11") (pin "9") (pinfunction "I0_9") (pintype "input"))
      (node (ref "U$2") (pin "DP2") (pinfunction "1_DP2") (pintype "bidirectional"))
    )
    (net (code "37") (name "GND") (class "Default")
      (node (ref "C13") (pin "-") (pinfunction "-_-") (pintype "passive"))
      (node (ref "C16") (pin "-") (pinfunction "-_-") (pintype "passive"))
      (node (ref "C17") (pin "+") (pinfunction "+_+") (pintype "passive"))
      (node (ref "C18") (pin "-") (pinfunction "-_-") (pintype "passive"))
      (node (ref "C19") (pin "-") (pinfunction "-_-") (pintype "passive"))
      (node (ref "C20") (pin "-") (pinfunction "-_-") (pintype "passive"))
      (node (ref "C21") (pin "2") (pinfunction "2_2") (pintype "passive"))
      (node (ref "C22") (pin "2") (pinfunction "2_2") (pintype "passive"))
      (node (ref "C23") (pin "2") (pinfunction "2_2") (pintype "passive"))
      (node (ref "C24") (pin "2") (pinfunction "2_2") (pintype "passive"))
      (node (ref "C25") (pin "2") (pinfunction "2_2") (pintype "passive"))
      (node (ref "C26") (pin "2") (pinfunction "2_2") (pintype "passive"))
      (node (ref "C27") (pin "2") (pinfunction "2_2") (pintype "passive"))
      (node (ref "C28") (pin "2") (pinfunction "2_2") (pintype "passive"))
      (node (ref "C29") (pin "2") (pinfunction "2_2") (pintype "passive"))
      (node (ref "C30") (pin "2") (pinfunction "2_2") (pintype "passive"))
      (node (ref "C31") (pin "2") (pinfunction "2_2") (pintype "passive"))
      (node (ref "C32") (pin "2") (pinfunction "2_2") (pintype "passive"))
      (node (ref "C33") (pin "2") (pinfunction "2_2") (pintype "passive"))
      (node (ref "C34") (pin "2") (pinfunction "2_2") (pintype "passive"))
      (node (ref "C35") (pin "2") (pinfunction "2_2") (pintype "passive"))
      (node (ref "C36") (pin "2") (pinfunction "2_2") (pintype "passive"))
      (node (ref "C37") (pin "2") (pinfunction "2_2") (pintype "passive"))
      (node (ref "C38") (pin "2") (pinfunction "2_2") (pintype "passive"))
      (node (ref "C39") (pin "2") (pinfunction "2_2") (pintype "passive"))
      (node (ref "C40") (pin "+") (pinfunction "+_+") (pintype "passive"))
      (node (ref "C41") (pin "+") (pinfunction "+_+") (pintype "passive"))
      (node (ref "D100") (pin "A") (pinfunction "A_A") (pintype "passive"))
      (node (ref "D101") (pin "A") (pinfunction "A_A") (pintype "passive"))
      (node (ref "D102") (pin "A") (pinfunction "A_A") (pintype "passive"))
      (node (ref "D103") (pin "A") (pinfunction "A_A") (pintype "passive"))
      (node (ref "D104") (pin "A") (pinfunction "A_A") (pintype "passive"))
      (node (ref "D105") (pin "A") (pinfunction "A_A") (pintype "passive"))
      (node (ref "D109") (pin "A") (pinfunction "A_A") (pintype "passive"))
      (node (ref "D114") (pin "A") (pinfunction "A_A") (pintype "passive"))
      (node (ref "D115") (pin "A") (pinfunction "A_A") (pintype "passive"))
      (node (ref "D119") (pin "A") (pinfunction "A_A") (pintype "passive"))
      (node (ref "D126") (pin "C") (pinfunction "C_C") (pintype "passive"))
      (node (ref "D127") (pin "A") (pinfunction "A_A") (pintype "passive"))
      (node (ref "D128") (pin "A") (pinfunction "A_A") (pintype "passive"))
      (node (ref "D85") (pin "A") (pinfunction "A_A") (pintype "passive"))
      (node (ref "D86") (pin "A") (pinfunction "A_A") (pintype "passive"))
      (node (ref "D87") (pin "A") (pinfunction "A_A") (pintype "passive"))
      (node (ref "D88") (pin "A") (pinfunction "A_A") (pintype "passive"))
      (node (ref "D89") (pin "A") (pinfunction "A_A") (pintype "passive"))
      (node (ref "D90") (pin "A") (pinfunction "A_A") (pintype "passive"))
      (node (ref "D91") (pin "A") (pinfunction "A_A") (pintype "passive"))
      (node (ref "D92") (pin "A") (pinfunction "A_A") (pintype "passive"))
      (node (ref "D93") (pin "A") (pinfunction "A_A") (pintype "passive"))
      (node (ref "D94") (pin "A") (pinfunction "A_A") (pintype "passive"))
      (node (ref "D95") (pin "A") (pinfunction "A_A") (pintype "passive"))
      (node (ref "D96") (pin "A") (pinfunction "A_A") (pintype "passive"))
      (node (ref "D97") (pin "A") (pinfunction "A_A") (pintype "passive"))
      (node (ref "D98") (pin "A") (pinfunction "A_A") (pintype "passive"))
      (node (ref "D99") (pin "A") (pinfunction "A_A") (pintype "passive"))
      (node (ref "E11") (pin "13") (pinfunction "I1_13") (pintype "input"))
      (node (ref "E13") (pin "2") (pinfunction "I0_2") (pintype "input"))
      (node (ref "E13") (pin "6") (pinfunction "I1_6") (pintype "input"))
      (node (ref "E15") (pin "1") (pinfunction "I0_1") (pintype "input"))
      (node (ref "E16") (pin "12") (pinfunction "I1_12") (pintype "input"))
      (node (ref "E16") (pin "2") (pinfunction "I0_2") (pintype "input"))
      (node (ref "E16") (pin "6") (pinfunction "I1_6") (pintype "input"))
      (node (ref "E16") (pin "9") (pinfunction "I1_9") (pintype "input"))
      (node (ref "E2") (pin "12") (pinfunction "I1_12") (pintype "input"))
      (node (ref "E2") (pin "3") (pinfunction "I1_3") (pintype "input"))
      (node (ref "E20") (pin "12") (pinfunction "I1_12") (pintype "input"))
      (node (ref "E20") (pin "3") (pinfunction "I1_3") (pintype "input"))
      (node (ref "E20") (pin "6") (pinfunction "I1_6") (pintype "input"))
      (node (ref "E20") (pin "9") (pinfunction "I1_9") (pintype "input"))
      (node (ref "E24") (pin "11") (pinfunction "I0_11") (pintype "input"))
      (node (ref "E24") (pin "3") (pinfunction "I1_3") (pintype "input"))
      (node (ref "E24") (pin "6") (pinfunction "I1_6") (pintype "input"))
      (node (ref "E24") (pin "8") (pinfunction "I0_8") (pintype "input"))
      (node (ref "E28") (pin "11") (pinfunction "I0_11") (pintype "input"))
      (node (ref "E28") (pin "3") (pinfunction "I1_3") (pintype "input"))
      (node (ref "E28") (pin "8") (pinfunction "I0_8") (pintype "input"))
      (node (ref "Q1") (pin "1") (pinfunction "E_1") (pintype "passive"))
      (node (ref "Q10") (pin "1") (pinfunction "E_1") (pintype "passive"))
      (node (ref "Q11") (pin "1") (pinfunction "E_1") (pintype "passive"))
      (node (ref "Q12") (pin "1") (pinfunction "E_1") (pintype "passive"))
      (node (ref "Q13") (pin "3") (pinfunction "C_3") (pintype "passive"))
      (node (ref "Q19") (pin "1") (pinfunction "E_1") (pintype "passive"))
      (node (ref "Q2") (pin "1") (pinfunction "E_1") (pintype "passive"))
      (node (ref "Q3") (pin "1") (pinfunction "E_1") (pintype "passive"))
      (node (ref "Q4") (pin "1") (pinfunction "E_1") (pintype "passive"))
      (node (ref "Q5") (pin "1") (pinfunction "E_1") (pintype "passive"))
      (node (ref "Q6") (pin "1") (pinfunction "E_1") (pintype "passive"))
      (node (ref "Q7") (pin "1") (pinfunction "E_1") (pintype "passive"))
      (node (ref "Q8") (pin "1") (pinfunction "E_1") (pintype "passive"))
      (node (ref "Q9") (pin "1") (pinfunction "E_1") (pintype "passive"))
      (node (ref "R127") (pin "1") (pinfunction "1_1") (pintype "passive"))
      (node (ref "R128") (pin "1") (pinfunction "1_1") (pintype "passive"))
      (node (ref "R129") (pin "1") (pinfunction "1_1") (pintype "passive"))
      (node (ref "R130") (pin "1") (pinfunction "1_1") (pintype "passive"))
      (node (ref "R131") (pin "1") (pinfunction "1_1") (pintype "passive"))
      (node (ref "R132") (pin "1") (pinfunction "1_1") (pintype "passive"))
      (node (ref "R133") (pin "1") (pinfunction "1_1") (pintype "passive"))
      (node (ref "R134") (pin "1") (pinfunction "1_1") (pintype "passive"))
      (node (ref "R135") (pin "1") (pinfunction "1_1") (pintype "passive"))
      (node (ref "R136") (pin "1") (pinfunction "1_1") (pintype "passive"))
      (node (ref "R137") (pin "1") (pinfunction "1_1") (pintype "passive"))
      (node (ref "R138") (pin "1") (pinfunction "1_1") (pintype "passive"))
      (node (ref "R139") (pin "1") (pinfunction "1_1") (pintype "passive"))
      (node (ref "R140") (pin "1") (pinfunction "1_1") (pintype "passive"))
      (node (ref "R141") (pin "1") (pinfunction "1_1") (pintype "passive"))
      (node (ref "R157") (pin "1") (pinfunction "1_1") (pintype "passive"))
      (node (ref "R159") (pin "1") (pinfunction "1_1") (pintype "passive"))
      (node (ref "R160") (pin "1") (pinfunction "1_1") (pintype "passive"))
      (node (ref "R25") (pin "1") (pinfunction "1_1") (pintype "passive"))
      (node (ref "R28") (pin "1") (pinfunction "1_1") (pintype "passive"))
      (node (ref "R31") (pin "1") (pinfunction "1_1") (pintype "passive"))
      (node (ref "R34") (pin "1") (pinfunction "1_1") (pintype "passive"))
      (node (ref "R37") (pin "1") (pinfunction "1_1") (pintype "passive"))
      (node (ref "R40") (pin "1") (pinfunction "1_1") (pintype "passive"))
      (node (ref "R43") (pin "1") (pinfunction "1_1") (pintype "passive"))
      (node (ref "R46") (pin "1") (pinfunction "1_1") (pintype "passive"))
      (node (ref "R49") (pin "1") (pinfunction "1_1") (pintype "passive"))
      (node (ref "R52") (pin "1") (pinfunction "1_1") (pintype "passive"))
      (node (ref "R55") (pin "1") (pinfunction "1_1") (pintype "passive"))
      (node (ref "R58") (pin "1") (pinfunction "1_1") (pintype "passive"))
      (node (ref "U$2") (pin "AC2") (pinfunction "1_AC2") (pintype "bidirectional"))
      (node (ref "U$2") (pin "AF1") (pinfunction "1_AF1") (pintype "bidirectional"))
      (node (ref "U$2") (pin "AF2") (pinfunction "1_AF2") (pintype "bidirectional"))
      (node (ref "U$2") (pin "AN1") (pinfunction "1_AN1") (pintype "bidirectional"))
      (node (ref "U$2") (pin "AN2") (pinfunction "1_AN2") (pintype "bidirectional"))
      (node (ref "U$2") (pin "AT1") (pinfunction "1_AT1") (pintype "bidirectional"))
      (node (ref "U$2") (pin "AT2") (pinfunction "1_AT2") (pintype "bidirectional"))
      (node (ref "U$2") (pin "BC1") (pinfunction "1_BC1") (pintype "bidirectional"))
      (node (ref "U$2") (pin "BC2") (pinfunction "1_BC2") (pintype "bidirectional"))
      (node (ref "U$2") (pin "BF1") (pinfunction "1_BF1") (pintype "bidirectional"))
      (node (ref "U$2") (pin "BF2") (pinfunction "1_BF2") (pintype "bidirectional"))
      (node (ref "U$2") (pin "BN1") (pinfunction "1_BN1") (pintype "bidirectional"))
      (node (ref "U$2") (pin "BN2") (pinfunction "1_BN2") (pintype "bidirectional"))
      (node (ref "U$2") (pin "BT1") (pinfunction "1_BT1") (pintype "bidirectional"))
      (node (ref "U$2") (pin "BT2") (pinfunction "1_BT2") (pintype "bidirectional"))
      (node (ref "U$2") (pin "CC1") (pinfunction "1_CC1") (pintype "bidirectional"))
      (node (ref "U$2") (pin "CC2") (pinfunction "1_CC2") (pintype "bidirectional"))
      (node (ref "U$2") (pin "CF1") (pinfunction "1_CF1") (pintype "bidirectional"))
      (node (ref "U$2") (pin "CF2") (pinfunction "1_CF2") (pintype "bidirectional"))
      (node (ref "U$2") (pin "CN1") (pinfunction "1_CN1") (pintype "bidirectional"))
      (node (ref "U$2") (pin "CN2") (pinfunction "1_CN2") (pintype "bidirectional"))
      (node (ref "U$2") (pin "CT1") (pinfunction "1_CT1") (pintype "bidirectional"))
      (node (ref "U$2") (pin "CT2") (pinfunction "1_CT2") (pintype "bidirectional"))
      (node (ref "U$2") (pin "DC1") (pinfunction "1_DC1") (pintype "bidirectional"))
      (node (ref "U$2") (pin "DC2") (pinfunction "1_DC2") (pintype "bidirectional"))
      (node (ref "U$2") (pin "DF1") (pinfunction "1_DF1") (pintype "bidirectional"))
      (node (ref "U$2") (pin "DF2") (pinfunction "1_DF2") (pintype "bidirectional"))
      (node (ref "U$2") (pin "DT1") (pinfunction "1_DT1") (pintype "bidirectional"))
      (node (ref "U$2") (pin "DT2") (pinfunction "1_DT2") (pintype "bidirectional"))
    )
    (net (code "38") (name "HALT") (class "Default")
      (node (ref "D93") (pin "C") (pinfunction "C_C") (pintype "passive"))
      (node (ref "E11") (pin "10") (pinfunction "I1_10") (pintype "input"))
      (node (ref "R101") (pin "2") (pinfunction "2_2") (pintype "passive"))
    )
    (net (code "39") (name "IND1") (class "Default")
      (node (ref "E7") (pin "3") (pinfunction "O_3") (pintype "open_collector"))
      (node (ref "E7") (pin "6") (pinfunction "O_6") (pintype "open_collector"))
      (node (ref "U$2") (pin "CU2") (pinfunction "1_CU2") (pintype "bidirectional"))
    )
    (net (code "40") (name "IND2") (class "Default")
      (node (ref "E7") (pin "8") (pinfunction "O_8") (pintype "open_collector"))
      (node (ref "U$2") (pin "CV2") (pinfunction "1_CV2") (pintype "bidirectional"))
    )
    (net (code "41") (name "INDSTROBE") (class "Default")
      (node (ref "E18") (pin "12") (pinfunction "I1_12") (pintype "input"))
      (node (ref "E18") (pin "2") (pinfunction "I0_2") (pintype "input"))
      (node (ref "E18") (pin "5") (pinfunction "I0_5") (pintype "input"))
      (node (ref "E18") (pin "9") (pinfunction "I1_9") (pintype "input"))
      (node (ref "E22") (pin "12") (pinfunction "I1_12") (pintype "input"))
      (node (ref "E22") (pin "2") (pinfunction "I0_2") (pintype "input"))
      (node (ref "E22") (pin "5") (pinfunction "I0_5") (pintype "input"))
      (node (ref "E22") (pin "9") (pinfunction "I1_9") (pintype "input"))
      (node (ref "E26") (pin "12") (pinfunction "I1_12") (pintype "input"))
      (node (ref "E26") (pin "2") (pinfunction "I0_2") (pintype "input"))
      (node (ref "E26") (pin "5") (pinfunction "I0_5") (pintype "input"))
      (node (ref "E26") (pin "9") (pinfunction "I1_9") (pintype "input"))
      (node (ref "E9") (pin "4") (pinfunction "O_4") (pintype "output"))
    )
    (net (code "42") (name "INIT") (class "Default")
      (node (ref "E13") (pin "11") (pinfunction "I0_11") (pintype "input"))
      (node (ref "E13") (pin "12") (pinfunction "I1_12") (pintype "input"))
      (node (ref "Q18") (pin "1") (pinfunction "E_1") (pintype "passive"))
      (node (ref "U$2") (pin "CR1") (pinfunction "1_CR1") (pintype "bidirectional"))
    )
    (net (code "43") (name "IR0") (class "Default")
      (node (ref "D76") (pin "A") (pinfunction "A_A") (pintype "passive"))
      (node (ref "E15") (pin "2") (pinfunction "I1_2") (pintype "input"))
      (node (ref "U$2") (pin "DD2") (pinfunction "1_DD2") (pintype "bidirectional"))
    )
    (net (code "44") (name "IR1") (class "Default")
      (node (ref "D77") (pin "A") (pinfunction "A_A") (pintype "passive"))
      (node (ref "E15") (pin "4") (pinfunction "I2_4") (pintype "input"))
      (node (ref "U$2") (pin "DE2") (pinfunction "1_DE2") (pintype "bidirectional"))
    )
    (net (code "45") (name "IR2") (class "Default")
      (node (ref "D78") (pin "A") (pinfunction "A_A") (pintype "passive"))
      (node (ref "E15") (pin "5") (pinfunction "I3_5") (pintype "input"))
      (node (ref "U$2") (pin "DH2") (pinfunction "1_DH2") (pintype "bidirectional"))
    )
    (net (code "46") (name "I{slash}O_PAUSE") (class "Default")
      (node (ref "D82") (pin "A") (pinfunction "A_A") (pintype "passive"))
      (node (ref "U$2") (pin "CD1") (pinfunction "1_CD1") (pintype "bidirectional"))
    )
    (net (code "47") (name "KEY_CONTROL") (class "Default")
      (node (ref "E1") (pin "3") (pinfunction "O_3") (pintype "open_collector"))
      (node (ref "U$2") (pin "DU2") (pinfunction "1_DU2") (pintype "bidirectional"))
    )
    (net (code "48") (name "LA_ENABLE") (class "Default")
      (node (ref "E7") (pin "10") (pinfunction "I1_10") (pintype "input"))
      (node (ref "E7") (pin "11") (pinfunction "O_11") (pintype "open_collector"))
      (node (ref "E9") (pin "9") (pinfunction "I_9") (pintype "input"))
      (node (ref "U$2") (pin "BM2") (pinfunction "1_BM2") (pintype "bidirectional"))
    )
    (net (code "49") (name "LOAD") (class "Default")
      (node (ref "D88") (pin "C") (pinfunction "C_C") (pintype "passive"))
      (node (ref "E12") (pin "4") (pinfunction "I0_4") (pintype "input"))
      (node (ref "E14") (pin "10") (pinfunction "I1_10") (pintype "input"))
      (node (ref "E6") (pin "2") (pinfunction "I1_2") (pintype "input"))
      (node (ref "E8") (pin "9") (pinfunction "I0_9") (pintype "input"))
      (node (ref "R91") (pin "2") (pinfunction "2_2") (pintype "passive"))
    )
    (net (code "50") (name "MA00") (class "Default")
      (node (ref "E24") (pin "2") (pinfunction "I0_2") (pintype "input"))
      (node (ref "U$2") (pin "AD1") (pinfunction "1_AD1") (pintype "bidirectional"))
    )
    (net (code "51") (name "MA01") (class "Default")
      (node (ref "E24") (pin "5") (pinfunction "I0_5") (pintype "input"))
      (node (ref "U$2") (pin "AE1") (pinfunction "1_AE1") (pintype "bidirectional"))
    )
    (net (code "52") (name "MA02") (class "Default")
      (node (ref "E24") (pin "12") (pinfunction "I1_12") (pintype "input"))
      (node (ref "U$2") (pin "AH1") (pinfunction "1_AH1") (pintype "bidirectional"))
    )
    (net (code "53") (name "MA03") (class "Default")
      (node (ref "E24") (pin "9") (pinfunction "I1_9") (pintype "input"))
      (node (ref "U$2") (pin "AJ1") (pinfunction "1_AJ1") (pintype "bidirectional"))
    )
    (net (code "54") (name "MA04") (class "Default")
      (node (ref "E20") (pin "2") (pinfunction "I0_2") (pintype "input"))
      (node (ref "U$2") (pin "BD1") (pinfunction "1_BD1") (pintype "bidirectional"))
    )
    (net (code "55") (name "MA05") (class "Default")
      (node (ref "E20") (pin "5") (pinfunction "I0_5") (pintype "input"))
      (node (ref "U$2") (pin "BE1") (pinfunction "1_BE1") (pintype "bidirectional"))
    )
    (net (code "56") (name "MA06") (class "Default")
      (node (ref "E20") (pin "8") (pinfunction "I0_8") (pintype "input"))
      (node (ref "U$2") (pin "BH1") (pinfunction "1_BH1") (pintype "bidirectional"))
    )
    (net (code "57") (name "MA07") (class "Default")
      (node (ref "E20") (pin "11") (pinfunction "I0_11") (pintype "input"))
      (node (ref "U$2") (pin "BJ1") (pinfunction "1_BJ1") (pintype "bidirectional"))
    )
    (net (code "58") (name "MA08") (class "Default")
      (node (ref "E16") (pin "11") (pinfunction "I0_11") (pintype "input"))
      (node (ref "U$2") (pin "DD1") (pinfunction "1_DD1") (pintype "bidirectional"))
    )
    (net (code "59") (name "MA09") (class "Default")
      (node (ref "E16") (pin "8") (pinfunction "I0_8") (pintype "input"))
      (node (ref "U$2") (pin "DE1") (pinfunction "1_DE1") (pintype "bidirectional"))
    )
    (net (code "60") (name "MA10") (class "Default")
      (node (ref "E16") (pin "3") (pinfunction "I1_3") (pintype "input"))
      (node (ref "U$2") (pin "DH1") (pinfunction "1_DH1") (pintype "bidirectional"))
    )
    (net (code "61") (name "MA11") (class "Default")
      (node (ref "E16") (pin "5") (pinfunction "I0_5") (pintype "input"))
      (node (ref "U$2") (pin "DJ1") (pinfunction "1_DJ1") (pintype "bidirectional"))
    )
    (net (code "62") (name "MD00") (class "Default")
      (node (ref "D49") (pin "A") (pinfunction "A_A") (pintype "passive"))
      (node (ref "U$2") (pin "AK1") (pinfunction "1_AK1") (pintype "bidirectional"))
    )
    (net (code "63") (name "MD01") (class "Default")
      (node (ref "D50") (pin "A") (pinfunction "A_A") (pintype "passive"))
      (node (ref "U$2") (pin "AL1") (pinfunction "1_AL1") (pintype "bidirectional"))
    )
    (net (code "64") (name "MD02") (class "Default")
      (node (ref "D51") (pin "A") (pinfunction "A_A") (pintype "passive"))
      (node (ref "U$2") (pin "AM1") (pinfunction "1_AM1") (pintype "bidirectional"))
    )
    (net (code "65") (name "MD03") (class "Default")
      (node (ref "D52") (pin "A") (pinfunction "A_A") (pintype "passive"))
      (node (ref "E15") (pin "10") (pinfunction "I1_10") (pintype "input"))
      (node (ref "U$2") (pin "AP1") (pinfunction "1_AP1") (pintype "bidirectional"))
    )
    (net (code "66") (name "MD04") (class "Default")
      (node (ref "D53") (pin "A") (pinfunction "A_A") (pintype "passive"))
      (node (ref "U$2") (pin "BK1") (pinfunction "1_BK1") (pintype "bidirectional"))
    )
    (net (code "67") (name "MD05") (class "Default")
      (node (ref "D54") (pin "A") (pinfunction "A_A") (pintype "passive"))
      (node (ref "U$2") (pin "BL1") (pinfunction "1_BL1") (pintype "bidirectional"))
    )
    (net (code "68") (name "MD06") (class "Default")
      (node (ref "D55") (pin "A") (pinfunction "A_A") (pintype "passive"))
      (node (ref "U$2") (pin "BM1") (pinfunction "1_BM1") (pintype "bidirectional"))
    )
    (net (code "69") (name "MD07") (class "Default")
      (node (ref "D56") (pin "A") (pinfunction "A_A") (pintype "passive"))
      (node (ref "U$2") (pin "BP1") (pinfunction "1_BP1") (pintype "bidirectional"))
    )
    (net (code "70") (name "MD08") (class "Default")
      (node (ref "D57") (pin "A") (pinfunction "A_A") (pintype "passive"))
      (node (ref "U$2") (pin "DK1") (pinfunction "1_DK1") (pintype "bidirectional"))
    )
    (net (code "71") (name "MD09") (class "Default")
      (node (ref "D58") (pin "A") (pinfunction "A_A") (pintype "passive"))
      (node (ref "E15") (pin "9") (pinfunction "I0_9") (pintype "input"))
      (node (ref "U$2") (pin "DL1") (pinfunction "1_DL1") (pintype "bidirectional"))
    )
    (net (code "72") (name "MD10") (class "Default")
      (node (ref "D59") (pin "A") (pinfunction "A_A") (pintype "passive"))
      (node (ref "U$2") (pin "DM1") (pinfunction "1_DM1") (pintype "bidirectional"))
    )
    (net (code "73") (name "MD11") (class "Default")
      (node (ref "D60") (pin "A") (pinfunction "A_A") (pintype "passive"))
      (node (ref "E13") (pin "3") (pinfunction "I1_3") (pintype "input"))
      (node (ref "U$2") (pin "DP1") (pinfunction "1_DP1") (pintype "bidirectional"))
    )
    (net (code "74") (name "MD_DIR_IN") (class "Default")
      (node (ref "D79") (pin "A") (pinfunction "A_A") (pintype "passive"))
      (node (ref "E4") (pin "8") (pinfunction "O_8") (pintype "open_collector"))
      (node (ref "U$2") (pin "AK2") (pinfunction "1_AK2") (pintype "bidirectional"))
    )
    (net (code "75") (name "MD_EN") (class "Default")
      (node (ref "R13") (pin "1") (pinfunction "1_1") (pintype "passive"))
      (node (ref "R14") (pin "1") (pinfunction "1_1") (pintype "passive"))
      (node (ref "R142") (pin "1") (pinfunction "1_1") (pintype "passive"))
      (node (ref "R15") (pin "1") (pinfunction "1_1") (pintype "passive"))
      (node (ref "R16") (pin "1") (pinfunction "1_1") (pintype "passive"))
      (node (ref "R17") (pin "1") (pinfunction "1_1") (pintype "passive"))
      (node (ref "R18") (pin "1") (pinfunction "1_1") (pintype "passive"))
      (node (ref "R19") (pin "1") (pinfunction "1_1") (pintype "passive"))
      (node (ref "R20") (pin "1") (pinfunction "1_1") (pintype "passive"))
      (node (ref "R21") (pin "1") (pinfunction "1_1") (pintype "passive"))
      (node (ref "R22") (pin "1") (pinfunction "1_1") (pintype "passive"))
      (node (ref "R23") (pin "1") (pinfunction "1_1") (pintype "passive"))
      (node (ref "R24") (pin "1") (pinfunction "1_1") (pintype "passive"))
      (node (ref "S1") (pin "A3") (pinfunction "A3_A3") (pintype "passive"))
    )
    (net (code "76") (name "MEM_START") (class "Default")
      (node (ref "E1") (pin "11") (pinfunction "O_11") (pintype "open_collector"))
      (node (ref "U$2") (pin "AJ2") (pinfunction "1_AJ2") (pintype "bidirectional"))
    )
    (net (code "77") (name "MQ_EN") (class "Default")
      (node (ref "D108") (pin "C") (pinfunction "C_C") (pintype "passive"))
      (node (ref "D110") (pin "C") (pinfunction "C_C") (pintype "passive"))
      (node (ref "R171") (pin "1") (pinfunction "1_1") (pintype "passive"))
      (node (ref "S1") (pin "A2") (pinfunction "A2_A2") (pintype "passive"))
    )
    (net (code "78") (name "MS_DISABLE") (class "Default")
      (node (ref "E4") (pin "6") (pinfunction "O_6") (pintype "open_collector"))
      (node (ref "U$2") (pin "CV1") (pinfunction "1_CV1") (pintype "bidirectional"))
    )
    (net (code "79") (name "Net-(C13-Pad+)") (class "Default")
      (node (ref "C13") (pin "+") (pinfunction "+_+") (pintype "passive"))
      (node (ref "R153") (pin "2") (pinfunction "2_2") (pintype "passive"))
      (node (ref "R154") (pin "1") (pinfunction "1_1") (pintype "passive"))
    )
    (net (code "80") (name "Net-(D1-PadA)") (class "Default")
      (node (ref "D1") (pin "A") (pinfunction "A_A") (pintype "passive"))
      (node (ref "R26") (pin "2") (pinfunction "2_2") (pintype "passive"))
    )
    (net (code "81") (name "Net-(D2-PadA)") (class "Default")
      (node (ref "D2") (pin "A") (pinfunction "A_A") (pintype "passive"))
      (node (ref "R29") (pin "2") (pinfunction "2_2") (pintype "passive"))
    )
    (net (code "82") (name "Net-(D3-PadA)") (class "Default")
      (node (ref "D3") (pin "A") (pinfunction "A_A") (pintype "passive"))
      (node (ref "R32") (pin "2") (pinfunction "2_2") (pintype "passive"))
    )
    (net (code "83") (name "Net-(D4-PadA)") (class "Default")
      (node (ref "D4") (pin "A") (pinfunction "A_A") (pintype "passive"))
      (node (ref "R35") (pin "2") (pinfunction "2_2") (pintype "passive"))
    )
    (net (code "84") (name "Net-(D5-PadA)") (class "Default")
      (node (ref "D5") (pin "A") (pinfunction "A_A") (pintype "passive"))
      (node (ref "R38") (pin "2") (pinfunction "2_2") (pintype "passive"))
    )
    (net (code "85") (name "Net-(D6-PadA)") (class "Default")
      (node (ref "D6") (pin "A") (pinfunction "A_A") (pintype "passive"))
      (node (ref "R41") (pin "2") (pinfunction "2_2") (pintype "passive"))
    )
    (net (code "86") (name "Net-(D7-PadA)") (class "Default")
      (node (ref "D7") (pin "A") (pinfunction "A_A") (pintype "passive"))
      (node (ref "R44") (pin "2") (pinfunction "2_2") (pintype "passive"))
    )
    (net (code "87") (name "Net-(D8-PadA)") (class "Default")
      (node (ref "D8") (pin "A") (pinfunction "A_A") (pintype "passive"))
      (node (ref "R47") (pin "2") (pinfunction "2_2") (pintype "passive"))
    )
    (net (code "88") (name "Net-(D9-PadA)") (class "Default")
      (node (ref "D9") (pin "A") (pinfunction "A_A") (pintype "passive"))
      (node (ref "R50") (pin "2") (pinfunction "2_2") (pintype "passive"))
    )
    (net (code "89") (name "Net-(D10-PadA)") (class "Default")
      (node (ref "D10") (pin "A") (pinfunction "A_A") (pintype "passive"))
      (node (ref "R53") (pin "2") (pinfunction "2_2") (pintype "passive"))
    )
    (net (code "90") (name "Net-(D11-PadA)") (class "Default")
      (node (ref "D11") (pin "A") (pinfunction "A_A") (pintype "passive"))
      (node (ref "R56") (pin "2") (pinfunction "2_2") (pintype "passive"))
    )
    (net (code "91") (name "Net-(D12-PadA)") (class "Default")
      (node (ref "D12") (pin "A") (pinfunction "A_A") (pintype "passive"))
      (node (ref "R59") (pin "2") (pinfunction "2_2") (pintype "passive"))
    )
    (net (code "92") (name "Net-(D13-PadC)") (class "Default")
      (node (ref "D13") (pin "C") (pinfunction "C_C") (pintype "passive"))
      (node (ref "D60") (pin "C") (pinfunction "C_C") (pintype "passive"))
      (node (ref "R24") (pin "2") (pinfunction "2_2") (pintype "passive"))
    )
    (net (code "93") (name "Net-(D14-PadC)") (class "Default")
      (node (ref "D14") (pin "C") (pinfunction "C_C") (pintype "passive"))
      (node (ref "D59") (pin "C") (pinfunction "C_C") (pintype "passive"))
      (node (ref "R23") (pin "2") (pinfunction "2_2") (pintype "passive"))
    )
    (net (code "94") (name "Net-(D15-PadC)") (class "Default")
      (node (ref "D15") (pin "C") (pinfunction "C_C") (pintype "passive"))
      (node (ref "D58") (pin "C") (pinfunction "C_C") (pintype "passive"))
      (node (ref "R22") (pin "2") (pinfunction "2_2") (pintype "passive"))
    )
    (net (code "95") (name "Net-(D16-PadC)") (class "Default")
      (node (ref "D16") (pin "C") (pinfunction "C_C") (pintype "passive"))
      (node (ref "D57") (pin "C") (pinfunction "C_C") (pintype "passive"))
      (node (ref "R21") (pin "2") (pinfunction "2_2") (pintype "passive"))
    )
    (net (code "96") (name "Net-(D17-PadC)") (class "Default")
      (node (ref "D17") (pin "C") (pinfunction "C_C") (pintype "passive"))
      (node (ref "D56") (pin "C") (pinfunction "C_C") (pintype "passive"))
      (node (ref "R20") (pin "2") (pinfunction "2_2") (pintype "passive"))
    )
    (net (code "97") (name "Net-(D18-PadC)") (class "Default")
      (node (ref "D18") (pin "C") (pinfunction "C_C") (pintype "passive"))
      (node (ref "D55") (pin "C") (pinfunction "C_C") (pintype "passive"))
      (node (ref "R19") (pin "2") (pinfunction "2_2") (pintype "passive"))
    )
    (net (code "98") (name "Net-(D19-PadC)") (class "Default")
      (node (ref "D19") (pin "C") (pinfunction "C_C") (pintype "passive"))
      (node (ref "D54") (pin "C") (pinfunction "C_C") (pintype "passive"))
      (node (ref "R18") (pin "2") (pinfunction "2_2") (pintype "passive"))
    )
    (net (code "99") (name "Net-(D20-PadC)") (class "Default")
      (node (ref "D20") (pin "C") (pinfunction "C_C") (pintype "passive"))
      (node (ref "D53") (pin "C") (pinfunction "C_C") (pintype "passive"))
      (node (ref "R17") (pin "2") (pinfunction "2_2") (pintype "passive"))
    )
    (net (code "100") (name "Net-(D21-PadC)") (class "Default")
      (node (ref "D21") (pin "C") (pinfunction "C_C") (pintype "passive"))
      (node (ref "D52") (pin "C") (pinfunction "C_C") (pintype "passive"))
      (node (ref "R16") (pin "2") (pinfunction "2_2") (pintype "passive"))
    )
    (net (code "101") (name "Net-(D22-PadC)") (class "Default")
      (node (ref "D22") (pin "C") (pinfunction "C_C") (pintype "passive"))
      (node (ref "D51") (pin "C") (pinfunction "C_C") (pintype "passive"))
      (node (ref "R15") (pin "2") (pinfunction "2_2") (pintype "passive"))
    )
    (net (code "102") (name "Net-(D23-PadC)") (class "Default")
      (node (ref "D23") (pin "C") (pinfunction "C_C") (pintype "passive"))
      (node (ref "D50") (pin "C") (pinfunction "C_C") (pintype "passive"))
      (node (ref "R14") (pin "2") (pinfunction "2_2") (pintype "passive"))
    )
    (net (code "103") (name "Net-(D24-PadC)") (class "Default")
      (node (ref "D24") (pin "C") (pinfunction "C_C") (pintype "passive"))
      (node (ref "D49") (pin "C") (pinfunction "C_C") (pintype "passive"))
      (node (ref "R13") (pin "2") (pinfunction "2_2") (pintype "passive"))
    )
    (net (code "104") (name "Net-(D25-PadC)") (class "Default")
      (node (ref "D25") (pin "C") (pinfunction "C_C") (pintype "passive"))
      (node (ref "D72") (pin "C") (pinfunction "C_C") (pintype "passive"))
      (node (ref "R84") (pin "1") (pinfunction "1_1") (pintype "passive"))
    )
    (net (code "105") (name "Net-(D26-PadC)") (class "Default")
      (node (ref "D26") (pin "C") (pinfunction "C_C") (pintype "passive"))
      (node (ref "D71") (pin "C") (pinfunction "C_C") (pintype "passive"))
      (node (ref "R82") (pin "1") (pinfunction "1_1") (pintype "passive"))
    )
    (net (code "106") (name "Net-(D27-PadC)") (class "Default")
      (node (ref "D27") (pin "C") (pinfunction "C_C") (pintype "passive"))
      (node (ref "D70") (pin "C") (pinfunction "C_C") (pintype "passive"))
      (node (ref "R80") (pin "1") (pinfunction "1_1") (pintype "passive"))
    )
    (net (code "107") (name "Net-(D28-PadC)") (class "Default")
      (node (ref "D28") (pin "C") (pinfunction "C_C") (pintype "passive"))
      (node (ref "D69") (pin "C") (pinfunction "C_C") (pintype "passive"))
      (node (ref "R78") (pin "1") (pinfunction "1_1") (pintype "passive"))
    )
    (net (code "108") (name "Net-(D29-PadC)") (class "Default")
      (node (ref "D29") (pin "C") (pinfunction "C_C") (pintype "passive"))
      (node (ref "D68") (pin "C") (pinfunction "C_C") (pintype "passive"))
      (node (ref "R76") (pin "1") (pinfunction "1_1") (pintype "passive"))
    )
    (net (code "109") (name "Net-(D30-PadC)") (class "Default")
      (node (ref "D30") (pin "C") (pinfunction "C_C") (pintype "passive"))
      (node (ref "D67") (pin "C") (pinfunction "C_C") (pintype "passive"))
      (node (ref "R74") (pin "1") (pinfunction "1_1") (pintype "passive"))
    )
    (net (code "110") (name "Net-(D31-PadC)") (class "Default")
      (node (ref "D31") (pin "C") (pinfunction "C_C") (pintype "passive"))
      (node (ref "D66") (pin "C") (pinfunction "C_C") (pintype "passive"))
      (node (ref "R72") (pin "1") (pinfunction "1_1") (pintype "passive"))
    )
    (net (code "111") (name "Net-(D32-PadC)") (class "Default")
      (node (ref "D32") (pin "C") (pinfunction "C_C") (pintype "passive"))
      (node (ref "D65") (pin "C") (pinfunction "C_C") (pintype "passive"))
      (node (ref "R70") (pin "1") (pinfunction "1_1") (pintype "passive"))
    )
    (net (code "112") (name "Net-(D33-PadC)") (class "Default")
      (node (ref "D33") (pin "C") (pinfunction "C_C") (pintype "passive"))
      (node (ref "D64") (pin "C") (pinfunction "C_C") (pintype "passive"))
      (node (ref "R68") (pin "1") (pinfunction "1_1") (pintype "passive"))
    )
    (net (code "113") (name "Net-(D34-PadC)") (class "Default")
      (node (ref "D34") (pin "C") (pinfunction "C_C") (pintype "passive"))
      (node (ref "D63") (pin "C") (pinfunction "C_C") (pintype "passive"))
      (node (ref "R66") (pin "1") (pinfunction "1_1") (pintype "passive"))
    )
    (net (code "114") (name "Net-(D35-PadC)") (class "Default")
      (node (ref "D35") (pin "C") (pinfunction "C_C") (pintype "passive"))
      (node (ref "D62") (pin "C") (pinfunction "C_C") (pintype "passive"))
      (node (ref "R64") (pin "1") (pinfunction "1_1") (pintype "passive"))
    )
    (net (code "115") (name "Net-(D36-PadC)") (class "Default")
      (node (ref "D36") (pin "C") (pinfunction "C_C") (pintype "passive"))
      (node (ref "D61") (pin "C") (pinfunction "C_C") (pintype "passive"))
      (node (ref "R62") (pin "1") (pinfunction "1_1") (pintype "passive"))
    )
    (net (code "116") (name "Net-(D37-PadC)") (class "Default")
      (node (ref "D37") (pin "C") (pinfunction "C_C") (pintype "passive"))
      (node (ref "D84") (pin "C") (pinfunction "C_C") (pintype "passive"))
      (node (ref "R83") (pin "1") (pinfunction "1_1") (pintype "passive"))
    )
    (net (code "117") (name "Net-(D38-PadC)") (class "Default")
      (node (ref "D38") (pin "C") (pinfunction "C_C") (pintype "passive"))
      (node (ref "D83") (pin "C") (pinfunction "C_C") (pintype "passive"))
      (node (ref "R81") (pin "1") (pinfunction "1_1") (pintype "passive"))
    )
    (net (code "118") (name "Net-(D39-PadC)") (class "Default")
      (node (ref "D39") (pin "C") (pinfunction "C_C") (pintype "passive"))
      (node (ref "D82") (pin "C") (pinfunction "C_C") (pintype "passive"))
      (node (ref "R79") (pin "1") (pinfunction "1_1") (pintype "passive"))
    )
    (net (code "119") (name "Net-(D40-PadC)") (class "Default")
      (node (ref "D40") (pin "C") (pinfunction "C_C") (pintype "passive"))
      (node (ref "D81") (pin "C") (pinfunction "C_C") (pintype "passive"))
      (node (ref "R77") (pin "1") (pinfunction "1_1") (pintype "passive"))
    )
    (net (code "120") (name "Net-(D41-PadC)") (class "Default")
      (node (ref "D41") (pin "C") (pinfunction "C_C") (pintype "passive"))
      (node (ref "D80") (pin "C") (pinfunction "C_C") (pintype "passive"))
      (node (ref "R75") (pin "1") (pinfunction "1_1") (pintype "passive"))
    )
    (net (code "121") (name "Net-(D42-PadC)") (class "Default")
      (node (ref "D42") (pin "C") (pinfunction "C_C") (pintype "passive"))
      (node (ref "D79") (pin "C") (pinfunction "C_C") (pintype "passive"))
      (node (ref "R73") (pin "1") (pinfunction "1_1") (pintype "passive"))
    )
    (net (code "122") (name "Net-(D43-PadC)") (class "Default")
      (node (ref "D43") (pin "C") (pinfunction "C_C") (pintype "passive"))
      (node (ref "D78") (pin "C") (pinfunction "C_C") (pintype "passive"))
      (node (ref "R71") (pin "1") (pinfunction "1_1") (pintype "passive"))
    )
    (net (code "123") (name "Net-(D44-PadC)") (class "Default")
      (node (ref "D44") (pin "C") (pinfunction "C_C") (pintype "passive"))
      (node (ref "D77") (pin "C") (pinfunction "C_C") (pintype "passive"))
      (node (ref "R69") (pin "1") (pinfunction "1_1") (pintype "passive"))
    )
    (net (code "124") (name "Net-(D45-PadC)") (class "Default")
      (node (ref "D45") (pin "C") (pinfunction "C_C") (pintype "passive"))
      (node (ref "D76") (pin "C") (pinfunction "C_C") (pintype "passive"))
      (node (ref "R67") (pin "1") (pinfunction "1_1") (pintype "passive"))
    )
    (net (code "125") (name "Net-(D46-PadC)") (class "Default")
      (node (ref "D46") (pin "C") (pinfunction "C_C") (pintype "passive"))
      (node (ref "D75") (pin "C") (pinfunction "C_C") (pintype "passive"))
      (node (ref "R65") (pin "1") (pinfunction "1_1") (pintype "passive"))
    )
    (net (code "126") (name "Net-(D47-PadC)") (class "Default")
      (node (ref "D47") (pin "C") (pinfunction "C_C") (pintype "passive"))
      (node (ref "D74") (pin "C") (pinfunction "C_C") (pintype "passive"))
      (node (ref "R63") (pin "1") (pinfunction "1_1") (pintype "passive"))
    )
    (net (code "127") (name "Net-(D48-PadC)") (class "Default")
      (node (ref "D48") (pin "C") (pinfunction "C_C") (pintype "passive"))
      (node (ref "D73") (pin "C") (pinfunction "C_C") (pintype "passive"))
      (node (ref "R61") (pin "1") (pinfunction "1_1") (pintype "passive"))
    )
    (net (code "128") (name "Net-(D110-PadA)") (class "Default")
      (node (ref "D110") (pin "A") (pinfunction "A_A") (pintype "passive"))
      (node (ref "D111") (pin "A") (pinfunction "A_A") (pintype "passive"))
      (node (ref "R150") (pin "1") (pinfunction "1_1") (pintype "passive"))
    )
    (net (code "129") (name "Net-(D112-PadA)") (class "Default")
      (node (ref "D112") (pin "A") (pinfunction "A_A") (pintype "passive"))
      (node (ref "D113") (pin "A") (pinfunction "A_A") (pintype "passive"))
      (node (ref "R149") (pin "1") (pinfunction "1_1") (pintype "passive"))
    )
    (net (code "130") (name "Net-(D116-PadC)") (class "Default")
      (node (ref "D116") (pin "C") (pinfunction "C_C") (pintype "passive"))
      (node (ref "D117") (pin "A") (pinfunction "A_A") (pintype "passive"))
    )
    (net (code "131") (name "Net-(D118-PadA)") (class "Default")
      (node (ref "D118") (pin "A") (pinfunction "A_A") (pintype "passive"))
      (node (ref "D119") (pin "C") (pinfunction "C_C") (pintype "passive"))
    )
    (net (code "132") (name "Net-(D120-PadC)") (class "Default")
      (node (ref "D120") (pin "C") (pinfunction "C_C") (pintype "passive"))
      (node (ref "D130") (pin "A") (pinfunction "A_A") (pintype "passive"))
    )
    (net (code "133") (name "Net-(D122-PadA)") (class "Default")
      (node (ref "D122") (pin "A") (pinfunction "A_A") (pintype "passive"))
      (node (ref "R169") (pin "2") (pinfunction "2_2") (pintype "passive"))
    )
    (net (code "134") (name "Net-(D123-PadC)") (class "Default")
      (node (ref "D123") (pin "C") (pinfunction "C_C") (pintype "passive"))
      (node (ref "D124") (pin "A") (pinfunction "A_A") (pintype "passive"))
    )
    (net (code "135") (name "Net-(D124-PadC)") (class "Default")
      (node (ref "D124") (pin "C") (pinfunction "C_C") (pintype "passive"))
      (node (ref "D125") (pin "A") (pinfunction "A_A") (pintype "passive"))
    )
    (net (code "136") (name "Net-(E1A-I0)") (class "Default")
      (node (ref "E1") (pin "1") (pinfunction "I0_1") (pintype "input"))
      (node (ref "E8") (pin "12") (pinfunction "O_12") (pintype "output"))
    )
    (net (code "137") (name "Net-(E1D-I0)") (class "Default")
      (node (ref "E1") (pin "12") (pinfunction "I0_12") (pintype "input"))
      (node (ref "E2") (pin "13") (pinfunction "O_13") (pintype "output"))
      (node (ref "E2") (pin "9") (pinfunction "I1_9") (pintype "input"))
      (node (ref "E3") (pin "1") (pinfunction "I0_1") (pintype "input"))
      (node (ref "E3") (pin "4") (pinfunction "I0_4") (pintype "input"))
    )
    (net (code "138") (name "Net-(E2A-O)") (class "Default")
      (node (ref "E2") (pin "1") (pinfunction "O_1") (pintype "output"))
      (node (ref "E3") (pin "13") (pinfunction "I1_13") (pintype "input"))
    )
    (net (code "139") (name "Net-(E2B-O)") (class "Default")
      (node (ref "E2") (pin "4") (pinfunction "O_4") (pintype "output"))
      (node (ref "E6") (pin "12") (pinfunction "I0_12") (pintype "input"))
    )
    (net (code "140") (name "Net-(E2C-I0)") (class "Default")
      (node (ref "C14") (pin "1") (pinfunction "1_1") (pintype "passive"))
      (node (ref "E2") (pin "8") (pinfunction "I0_8") (pintype "input"))
      (node (ref "R159") (pin "2") (pinfunction "2_2") (pintype "passive"))
      (node (ref "R160") (pin "2") (pinfunction "2_2") (pintype "passive"))
    )
    (net (code "141") (name "Net-(E2C-O)") (class "Default")
      (node (ref "C15") (pin "2") (pinfunction "2_2") (pintype "passive"))
      (node (ref "E2") (pin "10") (pinfunction "O_10") (pintype "output"))
    )
    (net (code "142") (name "Net-(E2D-I0)") (class "Default")
      (node (ref "C15") (pin "1") (pinfunction "1_1") (pintype "passive"))
      (node (ref "D121") (pin "A") (pinfunction "A_A") (pintype "passive"))
      (node (ref "E2") (pin "11") (pinfunction "I0_11") (pintype "input"))
      (node (ref "R161") (pin "1") (pinfunction "1_1") (pintype "passive"))
    )
    (net (code "143") (name "Net-(E3C-I0)") (class "Default")
      (node (ref "E3") (pin "12") (pinfunction "I0_12") (pintype "input"))
      (node (ref "E3") (pin "9") (pinfunction "I0_9") (pintype "input"))
      (node (ref "E5") (pin "8") (pinfunction "O_8") (pintype "output"))
    )
    (net (code "144") (name "Net-(E3C-I1)") (class "Default")
      (node (ref "E3") (pin "10") (pinfunction "I1_10") (pintype "input"))
      (node (ref "E3") (pin "11") (pinfunction "O_11") (pintype "output"))
    )
    (net (code "145") (name "Net-(E3C-O)") (class "Default")
      (node (ref "E3") (pin "8") (pinfunction "O_8") (pintype "output"))
      (node (ref "E9") (pin "3") (pinfunction "I_3") (pintype "input"))
    )
    (net (code "146") (name "Net-(E4B-I0)") (class "Default")
      (node (ref "E4") (pin "4") (pinfunction "I0_4") (pintype "input"))
      (node (ref "E6") (pin "8") (pinfunction "O_8") (pintype "output"))
    )
    (net (code "147") (name "Net-(E4D-I0)") (class "Default")
      (node (ref "E4") (pin "12") (pinfunction "I0_12") (pintype "input"))
      (node (ref "E4") (pin "13") (pinfunction "I1_13") (pintype "input"))
      (node (ref "E6") (pin "6") (pinfunction "O_6") (pintype "output"))
    )
    (net (code "148") (name "Net-(E5C-I0)") (class "Default")
      (node (ref "D109") (pin "C") (pinfunction "C_C") (pintype "passive"))
      (node (ref "E5") (pin "9") (pinfunction "I0_9") (pintype "input"))
      (node (ref "R147") (pin "1") (pinfunction "1_1") (pintype "passive"))
      (node (ref "R148") (pin "2") (pinfunction "2_2") (pintype "passive"))
    )
    (net (code "149") (name "Net-(E5C-I1)") (class "Default")
      (node (ref "D128") (pin "C") (pinfunction "C_C") (pintype "passive"))
      (node (ref "E5") (pin "10") (pinfunction "I1_10") (pintype "input"))
      (node (ref "R146") (pin "1") (pinfunction "1_1") (pintype "passive"))
      (node (ref "R171") (pin "2") (pinfunction "2_2") (pintype "passive"))
    )
    (net (code "150") (name "Net-(E5C-I2)") (class "Default")
      (node (ref "D127") (pin "C") (pinfunction "C_C") (pintype "passive"))
      (node (ref "E5") (pin "11") (pinfunction "I2_11") (pintype "input"))
      (node (ref "R144") (pin "1") (pinfunction "1_1") (pintype "passive"))
      (node (ref "R173") (pin "2") (pinfunction "2_2") (pintype "passive"))
    )
    (net (code "151") (name "Net-(E7A-I0)") (class "Default")
      (node (ref "E7") (pin "1") (pinfunction "I0_1") (pintype "input"))
      (node (ref "E7") (pin "2") (pinfunction "I1_2") (pintype "input"))
      (node (ref "E9") (pin "10") (pinfunction "O_10") (pintype "output"))
    )
    (net (code "152") (name "Net-(E7B-I0)") (class "Default")
      (node (ref "E7") (pin "4") (pinfunction "I0_4") (pintype "input"))
      (node (ref "E7") (pin "5") (pinfunction "I1_5") (pintype "input"))
      (node (ref "E9") (pin "8") (pinfunction "O_8") (pintype "output"))
    )
    (net (code "153") (name "Net-(E7C-I0)") (class "Default")
      (node (ref "E7") (pin "9") (pinfunction "I0_9") (pintype "input"))
      (node (ref "E9") (pin "6") (pinfunction "O_6") (pintype "output"))
    )
    (net (code "154") (name "Net-(E8B-I1)") (class "Default")
      (node (ref "E8") (pin "4") (pinfunction "I1_4") (pintype "input"))
      (node (ref "E8") (pin "8") (pinfunction "O_8") (pintype "output"))
    )
    (net (code "155") (name "Net-(E9A-O)") (class "Default")
      (node (ref "E9") (pin "2") (pinfunction "O_2") (pintype "output"))
      (node (ref "R166") (pin "1") (pinfunction "1_1") (pintype "passive"))
    )
    (net (code "156") (name "Net-(E9C-I)") (class "Default")
      (node (ref "D114") (pin "C") (pinfunction "C_C") (pintype "passive"))
      (node (ref "E9") (pin "5") (pinfunction "I_5") (pintype "input"))
      (node (ref "R150") (pin "2") (pinfunction "2_2") (pintype "passive"))
      (node (ref "R151") (pin "1") (pinfunction "1_1") (pintype "passive"))
    )
    (net (code "157") (name "Net-(E9E-I)") (class "Default")
      (node (ref "D115") (pin "C") (pinfunction "C_C") (pintype "passive"))
      (node (ref "E9") (pin "11") (pinfunction "I_11") (pintype "input"))
      (node (ref "R149") (pin "2") (pinfunction "2_2") (pintype "passive"))
      (node (ref "R152") (pin "1") (pinfunction "1_1") (pintype "passive"))
    )
    (net (code "158") (name "Net-(E10A-I)") (class "Default")
      (node (ref "E10") (pin "1") (pinfunction "I_1") (pintype "input"))
      (node (ref "E12") (pin "3") (pinfunction "O_3") (pintype "output"))
    )
    (net (code "159") (name "Net-(E10B-O)") (class "Default")
      (node (ref "E10") (pin "4") (pinfunction "O_4") (pintype "output"))
      (node (ref "E14") (pin "12") (pinfunction "I2_12") (pintype "input"))
    )
    (net (code "160") (name "Net-(E10C-O)") (class "Default")
      (node (ref "E10") (pin "6") (pinfunction "O_6") (pintype "output"))
      (node (ref "E3") (pin "5") (pinfunction "I1_5") (pintype "input"))
    )
    (net (code "161") (name "Net-(E10D-I)") (class "Default")
      (node (ref "E10") (pin "9") (pinfunction "I_9") (pintype "input"))
      (node (ref "E3") (pin "6") (pinfunction "O_6") (pintype "output"))
    )
    (net (code "162") (name "Net-(E10D-O)") (class "Default")
      (node (ref "E10") (pin "8") (pinfunction "O_8") (pintype "output"))
      (node (ref "R164") (pin "1") (pinfunction "1_1") (pintype "passive"))
      (node (ref "R174") (pin "1") (pinfunction "1_1") (pintype "passive"))
    )
    (net (code "163") (name "Net-(E10E-I)") (class "Default")
      (node (ref "E10") (pin "11") (pinfunction "I_11") (pintype "input"))
      (node (ref "E3") (pin "3") (pinfunction "O_3") (pintype "output"))
    )
    (net (code "164") (name "Net-(E10E-O)") (class "Default")
      (node (ref "E10") (pin "10") (pinfunction "O_10") (pintype "output"))
      (node (ref "R162") (pin "1") (pinfunction "1_1") (pintype "passive"))
      (node (ref "R172") (pin "1") (pinfunction "1_1") (pintype "passive"))
    )
    (net (code "165") (name "Net-(E10F-I)") (class "Default")
      (node (ref "E10") (pin "13") (pinfunction "I_13") (pintype "input"))
      (node (ref "E4") (pin "1") (pinfunction "I0_1") (pintype "input"))
      (node (ref "E4") (pin "10") (pinfunction "I1_10") (pintype "input"))
      (node (ref "E6") (pin "3") (pinfunction "O_3") (pintype "output"))
    )
    (net (code "166") (name "Net-(E10F-O)") (class "Default")
      (node (ref "E10") (pin "12") (pinfunction "O_12") (pintype "output"))
      (node (ref "E6") (pin "9") (pinfunction "I0_9") (pintype "input"))
    )
    (net (code "167") (name "Net-(E11B-O)") (class "Default")
      (node (ref "E11") (pin "6") (pinfunction "O_6") (pintype "output"))
      (node (ref "E12") (pin "1") (pinfunction "I0_1") (pintype "input"))
    )
    (net (code "168") (name "Net-(E11C-O)") (class "Default")
      (node (ref "E11") (pin "8") (pinfunction "O_8") (pintype "output"))
      (node (ref "E6") (pin "4") (pinfunction "I0_4") (pintype "input"))
    )
    (net (code "169") (name "Net-(E11D-O)") (class "Default")
      (node (ref "E11") (pin "11") (pinfunction "O_11") (pintype "output"))
      (node (ref "E8") (pin "3") (pinfunction "I0_3") (pintype "input"))
    )
    (net (code "170") (name "Net-(E12A-I1)") (class "Default")
      (node (ref "E12") (pin "2") (pinfunction "I1_2") (pintype "input"))
      (node (ref "E14") (pin "8") (pinfunction "O_8") (pintype "output"))
    )
    (net (code "171") (name "Net-(E12B-O)") (class "Default")
      (node (ref "E12") (pin "6") (pinfunction "O_6") (pintype "output"))
      (node (ref "E3") (pin "2") (pinfunction "I1_2") (pintype "input"))
      (node (ref "E7") (pin "13") (pinfunction "I1_13") (pintype "input"))
    )
    (net (code "172") (name "Net-(E12C-I0)") (class "Default")
      (node (ref "E12") (pin "12") (pinfunction "I0_12") (pintype "input"))
      (node (ref "E12") (pin "9") (pinfunction "I0_9") (pintype "input"))
      (node (ref "E5") (pin "12") (pinfunction "O_12") (pintype "output"))
    )
    (net (code "173") (name "Net-(E12C-I1)") (class "Default")
      (node (ref "E12") (pin "10") (pinfunction "I1_10") (pintype "input"))
      (node (ref "E12") (pin "11") (pinfunction "O_11") (pintype "output"))
    )
    (net (code "174") (name "Net-(E13A-O)") (class "Default")
      (node (ref "E13") (pin "1") (pinfunction "O_1") (pintype "output"))
      (node (ref "E15") (pin "13") (pinfunction "I3_13") (pintype "input"))
    )
    (net (code "175") (name "Net-(E13B-O)") (class "Default")
      (node (ref "E13") (pin "4") (pinfunction "O_4") (pintype "output"))
      (node (ref "E15") (pin "12") (pinfunction "I2_12") (pintype "input"))
    )
    (net (code "176") (name "Net-(E13C-O)") (class "Default")
      (node (ref "E13") (pin "10") (pinfunction "O_10") (pintype "output"))
      (node (ref "E5") (pin "1") (pinfunction "I0_1") (pintype "input"))
    )
    (net (code "177") (name "Net-(E13D-O)") (class "Default")
      (node (ref "E13") (pin "13") (pinfunction "O_13") (pintype "output"))
      (node (ref "E5") (pin "2") (pinfunction "I1_2") (pintype "input"))
    )
    (net (code "178") (name "Net-(E14A-I0)") (class "Default")
      (node (ref "E14") (pin "1") (pinfunction "I0_1") (pintype "input"))
      (node (ref "E14") (pin "2") (pinfunction "I1_2") (pintype "input"))
      (node (ref "E6") (pin "11") (pinfunction "O_11") (pintype "output"))
    )
    (net (code "179") (name "Net-(E14A-I2)") (class "Default")
      (node (ref "E14") (pin "4") (pinfunction "I2_4") (pintype "input"))
      (node (ref "E14") (pin "5") (pinfunction "I3_5") (pintype "input"))
      (node (ref "E8") (pin "6") (pinfunction "O_6") (pintype "output"))
    )
    (net (code "180") (name "Net-(E14A-O)") (class "Default")
      (node (ref "E14") (pin "6") (pinfunction "O_6") (pintype "output"))
      (node (ref "E17") (pin "1") (pinfunction "I0_1") (pintype "input"))
      (node (ref "E17") (pin "10") (pinfunction "I1_10") (pintype "input"))
      (node (ref "E17") (pin "13") (pinfunction "I1_13") (pintype "input"))
      (node (ref "E17") (pin "4") (pinfunction "I0_4") (pintype "input"))
      (node (ref "E21") (pin "1") (pinfunction "I0_1") (pintype "input"))
      (node (ref "E21") (pin "10") (pinfunction "I1_10") (pintype "input"))
      (node (ref "E21") (pin "13") (pinfunction "I1_13") (pintype "input"))
      (node (ref "E21") (pin "4") (pinfunction "I0_4") (pintype "input"))
      (node (ref "E25") (pin "1") (pinfunction "I0_1") (pintype "input"))
      (node (ref "E25") (pin "10") (pinfunction "I1_10") (pintype "input"))
      (node (ref "E25") (pin "12") (pinfunction "I0_12") (pintype "input"))
      (node (ref "E25") (pin "4") (pinfunction "I0_4") (pintype "input"))
    )
    (net (code "181") (name "Net-(E15A-O)") (class "Default")
      (node (ref "E15") (pin "11") (pinfunction "G_11") (pintype "input"))
      (node (ref "E15") (pin "6") (pinfunction "O_6") (pintype "output"))
    )
    (net (code "182") (name "Net-(E15B-O)") (class "Default")
      (node (ref "E15") (pin "8") (pinfunction "O_8") (pintype "output"))
      (node (ref "E6") (pin "13") (pinfunction "I1_13") (pintype "input"))
    )
    (net (code "183") (name "Net-(E16A-O)") (class "Default")
      (node (ref "E16") (pin "1") (pinfunction "O_1") (pintype "output"))
      (node (ref "E19") (pin "11") (pinfunction "I_11") (pintype "input"))
    )
    (net (code "184") (name "Net-(E16B-O)") (class "Default")
      (node (ref "E16") (pin "4") (pinfunction "O_4") (pintype "output"))
      (node (ref "E19") (pin "9") (pinfunction "I_9") (pintype "input"))
    )
    (net (code "185") (name "Net-(E16C-O)") (class "Default")
      (node (ref "E16") (pin "10") (pinfunction "O_10") (pintype "output"))
      (node (ref "E19") (pin "13") (pinfunction "I_13") (pintype "input"))
    )
    (net (code "186") (name "Net-(E16D-O)") (class "Default")
      (node (ref "E16") (pin "13") (pinfunction "O_13") (pintype "output"))
      (node (ref "E19") (pin "1") (pinfunction "I_1") (pintype "input"))
    )
    (net (code "187") (name "Net-(E17A-I1)") (class "Default")
      (node (ref "D102") (pin "C") (pinfunction "C_C") (pintype "passive"))
      (node (ref "E17") (pin "2") (pinfunction "I1_2") (pintype "input"))
      (node (ref "R119") (pin "2") (pinfunction "2_2") (pintype "passive"))
    )
    (net (code "188") (name "Net-(E17B-I1)") (class "Default")
      (node (ref "D103") (pin "C") (pinfunction "C_C") (pintype "passive"))
      (node (ref "E17") (pin "5") (pinfunction "I1_5") (pintype "input"))
      (node (ref "R121") (pin "2") (pinfunction "2_2") (pintype "passive"))
    )
    (net (code "189") (name "Net-(E17C-I0)") (class "Default")
      (node (ref "D105") (pin "C") (pinfunction "C_C") (pintype "passive"))
      (node (ref "E17") (pin "9") (pinfunction "I0_9") (pintype "input"))
      (node (ref "R125") (pin "2") (pinfunction "2_2") (pintype "passive"))
    )
    (net (code "190") (name "Net-(E17D-I0)") (class "Default")
      (node (ref "D104") (pin "C") (pinfunction "C_C") (pintype "passive"))
      (node (ref "E17") (pin "12") (pinfunction "I0_12") (pintype "input"))
      (node (ref "R123") (pin "2") (pinfunction "2_2") (pintype "passive"))
    )
    (net (code "191") (name "Net-(E18A-I1)") (class "Default")
      (node (ref "D15") (pin "A") (pinfunction "A_A") (pintype "passive"))
      (node (ref "D27") (pin "A") (pinfunction "A_A") (pintype "passive"))
      (node (ref "D39") (pin "A") (pinfunction "A_A") (pintype "passive"))
      (node (ref "E18") (pin "3") (pinfunction "I1_3") (pintype "input"))
      (node (ref "R10") (pin "1") (pinfunction "1_1") (pintype "passive"))
    )
    (net (code "192") (name "Net-(E18A-O)") (class "Default")
      (node (ref "E18") (pin "1") (pinfunction "O_1") (pintype "output"))
      (node (ref "R53") (pin "1") (pinfunction "1_1") (pintype "passive"))
      (node (ref "R54") (pin "1") (pinfunction "1_1") (pintype "passive"))
    )
    (net (code "193") (name "Net-(E18B-I1)") (class "Default")
      (node (ref "D16") (pin "A") (pinfunction "A_A") (pintype "passive"))
      (node (ref "D28") (pin "A") (pinfunction "A_A") (pintype "passive"))
      (node (ref "D40") (pin "A") (pinfunction "A_A") (pintype "passive"))
      (node (ref "E18") (pin "6") (pinfunction "I1_6") (pintype "input"))
      (node (ref "R9") (pin "1") (pinfunction "1_1") (pintype "passive"))
    )
    (net (code "194") (name "Net-(E18B-O)") (class "Default")
      (node (ref "E18") (pin "4") (pinfunction "O_4") (pintype "output"))
      (node (ref "R50") (pin "1") (pinfunction "1_1") (pintype "passive"))
      (node (ref "R51") (pin "1") (pinfunction "1_1") (pintype "passive"))
    )
    (net (code "195") (name "Net-(E18C-I0)") (class "Default")
      (node (ref "D14") (pin "A") (pinfunction "A_A") (pintype "passive"))
      (node (ref "D26") (pin "A") (pinfunction "A_A") (pintype "passive"))
      (node (ref "D38") (pin "A") (pinfunction "A_A") (pintype "passive"))
      (node (ref "E18") (pin "8") (pinfunction "I0_8") (pintype "input"))
      (node (ref "R11") (pin "1") (pinfunction "1_1") (pintype "passive"))
    )
    (net (code "196") (name "Net-(E18C-O)") (class "Default")
      (node (ref "E18") (pin "10") (pinfunction "O_10") (pintype "output"))
      (node (ref "R56") (pin "1") (pinfunction "1_1") (pintype "passive"))
      (node (ref "R57") (pin "1") (pinfunction "1_1") (pintype "passive"))
    )
    (net (code "197") (name "Net-(E18D-I0)") (class "Default")
      (node (ref "D13") (pin "A") (pinfunction "A_A") (pintype "passive"))
      (node (ref "D25") (pin "A") (pinfunction "A_A") (pintype "passive"))
      (node (ref "D37") (pin "A") (pinfunction "A_A") (pintype "passive"))
      (node (ref "E18") (pin "11") (pinfunction "I0_11") (pintype "input"))
      (node (ref "R12") (pin "1") (pinfunction "1_1") (pintype "passive"))
    )
    (net (code "198") (name "Net-(E18D-O)") (class "Default")
      (node (ref "E18") (pin "13") (pinfunction "O_13") (pintype "output"))
      (node (ref "R59") (pin "1") (pinfunction "1_1") (pintype "passive"))
      (node (ref "R60") (pin "1") (pinfunction "1_1") (pintype "passive"))
    )
    (net (code "199") (name "Net-(E19A-O)") (class "Default")
      (node (ref "E19") (pin "2") (pinfunction "O_2") (pintype "open_collector"))
      (node (ref "I24") (pin "A") (pinfunction "A_A") (pintype "passive"))
      (node (ref "R135") (pin "2") (pinfunction "2_2") (pintype "passive"))
    )
    (net (code "200") (name "Net-(E19B-I)") (class "Default")
      (node (ref "E19") (pin "3") (pinfunction "I_3") (pintype "input"))
      (node (ref "E20") (pin "13") (pinfunction "O_13") (pintype "output"))
    )
    (net (code "201") (name "Net-(E19B-O)") (class "Default")
      (node (ref "E19") (pin "4") (pinfunction "O_4") (pintype "open_collector"))
      (node (ref "I23") (pin "A") (pinfunction "A_A") (pintype "passive"))
      (node (ref "R134") (pin "2") (pinfunction "2_2") (pintype "passive"))
    )
    (net (code "202") (name "Net-(E19C-I)") (class "Default")
      (node (ref "E19") (pin "5") (pinfunction "I_5") (pintype "input"))
      (node (ref "E20") (pin "10") (pinfunction "O_10") (pintype "output"))
    )
    (net (code "203") (name "Net-(E19C-O)") (class "Default")
      (node (ref "E19") (pin "6") (pinfunction "O_6") (pintype "open_collector"))
      (node (ref "I22") (pin "A") (pinfunction "A_A") (pintype "passive"))
      (node (ref "R133") (pin "2") (pinfunction "2_2") (pintype "passive"))
    )
    (net (code "204") (name "Net-(E19D-O)") (class "Default")
      (node (ref "E19") (pin "8") (pinfunction "O_8") (pintype "open_collector"))
      (node (ref "I27") (pin "A") (pinfunction "A_A") (pintype "passive"))
      (node (ref "R138") (pin "2") (pinfunction "2_2") (pintype "passive"))
    )
    (net (code "205") (name "Net-(E19E-O)") (class "Default")
      (node (ref "E19") (pin "10") (pinfunction "O_10") (pintype "open_collector"))
      (node (ref "I26") (pin "A") (pinfunction "A_A") (pintype "passive"))
      (node (ref "R137") (pin "2") (pinfunction "2_2") (pintype "passive"))
    )
    (net (code "206") (name "Net-(E19F-O)") (class "Default")
      (node (ref "E19") (pin "12") (pinfunction "O_12") (pintype "open_collector"))
      (node (ref "I25") (pin "A") (pinfunction "A_A") (pintype "passive"))
      (node (ref "R136") (pin "2") (pinfunction "2_2") (pintype "passive"))
    )
    (net (code "207") (name "Net-(E20A-O)") (class "Default")
      (node (ref "E20") (pin "1") (pinfunction "O_1") (pintype "output"))
      (node (ref "E23") (pin "13") (pinfunction "I_13") (pintype "input"))
    )
    (net (code "208") (name "Net-(E20B-O)") (class "Default")
      (node (ref "E20") (pin "4") (pinfunction "O_4") (pintype "output"))
      (node (ref "E23") (pin "11") (pinfunction "I_11") (pintype "input"))
    )
    (net (code "209") (name "Net-(E21A-I1)") (class "Default")
      (node (ref "D98") (pin "C") (pinfunction "C_C") (pintype "passive"))
      (node (ref "E21") (pin "2") (pinfunction "I1_2") (pintype "input"))
      (node (ref "R111") (pin "2") (pinfunction "2_2") (pintype "passive"))
    )
    (net (code "210") (name "Net-(E21B-I1)") (class "Default")
      (node (ref "D99") (pin "C") (pinfunction "C_C") (pintype "passive"))
      (node (ref "E21") (pin "5") (pinfunction "I1_5") (pintype "input"))
      (node (ref "R113") (pin "2") (pinfunction "2_2") (pintype "passive"))
    )
    (net (code "211") (name "Net-(E21C-I0)") (class "Default")
      (node (ref "D100") (pin "C") (pinfunction "C_C") (pintype "passive"))
      (node (ref "E21") (pin "9") (pinfunction "I0_9") (pintype "input"))
      (node (ref "R115") (pin "2") (pinfunction "2_2") (pintype "passive"))
    )
    (net (code "212") (name "Net-(E21D-I0)") (class "Default")
      (node (ref "D101") (pin "C") (pinfunction "C_C") (pintype "passive"))
      (node (ref "E21") (pin "12") (pinfunction "I0_12") (pintype "input"))
      (node (ref "R117") (pin "2") (pinfunction "2_2") (pintype "passive"))
    )
    (net (code "213") (name "Net-(E22A-I1)") (class "Default")
      (node (ref "D19") (pin "A") (pinfunction "A_A") (pintype "passive"))
      (node (ref "D31") (pin "A") (pinfunction "A_A") (pintype "passive"))
      (node (ref "D43") (pin "A") (pinfunction "A_A") (pintype "passive"))
      (node (ref "E22") (pin "3") (pinfunction "I1_3") (pintype "input"))
      (node (ref "R6") (pin "1") (pinfunction "1_1") (pintype "passive"))
    )
    (net (code "214") (name "Net-(E22A-O)") (class "Default")
      (node (ref "E22") (pin "1") (pinfunction "O_1") (pintype "output"))
      (node (ref "R41") (pin "1") (pinfunction "1_1") (pintype "passive"))
      (node (ref "R42") (pin "1") (pinfunction "1_1") (pintype "passive"))
    )
    (net (code "215") (name "Net-(E22B-I1)") (class "Default")
      (node (ref "D20") (pin "A") (pinfunction "A_A") (pintype "passive"))
      (node (ref "D32") (pin "A") (pinfunction "A_A") (pintype "passive"))
      (node (ref "D44") (pin "A") (pinfunction "A_A") (pintype "passive"))
      (node (ref "E22") (pin "6") (pinfunction "I1_6") (pintype "input"))
      (node (ref "R5") (pin "1") (pinfunction "1_1") (pintype "passive"))
    )
    (net (code "216") (name "Net-(E22B-O)") (class "Default")
      (node (ref "E22") (pin "4") (pinfunction "O_4") (pintype "output"))
      (node (ref "R38") (pin "1") (pinfunction "1_1") (pintype "passive"))
      (node (ref "R39") (pin "1") (pinfunction "1_1") (pintype "passive"))
    )
    (net (code "217") (name "Net-(E22C-I0)") (class "Default")
      (node (ref "D18") (pin "A") (pinfunction "A_A") (pintype "passive"))
      (node (ref "D30") (pin "A") (pinfunction "A_A") (pintype "passive"))
      (node (ref "D42") (pin "A") (pinfunction "A_A") (pintype "passive"))
      (node (ref "E22") (pin "8") (pinfunction "I0_8") (pintype "input"))
      (node (ref "R7") (pin "1") (pinfunction "1_1") (pintype "passive"))
    )
    (net (code "218") (name "Net-(E22C-O)") (class "Default")
      (node (ref "E22") (pin "10") (pinfunction "O_10") (pintype "output"))
      (node (ref "R44") (pin "1") (pinfunction "1_1") (pintype "passive"))
      (node (ref "R45") (pin "1") (pinfunction "1_1") (pintype "passive"))
    )
    (net (code "219") (name "Net-(E22D-I0)") (class "Default")
      (node (ref "D17") (pin "A") (pinfunction "A_A") (pintype "passive"))
      (node (ref "D29") (pin "A") (pinfunction "A_A") (pintype "passive"))
      (node (ref "D41") (pin "A") (pinfunction "A_A") (pintype "passive"))
      (node (ref "E22") (pin "11") (pinfunction "I0_11") (pintype "input"))
      (node (ref "R8") (pin "1") (pinfunction "1_1") (pintype "passive"))
    )
    (net (code "220") (name "Net-(E22D-O)") (class "Default")
      (node (ref "E22") (pin "13") (pinfunction "O_13") (pintype "output"))
      (node (ref "R47") (pin "1") (pinfunction "1_1") (pintype "passive"))
      (node (ref "R48") (pin "1") (pinfunction "1_1") (pintype "passive"))
    )
    (net (code "221") (name "Net-(E23A-I)") (class "Default")
      (node (ref "E23") (pin "1") (pinfunction "I_1") (pintype "input"))
      (node (ref "E24") (pin "13") (pinfunction "O_13") (pintype "output"))
    )
    (net (code "222") (name "Net-(E23A-O)") (class "Default")
      (node (ref "E23") (pin "2") (pinfunction "O_2") (pintype "open_collector"))
      (node (ref "I18") (pin "A") (pinfunction "A_A") (pintype "passive"))
      (node (ref "R129") (pin "2") (pinfunction "2_2") (pintype "passive"))
    )
    (net (code "223") (name "Net-(E23B-I)") (class "Default")
      (node (ref "E23") (pin "3") (pinfunction "I_3") (pintype "input"))
      (node (ref "E24") (pin "10") (pinfunction "O_10") (pintype "output"))
    )
    (net (code "224") (name "Net-(E23B-O)") (class "Default")
      (node (ref "E23") (pin "4") (pinfunction "O_4") (pintype "open_collector"))
      (node (ref "I19") (pin "A") (pinfunction "A_A") (pintype "passive"))
      (node (ref "R130") (pin "2") (pinfunction "2_2") (pintype "passive"))
    )
    (net (code "225") (name "Net-(E23E-O)") (class "Default")
      (node (ref "E23") (pin "10") (pinfunction "O_10") (pintype "open_collector"))
      (node (ref "I21") (pin "A") (pinfunction "A_A") (pintype "passive"))
      (node (ref "R132") (pin "2") (pinfunction "2_2") (pintype "passive"))
    )
    (net (code "226") (name "Net-(E23F-O)") (class "Default")
      (node (ref "E23") (pin "12") (pinfunction "O_12") (pintype "open_collector"))
      (node (ref "I20") (pin "A") (pinfunction "A_A") (pintype "passive"))
      (node (ref "R131") (pin "2") (pinfunction "2_2") (pintype "passive"))
    )
    (net (code "227") (name "Net-(E24A-O)") (class "Default")
      (node (ref "E24") (pin "1") (pinfunction "O_1") (pintype "output"))
      (node (ref "E27") (pin "13") (pinfunction "I_13") (pintype "input"))
    )
    (net (code "228") (name "Net-(E24B-O)") (class "Default")
      (node (ref "E24") (pin "4") (pinfunction "O_4") (pintype "output"))
      (node (ref "E27") (pin "11") (pinfunction "I_11") (pintype "input"))
    )
    (net (code "229") (name "Net-(E25A-I1)") (class "Default")
      (node (ref "D94") (pin "C") (pinfunction "C_C") (pintype "passive"))
      (node (ref "E25") (pin "2") (pinfunction "I1_2") (pintype "input"))
      (node (ref "R103") (pin "2") (pinfunction "2_2") (pintype "passive"))
    )
    (net (code "230") (name "Net-(E25B-I1)") (class "Default")
      (node (ref "D95") (pin "C") (pinfunction "C_C") (pintype "passive"))
      (node (ref "E25") (pin "5") (pinfunction "I1_5") (pintype "input"))
      (node (ref "R105") (pin "2") (pinfunction "2_2") (pintype "passive"))
    )
    (net (code "231") (name "Net-(E25C-I0)") (class "Default")
      (node (ref "D96") (pin "C") (pinfunction "C_C") (pintype "passive"))
      (node (ref "E25") (pin "9") (pinfunction "I0_9") (pintype "input"))
      (node (ref "R107") (pin "2") (pinfunction "2_2") (pintype "passive"))
    )
    (net (code "232") (name "Net-(E25D-I1)") (class "Default")
      (node (ref "D97") (pin "C") (pinfunction "C_C") (pintype "passive"))
      (node (ref "E25") (pin "13") (pinfunction "I1_13") (pintype "input"))
      (node (ref "R109") (pin "2") (pinfunction "2_2") (pintype "passive"))
    )
    (net (code "233") (name "Net-(E26A-I1)") (class "Default")
      (node (ref "D23") (pin "A") (pinfunction "A_A") (pintype "passive"))
      (node (ref "D35") (pin "A") (pinfunction "A_A") (pintype "passive"))
      (node (ref "D47") (pin "A") (pinfunction "A_A") (pintype "passive"))
      (node (ref "E26") (pin "3") (pinfunction "I1_3") (pintype "input"))
      (node (ref "R2") (pin "1") (pinfunction "1_1") (pintype "passive"))
    )
    (net (code "234") (name "Net-(E26A-O)") (class "Default")
      (node (ref "E26") (pin "1") (pinfunction "O_1") (pintype "output"))
      (node (ref "R29") (pin "1") (pinfunction "1_1") (pintype "passive"))
      (node (ref "R30") (pin "1") (pinfunction "1_1") (pintype "passive"))
    )
    (net (code "235") (name "Net-(E26B-I1)") (class "Default")
      (node (ref "D24") (pin "A") (pinfunction "A_A") (pintype "passive"))
      (node (ref "D36") (pin "A") (pinfunction "A_A") (pintype "passive"))
      (node (ref "D48") (pin "A") (pinfunction "A_A") (pintype "passive"))
      (node (ref "E26") (pin "6") (pinfunction "I1_6") (pintype "input"))
      (node (ref "R1") (pin "1") (pinfunction "1_1") (pintype "passive"))
    )
    (net (code "236") (name "Net-(E26B-O)") (class "Default")
      (node (ref "E26") (pin "4") (pinfunction "O_4") (pintype "output"))
      (node (ref "R26") (pin "1") (pinfunction "1_1") (pintype "passive"))
      (node (ref "R27") (pin "1") (pinfunction "1_1") (pintype "passive"))
    )
    (net (code "237") (name "Net-(E26C-I0)") (class "Default")
      (node (ref "D22") (pin "A") (pinfunction "A_A") (pintype "passive"))
      (node (ref "D34") (pin "A") (pinfunction "A_A") (pintype "passive"))
      (node (ref "D46") (pin "A") (pinfunction "A_A") (pintype "passive"))
      (node (ref "E26") (pin "8") (pinfunction "I0_8") (pintype "input"))
      (node (ref "R3") (pin "1") (pinfunction "1_1") (pintype "passive"))
    )
    (net (code "238") (name "Net-(E26C-O)") (class "Default")
      (node (ref "E26") (pin "10") (pinfunction "O_10") (pintype "output"))
      (node (ref "R32") (pin "1") (pinfunction "1_1") (pintype "passive"))
      (node (ref "R33") (pin "1") (pinfunction "1_1") (pintype "passive"))
    )
    (net (code "239") (name "Net-(E26D-I0)") (class "Default")
      (node (ref "D21") (pin "A") (pinfunction "A_A") (pintype "passive"))
      (node (ref "D33") (pin "A") (pinfunction "A_A") (pintype "passive"))
      (node (ref "D45") (pin "A") (pinfunction "A_A") (pintype "passive"))
      (node (ref "E26") (pin "11") (pinfunction "I0_11") (pintype "input"))
      (node (ref "R4") (pin "1") (pinfunction "1_1") (pintype "passive"))
    )
    (net (code "240") (name "Net-(E26D-O)") (class "Default")
      (node (ref "E26") (pin "13") (pinfunction "O_13") (pintype "output"))
      (node (ref "R35") (pin "1") (pinfunction "1_1") (pintype "passive"))
      (node (ref "R36") (pin "1") (pinfunction "1_1") (pintype "passive"))
    )
    (net (code "241") (name "Net-(E27A-I)") (class "Default")
      (node (ref "E27") (pin "1") (pinfunction "I_1") (pintype "input"))
      (node (ref "E28") (pin "1") (pinfunction "O_1") (pintype "output"))
    )
    (net (code "242") (name "Net-(E27A-O)") (class "Default")
      (node (ref "E27") (pin "2") (pinfunction "O_2") (pintype "open_collector"))
      (node (ref "I15") (pin "A") (pinfunction "A_A") (pintype "passive"))
      (node (ref "R141") (pin "2") (pinfunction "2_2") (pintype "passive"))
    )
    (net (code "243") (name "Net-(E27B-I)") (class "Default")
      (node (ref "E27") (pin "3") (pinfunction "I_3") (pintype "input"))
      (node (ref "E28") (pin "13") (pinfunction "O_13") (pintype "output"))
    )
    (net (code "244") (name "Net-(E27B-O)") (class "Default")
      (node (ref "E27") (pin "4") (pinfunction "O_4") (pintype "open_collector"))
      (node (ref "I14") (pin "A") (pinfunction "A_A") (pintype "passive"))
      (node (ref "R140") (pin "2") (pinfunction "2_2") (pintype "passive"))
    )
    (net (code "245") (name "Net-(E27C-I)") (class "Default")
      (node (ref "E27") (pin "5") (pinfunction "I_5") (pintype "input"))
      (node (ref "E28") (pin "10") (pinfunction "O_10") (pintype "output"))
    )
    (net (code "246") (name "Net-(E27C-O)") (class "Default")
      (node (ref "E27") (pin "6") (pinfunction "O_6") (pintype "open_collector"))
      (node (ref "I13") (pin "A") (pinfunction "A_A") (pintype "passive"))
      (node (ref "R139") (pin "2") (pinfunction "2_2") (pintype "passive"))
    )
    (net (code "247") (name "Net-(E27E-O)") (class "Default")
      (node (ref "E27") (pin "10") (pinfunction "O_10") (pintype "open_collector"))
      (node (ref "I17") (pin "A") (pinfunction "A_A") (pintype "passive"))
      (node (ref "R128") (pin "2") (pinfunction "2_2") (pintype "passive"))
    )
    (net (code "248") (name "Net-(E27F-O)") (class "Default")
      (node (ref "E27") (pin "12") (pinfunction "O_12") (pintype "open_collector"))
      (node (ref "I16") (pin "A") (pinfunction "A_A") (pintype "passive"))
      (node (ref "R127") (pin "2") (pinfunction "2_2") (pintype "passive"))
    )
    (net (code "249") (name "Net-(Q1-B)") (class "Default")
      (node (ref "C1") (pin "2") (pinfunction "2_2") (pintype "passive"))
      (node (ref "D1") (pin "C") (pinfunction "C_C") (pintype "passive"))
      (node (ref "Q1") (pin "2") (pinfunction "B_2") (pintype "passive"))
      (node (ref "R27") (pin "2") (pinfunction "2_2") (pintype "passive"))
    )
    (net (code "250") (name "Net-(Q1-C)") (class "Default")
      (node (ref "C1") (pin "1") (pinfunction "1_1") (pintype "passive"))
      (node (ref "I1") (pin "A") (pinfunction "A_A") (pintype "passive"))
      (node (ref "Q1") (pin "3") (pinfunction "C_3") (pintype "passive"))
      (node (ref "R25") (pin "2") (pinfunction "2_2") (pintype "passive"))
    )
    (net (code "251") (name "Net-(Q2-B)") (class "Default")
      (node (ref "C2") (pin "2") (pinfunction "2_2") (pintype "passive"))
      (node (ref "D2") (pin "C") (pinfunction "C_C") (pintype "passive"))
      (node (ref "Q2") (pin "2") (pinfunction "B_2") (pintype "passive"))
      (node (ref "R30") (pin "2") (pinfunction "2_2") (pintype "passive"))
    )
    (net (code "252") (name "Net-(Q2-C)") (class "Default")
      (node (ref "C2") (pin "1") (pinfunction "1_1") (pintype "passive"))
      (node (ref "I2") (pin "A") (pinfunction "A_A") (pintype "passive"))
      (node (ref "Q2") (pin "3") (pinfunction "C_3") (pintype "passive"))
      (node (ref "R28") (pin "2") (pinfunction "2_2") (pintype "passive"))
    )
    (net (code "253") (name "Net-(Q3-B)") (class "Default")
      (node (ref "C3") (pin "2") (pinfunction "2_2") (pintype "passive"))
      (node (ref "D3") (pin "C") (pinfunction "C_C") (pintype "passive"))
      (node (ref "Q3") (pin "2") (pinfunction "B_2") (pintype "passive"))
      (node (ref "R33") (pin "2") (pinfunction "2_2") (pintype "passive"))
    )
    (net (code "254") (name "Net-(Q3-C)") (class "Default")
      (node (ref "C3") (pin "1") (pinfunction "1_1") (pintype "passive"))
      (node (ref "I3") (pin "A") (pinfunction "A_A") (pintype "passive"))
      (node (ref "Q3") (pin "3") (pinfunction "C_3") (pintype "passive"))
      (node (ref "R31") (pin "2") (pinfunction "2_2") (pintype "passive"))
    )
    (net (code "255") (name "Net-(Q4-B)") (class "Default")
      (node (ref "C4") (pin "2") (pinfunction "2_2") (pintype "passive"))
      (node (ref "D4") (pin "C") (pinfunction "C_C") (pintype "passive"))
      (node (ref "Q4") (pin "2") (pinfunction "B_2") (pintype "passive"))
      (node (ref "R36") (pin "2") (pinfunction "2_2") (pintype "passive"))
    )
    (net (code "256") (name "Net-(Q4-C)") (class "Default")
      (node (ref "C4") (pin "1") (pinfunction "1_1") (pintype "passive"))
      (node (ref "I4") (pin "A") (pinfunction "A_A") (pintype "passive"))
      (node (ref "Q4") (pin "3") (pinfunction "C_3") (pintype "passive"))
      (node (ref "R34") (pin "2") (pinfunction "2_2") (pintype "passive"))
    )
    (net (code "257") (name "Net-(Q5-B)") (class "Default")
      (node (ref "C5") (pin "2") (pinfunction "2_2") (pintype "passive"))
      (node (ref "D5") (pin "C") (pinfunction "C_C") (pintype "passive"))
      (node (ref "Q5") (pin "2") (pinfunction "B_2") (pintype "passive"))
      (node (ref "R39") (pin "2") (pinfunction "2_2") (pintype "passive"))
    )
    (net (code "258") (name "Net-(Q5-C)") (class "Default")
      (node (ref "C5") (pin "1") (pinfunction "1_1") (pintype "passive"))
      (node (ref "I5") (pin "A") (pinfunction "A_A") (pintype "passive"))
      (node (ref "Q5") (pin "3") (pinfunction "C_3") (pintype "passive"))
      (node (ref "R37") (pin "2") (pinfunction "2_2") (pintype "passive"))
    )
    (net (code "259") (name "Net-(Q6-B)") (class "Default")
      (node (ref "C6") (pin "2") (pinfunction "2_2") (pintype "passive"))
      (node (ref "D6") (pin "C") (pinfunction "C_C") (pintype "passive"))
      (node (ref "Q6") (pin "2") (pinfunction "B_2") (pintype "passive"))
      (node (ref "R42") (pin "2") (pinfunction "2_2") (pintype "passive"))
    )
    (net (code "260") (name "Net-(Q6-C)") (class "Default")
      (node (ref "C6") (pin "1") (pinfunction "1_1") (pintype "passive"))
      (node (ref "I6") (pin "A") (pinfunction "A_A") (pintype "passive"))
      (node (ref "Q6") (pin "3") (pinfunction "C_3") (pintype "passive"))
      (node (ref "R40") (pin "2") (pinfunction "2_2") (pintype "passive"))
    )
    (net (code "261") (name "Net-(Q7-B)") (class "Default")
      (node (ref "C7") (pin "2") (pinfunction "2_2") (pintype "passive"))
      (node (ref "D7") (pin "C") (pinfunction "C_C") (pintype "passive"))
      (node (ref "Q7") (pin "2") (pinfunction "B_2") (pintype "passive"))
      (node (ref "R45") (pin "2") (pinfunction "2_2") (pintype "passive"))
    )
    (net (code "262") (name "Net-(Q7-C)") (class "Default")
      (node (ref "C7") (pin "1") (pinfunction "1_1") (pintype "passive"))
      (node (ref "I7") (pin "A") (pinfunction "A_A") (pintype "passive"))
      (node (ref "Q7") (pin "3") (pinfunction "C_3") (pintype "passive"))
      (node (ref "R43") (pin "2") (pinfunction "2_2") (pintype "passive"))
    )
    (net (code "263") (name "Net-(Q8-B)") (class "Default")
      (node (ref "C8") (pin "2") (pinfunction "2_2") (pintype "passive"))
      (node (ref "D8") (pin "C") (pinfunction "C_C") (pintype "passive"))
      (node (ref "Q8") (pin "2") (pinfunction "B_2") (pintype "passive"))
      (node (ref "R48") (pin "2") (pinfunction "2_2") (pintype "passive"))
    )
    (net (code "264") (name "Net-(Q8-C)") (class "Default")
      (node (ref "C8") (pin "1") (pinfunction "1_1") (pintype "passive"))
      (node (ref "I8") (pin "A") (pinfunction "A_A") (pintype "passive"))
      (node (ref "Q8") (pin "3") (pinfunction "C_3") (pintype "passive"))
      (node (ref "R46") (pin "2") (pinfunction "2_2") (pintype "passive"))
    )
    (net (code "265") (name "Net-(Q9-B)") (class "Default")
      (node (ref "C9") (pin "2") (pinfunction "2_2") (pintype "passive"))
      (node (ref "D9") (pin "C") (pinfunction "C_C") (pintype "passive"))
      (node (ref "Q9") (pin "2") (pinfunction "B_2") (pintype "passive"))
      (node (ref "R51") (pin "2") (pinfunction "2_2") (pintype "passive"))
    )
    (net (code "266") (name "Net-(Q9-C)") (class "Default")
      (node (ref "C9") (pin "1") (pinfunction "1_1") (pintype "passive"))
      (node (ref "I9") (pin "A") (pinfunction "A_A") (pintype "passive"))
      (node (ref "Q9") (pin "3") (pinfunction "C_3") (pintype "passive"))
      (node (ref "R49") (pin "2") (pinfunction "2_2") (pintype "passive"))
    )
    (net (code "267") (name "Net-(Q10-B)") (class "Default")
      (node (ref "C10") (pin "2") (pinfunction "2_2") (pintype "passive"))
      (node (ref "D10") (pin "C") (pinfunction "C_C") (pintype "passive"))
      (node (ref "Q10") (pin "2") (pinfunction "B_2") (pintype "passive"))
      (node (ref "R54") (pin "2") (pinfunction "2_2") (pintype "passive"))
    )
    (net (code "268") (name "Net-(Q10-C)") (class "Default")
      (node (ref "C10") (pin "1") (pinfunction "1_1") (pintype "passive"))
      (node (ref "I10") (pin "A") (pinfunction "A_A") (pintype "passive"))
      (node (ref "Q10") (pin "3") (pinfunction "C_3") (pintype "passive"))
      (node (ref "R52") (pin "2") (pinfunction "2_2") (pintype "passive"))
    )
    (net (code "269") (name "Net-(Q11-B)") (class "Default")
      (node (ref "C11") (pin "2") (pinfunction "2_2") (pintype "passive"))
      (node (ref "D11") (pin "C") (pinfunction "C_C") (pintype "passive"))
      (node (ref "Q11") (pin "2") (pinfunction "B_2") (pintype "passive"))
      (node (ref "R57") (pin "2") (pinfunction "2_2") (pintype "passive"))
    )
    (net (code "270") (name "Net-(Q11-C)") (class "Default")
      (node (ref "C11") (pin "1") (pinfunction "1_1") (pintype "passive"))
      (node (ref "I11") (pin "A") (pinfunction "A_A") (pintype "passive"))
      (node (ref "Q11") (pin "3") (pinfunction "C_3") (pintype "passive"))
      (node (ref "R55") (pin "2") (pinfunction "2_2") (pintype "passive"))
    )
    (net (code "271") (name "Net-(Q12-B)") (class "Default")
      (node (ref "C12") (pin "2") (pinfunction "2_2") (pintype "passive"))
      (node (ref "D12") (pin "C") (pinfunction "C_C") (pintype "passive"))
      (node (ref "Q12") (pin "2") (pinfunction "B_2") (pintype "passive"))
      (node (ref "R60") (pin "2") (pinfunction "2_2") (pintype "passive"))
    )
    (net (code "272") (name "Net-(Q12-C)") (class "Default")
      (node (ref "C12") (pin "1") (pinfunction "1_1") (pintype "passive"))
      (node (ref "I12") (pin "A") (pinfunction "A_A") (pintype "passive"))
      (node (ref "Q12") (pin "3") (pinfunction "C_3") (pintype "passive"))
      (node (ref "R58") (pin "2") (pinfunction "2_2") (pintype "passive"))
    )
    (net (code "273") (name "Net-(Q13-B)") (class "Default")
      (node (ref "Q13") (pin "2") (pinfunction "B_2") (pintype "passive"))
      (node (ref "R154") (pin "2") (pinfunction "2_2") (pintype "passive"))
    )
    (net (code "274") (name "Net-(Q13-E)") (class "Default")
      (node (ref "Q13") (pin "1") (pinfunction "E_1") (pintype "passive"))
      (node (ref "Q14") (pin "2") (pinfunction "B_2") (pintype "passive"))
      (node (ref "R155") (pin "1") (pinfunction "1_1") (pintype "passive"))
    )
    (net (code "275") (name "Net-(Q14-C)") (class "Default")
      (node (ref "Q14") (pin "3") (pinfunction "C_3") (pintype "passive"))
      (node (ref "Q15") (pin "2") (pinfunction "B_2") (pintype "passive"))
      (node (ref "R157") (pin "2") (pinfunction "2_2") (pintype "passive"))
    )
    (net (code "276") (name "Net-(Q14-E)") (class "Default")
      (node (ref "D116") (pin "A") (pinfunction "A_A") (pintype "passive"))
      (node (ref "Q14") (pin "1") (pinfunction "E_1") (pintype "passive"))
      (node (ref "Q15") (pin "1") (pinfunction "E_1") (pintype "passive"))
      (node (ref "R156") (pin "1") (pinfunction "1_1") (pintype "passive"))
    )
    (net (code "277") (name "Net-(Q15-C)") (class "Default")
      (node (ref "C14") (pin "2") (pinfunction "2_2") (pintype "passive"))
      (node (ref "D118") (pin "C") (pinfunction "C_C") (pintype "passive"))
      (node (ref "D120") (pin "A") (pinfunction "A_A") (pintype "passive"))
      (node (ref "Q15") (pin "3") (pinfunction "C_3") (pintype "passive"))
      (node (ref "R158") (pin "2") (pinfunction "2_2") (pintype "passive"))
    )
    (net (code "278") (name "Net-(Q16-B)") (class "Default")
      (node (ref "Q16") (pin "2") (pinfunction "B_2") (pintype "passive"))
      (node (ref "Q19") (pin "3") (pinfunction "C_3") (pintype "passive"))
      (node (ref "R167") (pin "1") (pinfunction "1_1") (pintype "passive"))
    )
    (net (code "279") (name "Net-(Q16-C)") (class "Default")
      (node (ref "I28") (pin "B") (pinfunction "B_B") (pintype "passive"))
      (node (ref "Q16") (pin "3") (pinfunction "C_3") (pintype "passive"))
      (node (ref "R168") (pin "1") (pinfunction "1_1") (pintype "passive"))
    )
    (net (code "280") (name "Net-(Q16-E)") (class "Default")
      (node (ref "D122") (pin "C") (pinfunction "C_C") (pintype "passive"))
      (node (ref "Q16") (pin "1") (pinfunction "E_1") (pintype "passive"))
      (node (ref "R168") (pin "2") (pinfunction "2_2") (pintype "passive"))
    )
    (net (code "281") (name "Net-(Q17-B)") (class "Default")
      (node (ref "Q17") (pin "2") (pinfunction "B_2") (pintype "passive"))
      (node (ref "R172") (pin "2") (pinfunction "2_2") (pintype "passive"))
    )
    (net (code "282") (name "Net-(Q17-C)") (class "Default")
      (node (ref "Q17") (pin "3") (pinfunction "C_3") (pintype "passive"))
      (node (ref "R163") (pin "1") (pinfunction "1_1") (pintype "passive"))
    )
    (net (code "283") (name "Net-(Q18-B)") (class "Default")
      (node (ref "Q18") (pin "2") (pinfunction "B_2") (pintype "passive"))
      (node (ref "R174") (pin "2") (pinfunction "2_2") (pintype "passive"))
    )
    (net (code "284") (name "Net-(Q18-C)") (class "Default")
      (node (ref "Q18") (pin "3") (pinfunction "C_3") (pintype "passive"))
      (node (ref "R165") (pin "1") (pinfunction "1_1") (pintype "passive"))
    )
    (net (code "285") (name "Net-(Q19-B)") (class "Default")
      (node (ref "Q19") (pin "2") (pinfunction "B_2") (pintype "passive"))
      (node (ref "R166") (pin "2") (pinfunction "2_2") (pintype "passive"))
    )
    (net (code "286") (name "Net-(S2A-A1)") (class "Default")
      (node (ref "R85") (pin "1") (pinfunction "1_1") (pintype "passive"))
      (node (ref "R86") (pin "1") (pinfunction "1_1") (pintype "passive"))
      (node (ref "S2") (pin "1") (pinfunction "A1_1") (pintype "bidirectional"))
      (node (ref "S2") (pin "4") (pinfunction "B1_4") (pintype "bidirectional"))
    )
    (net (code "287") (name "Net-(S3A-O)") (class "Default")
      (node (ref "R87") (pin "1") (pinfunction "1_1") (pintype "passive"))
      (node (ref "R88") (pin "1") (pinfunction "1_1") (pintype "passive"))
      (node (ref "S3") (pin "1") (pinfunction "O_1") (pintype "passive"))
    )
    (net (code "288") (name "Net-(S4A-O)") (class "Default")
      (node (ref "R89") (pin "1") (pinfunction "1_1") (pintype "passive"))
      (node (ref "R90") (pin "1") (pinfunction "1_1") (pintype "passive"))
      (node (ref "S4") (pin "1") (pinfunction "O_1") (pintype "passive"))
    )
    (net (code "289") (name "Net-(S5A-O)") (class "Default")
      (node (ref "R91") (pin "1") (pinfunction "1_1") (pintype "passive"))
      (node (ref "R92") (pin "1") (pinfunction "1_1") (pintype "passive"))
      (node (ref "S5") (pin "1") (pinfunction "O_1") (pintype "passive"))
    )
    (net (code "290") (name "Net-(S6A-O)") (class "Default")
      (node (ref "R93") (pin "1") (pinfunction "1_1") (pintype "passive"))
      (node (ref "R94") (pin "1") (pinfunction "1_1") (pintype "passive"))
      (node (ref "S6") (pin "1") (pinfunction "O_1") (pintype "passive"))
    )
    (net (code "291") (name "Net-(S7A-P)") (class "Default")
      (node (ref "R95") (pin "1") (pinfunction "1_1") (pintype "passive"))
      (node (ref "R96") (pin "1") (pinfunction "1_1") (pintype "passive"))
      (node (ref "S7") (pin "2") (pinfunction "P_2") (pintype "passive"))
    )
    (net (code "292") (name "Net-(S8A-O)") (class "Default")
      (node (ref "R97") (pin "1") (pinfunction "1_1") (pintype "passive"))
      (node (ref "R98") (pin "1") (pinfunction "1_1") (pintype "passive"))
      (node (ref "S8") (pin "1") (pinfunction "O_1") (pintype "passive"))
    )
    (net (code "293") (name "Net-(S9A-A1)") (class "Default")
      (node (ref "R100") (pin "1") (pinfunction "1_1") (pintype "passive"))
      (node (ref "R99") (pin "1") (pinfunction "1_1") (pintype "passive"))
      (node (ref "S9") (pin "1") (pinfunction "A1_1") (pintype "bidirectional"))
      (node (ref "S9") (pin "4") (pinfunction "B1_4") (pintype "bidirectional"))
    )
    (net (code "294") (name "Net-(S10A-A1)") (class "Default")
      (node (ref "R101") (pin "1") (pinfunction "1_1") (pintype "passive"))
      (node (ref "R102") (pin "1") (pinfunction "1_1") (pintype "passive"))
      (node (ref "S10") (pin "1") (pinfunction "A1_1") (pintype "bidirectional"))
      (node (ref "S10") (pin "4") (pinfunction "B1_4") (pintype "bidirectional"))
    )
    (net (code "295") (name "Net-(S11A-A1)") (class "Default")
      (node (ref "R103") (pin "1") (pinfunction "1_1") (pintype "passive"))
      (node (ref "R104") (pin "1") (pinfunction "1_1") (pintype "passive"))
      (node (ref "S11") (pin "1") (pinfunction "A1_1") (pintype "bidirectional"))
      (node (ref "S11") (pin "4") (pinfunction "B1_4") (pintype "bidirectional"))
    )
    (net (code "296") (name "Net-(S12A-A1)") (class "Default")
      (node (ref "R105") (pin "1") (pinfunction "1_1") (pintype "passive"))
      (node (ref "R106") (pin "1") (pinfunction "1_1") (pintype "passive"))
      (node (ref "S12") (pin "1") (pinfunction "A1_1") (pintype "bidirectional"))
      (node (ref "S12") (pin "4") (pinfunction "B1_4") (pintype "bidirectional"))
    )
    (net (code "297") (name "Net-(S13A-A1)") (class "Default")
      (node (ref "R107") (pin "1") (pinfunction "1_1") (pintype "passive"))
      (node (ref "R108") (pin "1") (pinfunction "1_1") (pintype "passive"))
      (node (ref "S13") (pin "1") (pinfunction "A1_1") (pintype "bidirectional"))
      (node (ref "S13") (pin "4") (pinfunction "B1_4") (pintype "bidirectional"))
    )
    (net (code "298") (name "Net-(S14A-A1)") (class "Default")
      (node (ref "R109") (pin "1") (pinfunction "1_1") (pintype "passive"))
      (node (ref "R110") (pin "1") (pinfunction "1_1") (pintype "passive"))
      (node (ref "S14") (pin "1") (pinfunction "A1_1") (pintype "bidirectional"))
      (node (ref "S14") (pin "4") (pinfunction "B1_4") (pintype "bidirectional"))
    )
    (net (code "299") (name "Net-(S15A-A1)") (class "Default")
      (node (ref "R111") (pin "1") (pinfunction "1_1") (pintype "passive"))
      (node (ref "R112") (pin "1") (pinfunction "1_1") (pintype "passive"))
      (node (ref "S15") (pin "1") (pinfunction "A1_1") (pintype "bidirectional"))
      (node (ref "S15") (pin "4") (pinfunction "B1_4") (pintype "bidirectional"))
    )
    (net (code "300") (name "Net-(S16A-A1)") (class "Default")
      (node (ref "R113") (pin "1") (pinfunction "1_1") (pintype "passive"))
      (node (ref "R114") (pin "1") (pinfunction "1_1") (pintype "passive"))
      (node (ref "S16") (pin "1") (pinfunction "A1_1") (pintype "bidirectional"))
      (node (ref "S16") (pin "4") (pinfunction "B1_4") (pintype "bidirectional"))
    )
    (net (code "301") (name "Net-(S17A-A1)") (class "Default")
      (node (ref "R115") (pin "1") (pinfunction "1_1") (pintype "passive"))
      (node (ref "R116") (pin "1") (pinfunction "1_1") (pintype "passive"))
      (node (ref "S17") (pin "1") (pinfunction "A1_1") (pintype "bidirectional"))
      (node (ref "S17") (pin "4") (pinfunction "B1_4") (pintype "bidirectional"))
    )
    (net (code "302") (name "Net-(S18A-A1)") (class "Default")
      (node (ref "R117") (pin "1") (pinfunction "1_1") (pintype "passive"))
      (node (ref "R118") (pin "1") (pinfunction "1_1") (pintype "passive"))
      (node (ref "S18") (pin "1") (pinfunction "A1_1") (pintype "bidirectional"))
      (node (ref "S18") (pin "4") (pinfunction "B1_4") (pintype "bidirectional"))
    )
    (net (code "303") (name "Net-(S19A-A1)") (class "Default")
      (node (ref "R119") (pin "1") (pinfunction "1_1") (pintype "passive"))
      (node (ref "R120") (pin "1") (pinfunction "1_1") (pintype "passive"))
      (node (ref "S19") (pin "1") (pinfunction "A1_1") (pintype "bidirectional"))
      (node (ref "S19") (pin "4") (pinfunction "B1_4") (pintype "bidirectional"))
    )
    (net (code "304") (name "Net-(S20A-A1)") (class "Default")
      (node (ref "R121") (pin "1") (pinfunction "1_1") (pintype "passive"))
      (node (ref "R122") (pin "1") (pinfunction "1_1") (pintype "passive"))
      (node (ref "S20") (pin "1") (pinfunction "A1_1") (pintype "bidirectional"))
      (node (ref "S20") (pin "4") (pinfunction "B1_4") (pintype "bidirectional"))
    )
    (net (code "305") (name "Net-(S21A-A1)") (class "Default")
      (node (ref "R123") (pin "1") (pinfunction "1_1") (pintype "passive"))
      (node (ref "R124") (pin "1") (pinfunction "1_1") (pintype "passive"))
      (node (ref "S21") (pin "1") (pinfunction "A1_1") (pintype "bidirectional"))
      (node (ref "S21") (pin "4") (pinfunction "B1_4") (pintype "bidirectional"))
    )
    (net (code "306") (name "Net-(S22A-A1)") (class "Default")
      (node (ref "R125") (pin "1") (pinfunction "1_1") (pintype "passive"))
      (node (ref "R126") (pin "1") (pinfunction "1_1") (pintype "passive"))
      (node (ref "S22") (pin "1") (pinfunction "A1_1") (pintype "bidirectional"))
      (node (ref "S22") (pin "4") (pinfunction "B1_4") (pintype "bidirectional"))
    )
    (net (code "307") (name "PAN_LOCK") (class "Default")
      (node (ref "BLUE") (pin "1") (pinfunction "1_1") (pintype "passive"))
      (node (ref "S10") (pin "2") (pinfunction "A2_2") (pintype "bidirectional"))
      (node (ref "S10") (pin "5") (pinfunction "B2_5") (pintype "bidirectional"))
      (node (ref "S2") (pin "2") (pinfunction "A2_2") (pintype "bidirectional"))
      (node (ref "S2") (pin "5") (pinfunction "B2_5") (pintype "bidirectional"))
      (node (ref "S3") (pin "2") (pinfunction "P_2") (pintype "passive"))
      (node (ref "S4") (pin "2") (pinfunction "P_2") (pintype "passive"))
      (node (ref "S5") (pin "2") (pinfunction "P_2") (pintype "passive"))
      (node (ref "S6") (pin "2") (pinfunction "P_2") (pintype "passive"))
      (node (ref "S7") (pin "1") (pinfunction "O_1") (pintype "passive"))
      (node (ref "S8") (pin "2") (pinfunction "P_2") (pintype "passive"))
      (node (ref "S9") (pin "2") (pinfunction "A2_2") (pintype "bidirectional"))
      (node (ref "S9") (pin "5") (pinfunction "B2_5") (pintype "bidirectional"))
    )
    (net (code "308") (name "PULSE_LA") (class "Default")
      (node (ref "Q17") (pin "1") (pinfunction "E_1") (pintype "passive"))
      (node (ref "U$2") (pin "DR2") (pinfunction "1_DR2") (pintype "bidirectional"))
    )
    (net (code "309") (name "SSTP") (class "Default")
      (node (ref "D92") (pin "C") (pinfunction "C_C") (pintype "passive"))
      (node (ref "E6") (pin "5") (pinfunction "I1_5") (pintype "input"))
      (node (ref "R99") (pin "2") (pinfunction "2_2") (pintype "passive"))
    )
    (net (code "310") (name "STATE_EN") (class "Default")
      (node (ref "R143") (pin "1") (pinfunction "1_1") (pintype "passive"))
      (node (ref "R61") (pin "2") (pinfunction "2_2") (pintype "passive"))
      (node (ref "R63") (pin "2") (pinfunction "2_2") (pintype "passive"))
      (node (ref "R65") (pin "2") (pinfunction "2_2") (pintype "passive"))
      (node (ref "R67") (pin "2") (pinfunction "2_2") (pintype "passive"))
      (node (ref "R69") (pin "2") (pinfunction "2_2") (pintype "passive"))
      (node (ref "R71") (pin "2") (pinfunction "2_2") (pintype "passive"))
      (node (ref "R73") (pin "2") (pinfunction "2_2") (pintype "passive"))
      (node (ref "R75") (pin "2") (pinfunction "2_2") (pintype "passive"))
      (node (ref "R77") (pin "2") (pinfunction "2_2") (pintype "passive"))
      (node (ref "R79") (pin "2") (pinfunction "2_2") (pintype "passive"))
      (node (ref "R81") (pin "2") (pinfunction "2_2") (pintype "passive"))
      (node (ref "R83") (pin "2") (pinfunction "2_2") (pintype "passive"))
      (node (ref "S1") (pin "A6") (pinfunction "A6_A6") (pintype "passive"))
    )
    (net (code "311") (name "STATUS_EN") (class "Default")
      (node (ref "D106") (pin "C") (pinfunction "C_C") (pintype "passive"))
      (node (ref "R148") (pin "1") (pinfunction "1_1") (pintype "passive"))
      (node (ref "S1") (pin "A5") (pinfunction "A5_A5") (pintype "passive"))
    )
    (net (code "312") (name "STOP") (class "Default")
      (node (ref "E4") (pin "11") (pinfunction "O_11") (pintype "open_collector"))
      (node (ref "U$2") (pin "DS2") (pinfunction "1_DS2") (pintype "bidirectional"))
    )
    (net (code "313") (name "SWITCH") (class "Default")
      (node (ref "D81") (pin "A") (pinfunction "A_A") (pintype "passive"))
      (node (ref "D85") (pin "C") (pinfunction "C_C") (pintype "passive"))
      (node (ref "R85") (pin "2") (pinfunction "2_2") (pintype "passive"))
      (node (ref "R86") (pin "2") (pinfunction "2_2") (pintype "passive"))
      (node (ref "U$2") (pin "DV2") (pinfunction "1_DV2") (pintype "bidirectional"))
    )
    (net (code "314") (name "TP4") (class "Default")
      (node (ref "E13") (pin "8") (pinfunction "I0_8") (pintype "input"))
      (node (ref "E13") (pin "9") (pinfunction "I1_9") (pintype "input"))
      (node (ref "U$2") (pin "CJ2") (pinfunction "1_CJ2") (pintype "bidirectional"))
    )
    (net (code "315") (name "TS1") (class "Default")
      (node (ref "E2") (pin "2") (pinfunction "I0_2") (pintype "input"))
      (node (ref "U$2") (pin "CK2") (pinfunction "1_CK2") (pintype "bidirectional"))
    )
    (net (code "316") (name "TS3") (class "Default")
      (node (ref "E2") (pin "5") (pinfunction "I0_5") (pintype "input"))
      (node (ref "U$2") (pin "CM2") (pinfunction "1_CM2") (pintype "bidirectional"))
    )
    (net (code "317") (name "TS4") (class "Default")
      (node (ref "E11") (pin "12") (pinfunction "I0_12") (pintype "input"))
      (node (ref "U$2") (pin "CP2") (pinfunction "1_CP2") (pintype "bidirectional"))
    )
    (net (code "318") (name "U_MODE") (class "Default")
      (node (ref "E13") (pin "5") (pinfunction "I0_5") (pintype "input"))
      (node (ref "U$2") (pin "DM2") (pinfunction "1_DM2") (pintype "bidirectional"))
    )
    (net (code "319") (name "VCC") (class "Default")
      (node (ref "C18") (pin "+") (pinfunction "+_+") (pintype "passive"))
      (node (ref "C19") (pin "+") (pinfunction "+_+") (pintype "passive"))
      (node (ref "C20") (pin "+") (pinfunction "+_+") (pintype "passive"))
      (node (ref "C22") (pin "1") (pinfunction "1_1") (pintype "passive"))
      (node (ref "C23") (pin "1") (pinfunction "1_1") (pintype "passive"))
      (node (ref "C24") (pin "1") (pinfunction "1_1") (pintype "passive"))
      (node (ref "C25") (pin "1") (pinfunction "1_1") (pintype "passive"))
      (node (ref "C26") (pin "1") (pinfunction "1_1") (pintype "passive"))
      (node (ref "C27") (pin "1") (pinfunction "1_1") (pintype "passive"))
      (node (ref "C28") (pin "1") (pinfunction "1_1") (pintype "passive"))
      (node (ref "C29") (pin "1") (pinfunction "1_1") (pintype "passive"))
      (node (ref "C30") (pin "1") (pinfunction "1_1") (pintype "passive"))
      (node (ref "C31") (pin "1") (pinfunction "1_1") (pintype "passive"))
      (node (ref "C32") (pin "1") (pinfunction "1_1") (pintype "passive"))
      (node (ref "C33") (pin "1") (pinfunction "1_1") (pintype "passive"))
      (node (ref "C34") (pin "1") (pinfunction "1_1") (pintype "passive"))
      (node (ref "C35") (pin "1") (pinfunction "1_1") (pintype "passive"))
      (node (ref "C36") (pin "1") (pinfunction "1_1") (pintype "passive"))
      (node (ref "C37") (pin "1") (pinfunction "1_1") (pintype "passive"))
      (node (ref "C38") (pin "1") (pinfunction "1_1") (pintype "passive"))
      (node (ref "C39") (pin "1") (pinfunction "1_1") (pintype "passive"))
      (node (ref "E15") (pin "3") (pinfunction "G_3") (pintype "input"))
      (node (ref "R1") (pin "2") (pinfunction "2_2") (pintype "passive"))
      (node (ref "R10") (pin "2") (pinfunction "2_2") (pintype "passive"))
      (node (ref "R100") (pin "2") (pinfunction "2_2") (pintype "passive"))
      (node (ref "R102") (pin "2") (pinfunction "2_2") (pintype "passive"))
      (node (ref "R104") (pin "2") (pinfunction "2_2") (pintype "passive"))
      (node (ref "R106") (pin "2") (pinfunction "2_2") (pintype "passive"))
      (node (ref "R108") (pin "2") (pinfunction "2_2") (pintype "passive"))
      (node (ref "R11") (pin "2") (pinfunction "2_2") (pintype "passive"))
      (node (ref "R110") (pin "2") (pinfunction "2_2") (pintype "passive"))
      (node (ref "R112") (pin "2") (pinfunction "2_2") (pintype "passive"))
      (node (ref "R114") (pin "2") (pinfunction "2_2") (pintype "passive"))
      (node (ref "R116") (pin "2") (pinfunction "2_2") (pintype "passive"))
      (node (ref "R118") (pin "2") (pinfunction "2_2") (pintype "passive"))
      (node (ref "R12") (pin "2") (pinfunction "2_2") (pintype "passive"))
      (node (ref "R120") (pin "2") (pinfunction "2_2") (pintype "passive"))
      (node (ref "R122") (pin "2") (pinfunction "2_2") (pintype "passive"))
      (node (ref "R124") (pin "2") (pinfunction "2_2") (pintype "passive"))
      (node (ref "R126") (pin "2") (pinfunction "2_2") (pintype "passive"))
      (node (ref "R142") (pin "2") (pinfunction "2_2") (pintype "passive"))
      (node (ref "R143") (pin "2") (pinfunction "2_2") (pintype "passive"))
      (node (ref "R144") (pin "2") (pinfunction "2_2") (pintype "passive"))
      (node (ref "R145") (pin "2") (pinfunction "2_2") (pintype "passive"))
      (node (ref "R146") (pin "2") (pinfunction "2_2") (pintype "passive"))
      (node (ref "R147") (pin "2") (pinfunction "2_2") (pintype "passive"))
      (node (ref "R151") (pin "2") (pinfunction "2_2") (pintype "passive"))
      (node (ref "R152") (pin "2") (pinfunction "2_2") (pintype "passive"))
      (node (ref "R155") (pin "2") (pinfunction "2_2") (pintype "passive"))
      (node (ref "R156") (pin "2") (pinfunction "2_2") (pintype "passive"))
      (node (ref "R161") (pin "2") (pinfunction "2_2") (pintype "passive"))
      (node (ref "R162") (pin "2") (pinfunction "2_2") (pintype "passive"))
      (node (ref "R163") (pin "2") (pinfunction "2_2") (pintype "passive"))
      (node (ref "R164") (pin "2") (pinfunction "2_2") (pintype "passive"))
      (node (ref "R165") (pin "2") (pinfunction "2_2") (pintype "passive"))
      (node (ref "R167") (pin "2") (pinfunction "2_2") (pintype "passive"))
      (node (ref "R169") (pin "1") (pinfunction "1_1") (pintype "passive"))
      (node (ref "R170") (pin "2") (pinfunction "2_2") (pintype "passive"))
      (node (ref "R175") (pin "2") (pinfunction "2_2") (pintype "passive"))
      (node (ref "R2") (pin "2") (pinfunction "2_2") (pintype "passive"))
      (node (ref "R3") (pin "2") (pinfunction "2_2") (pintype "passive"))
      (node (ref "R4") (pin "2") (pinfunction "2_2") (pintype "passive"))
      (node (ref "R5") (pin "2") (pinfunction "2_2") (pintype "passive"))
      (node (ref "R6") (pin "2") (pinfunction "2_2") (pintype "passive"))
      (node (ref "R7") (pin "2") (pinfunction "2_2") (pintype "passive"))
      (node (ref "R8") (pin "2") (pinfunction "2_2") (pintype "passive"))
      (node (ref "R88") (pin "2") (pinfunction "2_2") (pintype "passive"))
      (node (ref "R9") (pin "2") (pinfunction "2_2") (pintype "passive"))
      (node (ref "R90") (pin "2") (pinfunction "2_2") (pintype "passive"))
      (node (ref "R92") (pin "2") (pinfunction "2_2") (pintype "passive"))
      (node (ref "R94") (pin "2") (pinfunction "2_2") (pintype "passive"))
      (node (ref "R96") (pin "2") (pinfunction "2_2") (pintype "passive"))
      (node (ref "R98") (pin "2") (pinfunction "2_2") (pintype "passive"))
      (node (ref "U$2") (pin "AA2") (pinfunction "1_AA2") (pintype "bidirectional"))
      (node (ref "U$2") (pin "BA2") (pinfunction "1_BA2") (pintype "bidirectional"))
      (node (ref "U$2") (pin "CA2") (pinfunction "1_CA2") (pintype "bidirectional"))
    )
    (net (code "320") (name "WILL_START") (class "Default")
      (node (ref "E10") (pin "2") (pinfunction "O_2") (pintype "output"))
      (node (ref "E11") (pin "5") (pinfunction "I1_5") (pintype "input"))
      (node (ref "E12") (pin "13") (pinfunction "I1_13") (pintype "input"))
      (node (ref "R153") (pin "1") (pinfunction "1_1") (pintype "passive"))
      (node (ref "R175") (pin "1") (pinfunction "1_1") (pintype "passive"))
    )
    (net (code "321") (name "unconnected-(S1-PadC)") (class "Default")
      (node (ref "S1") (pin "C") (pinfunction "C_C") (pintype "passive"))
    )
    (net (code "322") (name "unconnected-(S1-PadC1)") (class "Default")
      (node (ref "S1") (pin "C1") (pinfunction "C1_C1") (pintype "passive"))
    )
    (net (code "323") (name "unconnected-(S1-PadC2)") (class "Default")
      (node (ref "S1") (pin "C2") (pinfunction "C2_C2") (pintype "passive"))
    )
    (net (code "324") (name "unconnected-(S1-PadC3)") (class "Default")
      (node (ref "S1") (pin "C3") (pinfunction "C3_C3") (pintype "passive"))
    )
    (net (code "325") (name "unconnected-(S1-PadC4)") (class "Default")
      (node (ref "S1") (pin "C4") (pinfunction "C4_C4") (pintype "passive"))
    )
    (net (code "326") (name "unconnected-(S1-PadC5)") (class "Default")
      (node (ref "S1") (pin "C5") (pinfunction "C5_C5") (pintype "passive"))
    )
    (net (code "327") (name "unconnected-(S1-PadC6)") (class "Default")
      (node (ref "S1") (pin "C6") (pinfunction "C6_C6") (pintype "passive"))
    )
    (net (code "328") (name "unconnected-(S2A-A3-Pad3)") (class "Default")
      (node (ref "S2") (pin "3") (pinfunction "A3_3") (pintype "bidirectional"))
    )
    (net (code "329") (name "unconnected-(S2A-B3-Pad6)") (class "Default")
      (node (ref "S2") (pin "6") (pinfunction "B3_6") (pintype "bidirectional"))
    )
    (net (code "330") (name "unconnected-(S3A-S-Pad3)") (class "Default")
      (node (ref "S3") (pin "3") (pinfunction "S_3") (pintype "passive"))
    )
    (net (code "331") (name "unconnected-(S4A-S-Pad3)") (class "Default")
      (node (ref "S4") (pin "3") (pinfunction "S_3") (pintype "passive"))
    )
    (net (code "332") (name "unconnected-(S5A-S-Pad3)") (class "Default")
      (node (ref "S5") (pin "3") (pinfunction "S_3") (pintype "passive"))
    )
    (net (code "333") (name "unconnected-(S6A-S-Pad3)") (class "Default")
      (node (ref "S6") (pin "3") (pinfunction "S_3") (pintype "passive"))
    )
    (net (code "334") (name "unconnected-(S7A-S-Pad3)") (class "Default")
      (node (ref "S7") (pin "3") (pinfunction "S_3") (pintype "passive"))
    )
    (net (code "335") (name "unconnected-(S8A-S-Pad3)") (class "Default")
      (node (ref "S8") (pin "3") (pinfunction "S_3") (pintype "passive"))
    )
    (net (code "336") (name "unconnected-(S9A-A3-Pad3)") (class "Default")
      (node (ref "S9") (pin "3") (pinfunction "A3_3") (pintype "bidirectional"))
    )
    (net (code "337") (name "unconnected-(S9A-B3-Pad6)") (class "Default")
      (node (ref "S9") (pin "6") (pinfunction "B3_6") (pintype "bidirectional"))
    )
    (net (code "338") (name "unconnected-(S10A-A3-Pad3)") (class "Default")
      (node (ref "S10") (pin "3") (pinfunction "A3_3") (pintype "bidirectional"))
    )
    (net (code "339") (name "unconnected-(S10A-B3-Pad6)") (class "Default")
      (node (ref "S10") (pin "6") (pinfunction "B3_6") (pintype "bidirectional"))
    )
    (net (code "340") (name "unconnected-(S11A-A3-Pad3)") (class "Default")
      (node (ref "S11") (pin "3") (pinfunction "A3_3") (pintype "bidirectional"))
    )
    (net (code "341") (name "unconnected-(S11A-B3-Pad6)") (class "Default")
      (node (ref "S11") (pin "6") (pinfunction "B3_6") (pintype "bidirectional"))
    )
    (net (code "342") (name "unconnected-(S12A-A3-Pad3)") (class "Default")
      (node (ref "S12") (pin "3") (pinfunction "A3_3") (pintype "bidirectional"))
    )
    (net (code "343") (name "unconnected-(S12A-B3-Pad6)") (class "Default")
      (node (ref "S12") (pin "6") (pinfunction "B3_6") (pintype "bidirectional"))
    )
    (net (code "344") (name "unconnected-(S13A-A3-Pad3)") (class "Default")
      (node (ref "S13") (pin "3") (pinfunction "A3_3") (pintype "bidirectional"))
    )
    (net (code "345") (name "unconnected-(S13A-B3-Pad6)") (class "Default")
      (node (ref "S13") (pin "6") (pinfunction "B3_6") (pintype "bidirectional"))
    )
    (net (code "346") (name "unconnected-(S14A-A3-Pad3)") (class "Default")
      (node (ref "S14") (pin "3") (pinfunction "A3_3") (pintype "bidirectional"))
    )
    (net (code "347") (name "unconnected-(S14A-B3-Pad6)") (class "Default")
      (node (ref "S14") (pin "6") (pinfunction "B3_6") (pintype "bidirectional"))
    )
    (net (code "348") (name "unconnected-(S15A-A3-Pad3)") (class "Default")
      (node (ref "S15") (pin "3") (pinfunction "A3_3") (pintype "bidirectional"))
    )
    (net (code "349") (name "unconnected-(S15A-B3-Pad6)") (class "Default")
      (node (ref "S15") (pin "6") (pinfunction "B3_6") (pintype "bidirectional"))
    )
    (net (code "350") (name "unconnected-(S16A-A3-Pad3)") (class "Default")
      (node (ref "S16") (pin "3") (pinfunction "A3_3") (pintype "bidirectional"))
    )
    (net (code "351") (name "unconnected-(S16A-B3-Pad6)") (class "Default")
      (node (ref "S16") (pin "6") (pinfunction "B3_6") (pintype "bidirectional"))
    )
    (net (code "352") (name "unconnected-(S17A-A3-Pad3)") (class "Default")
      (node (ref "S17") (pin "3") (pinfunction "A3_3") (pintype "bidirectional"))
    )
    (net (code "353") (name "unconnected-(S17A-B3-Pad6)") (class "Default")
      (node (ref "S17") (pin "6") (pinfunction "B3_6") (pintype "bidirectional"))
    )
    (net (code "354") (name "unconnected-(S18A-A3-Pad3)") (class "Default")
      (node (ref "S18") (pin "3") (pinfunction "A3_3") (pintype "bidirectional"))
    )
    (net (code "355") (name "unconnected-(S18A-B3-Pad6)") (class "Default")
      (node (ref "S18") (pin "6") (pinfunction "B3_6") (pintype "bidirectional"))
    )
    (net (code "356") (name "unconnected-(S19A-A3-Pad3)") (class "Default")
      (node (ref "S19") (pin "3") (pinfunction "A3_3") (pintype "bidirectional"))
    )
    (net (code "357") (name "unconnected-(S19A-B3-Pad6)") (class "Default")
      (node (ref "S19") (pin "6") (pinfunction "B3_6") (pintype "bidirectional"))
    )
    (net (code "358") (name "unconnected-(S20A-A3-Pad3)") (class "Default")
      (node (ref "S20") (pin "3") (pinfunction "A3_3") (pintype "bidirectional"))
    )
    (net (code "359") (name "unconnected-(S20A-B3-Pad6)") (class "Default")
      (node (ref "S20") (pin "6") (pinfunction "B3_6") (pintype "bidirectional"))
    )
    (net (code "360") (name "unconnected-(S21A-A3-Pad3)") (class "Default")
      (node (ref "S21") (pin "3") (pinfunction "A3_3") (pintype "bidirectional"))
    )
    (net (code "361") (name "unconnected-(S21A-B3-Pad6)") (class "Default")
      (node (ref "S21") (pin "6") (pinfunction "B3_6") (pintype "bidirectional"))
    )
    (net (code "362") (name "unconnected-(S22A-A3-Pad3)") (class "Default")
      (node (ref "S22") (pin "3") (pinfunction "A3_3") (pintype "bidirectional"))
    )
    (net (code "363") (name "unconnected-(S22A-B3-Pad6)") (class "Default")
      (node (ref "S22") (pin "6") (pinfunction "B3_6") (pintype "bidirectional"))
    )
    (net (code "364") (name "~{RUN}") (class "Default")
      (node (ref "E11") (pin "4") (pinfunction "I0_4") (pintype "input"))
      (node (ref "E9") (pin "1") (pinfunction "I_1") (pintype "input"))
      (node (ref "U$2") (pin "BU2") (pinfunction "1_BU2") (pintype "bidirectional"))
    )
  )
)
